# FPGC-CycloneIV-AIO.net
KiCad netlist of a schematic drawn in EasyEDA Pro
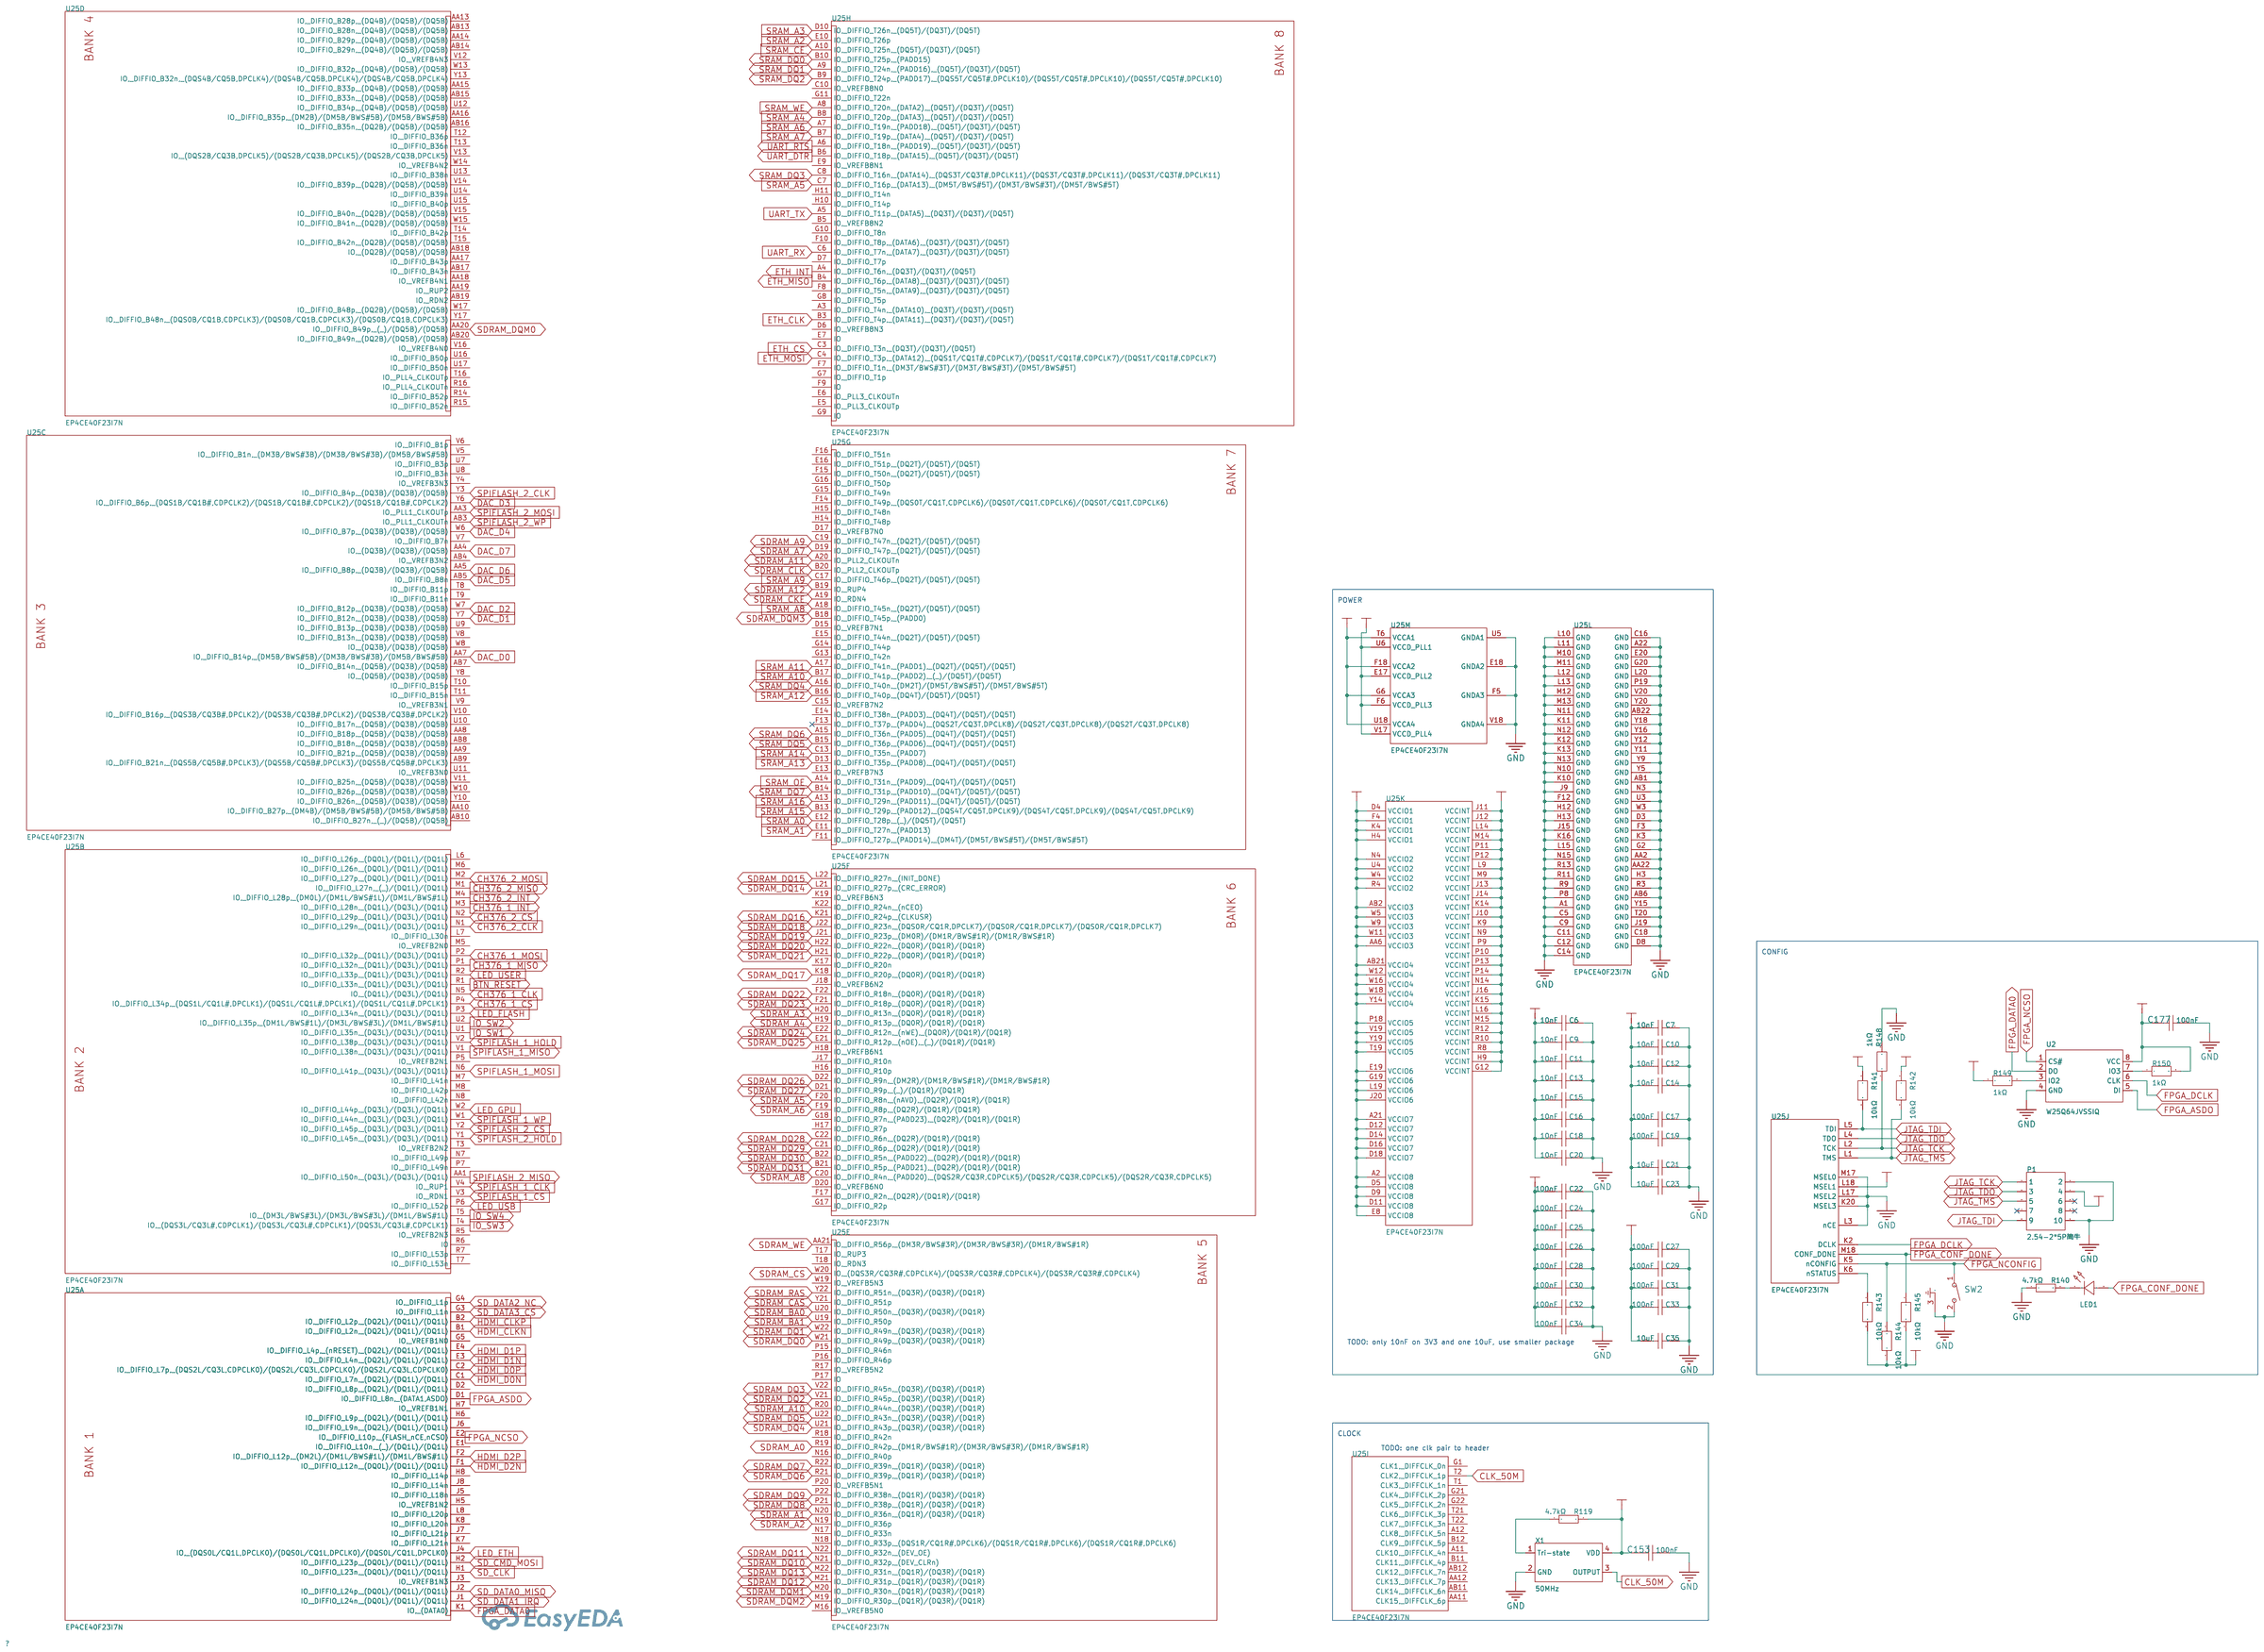
[diagram p0: FPGA]
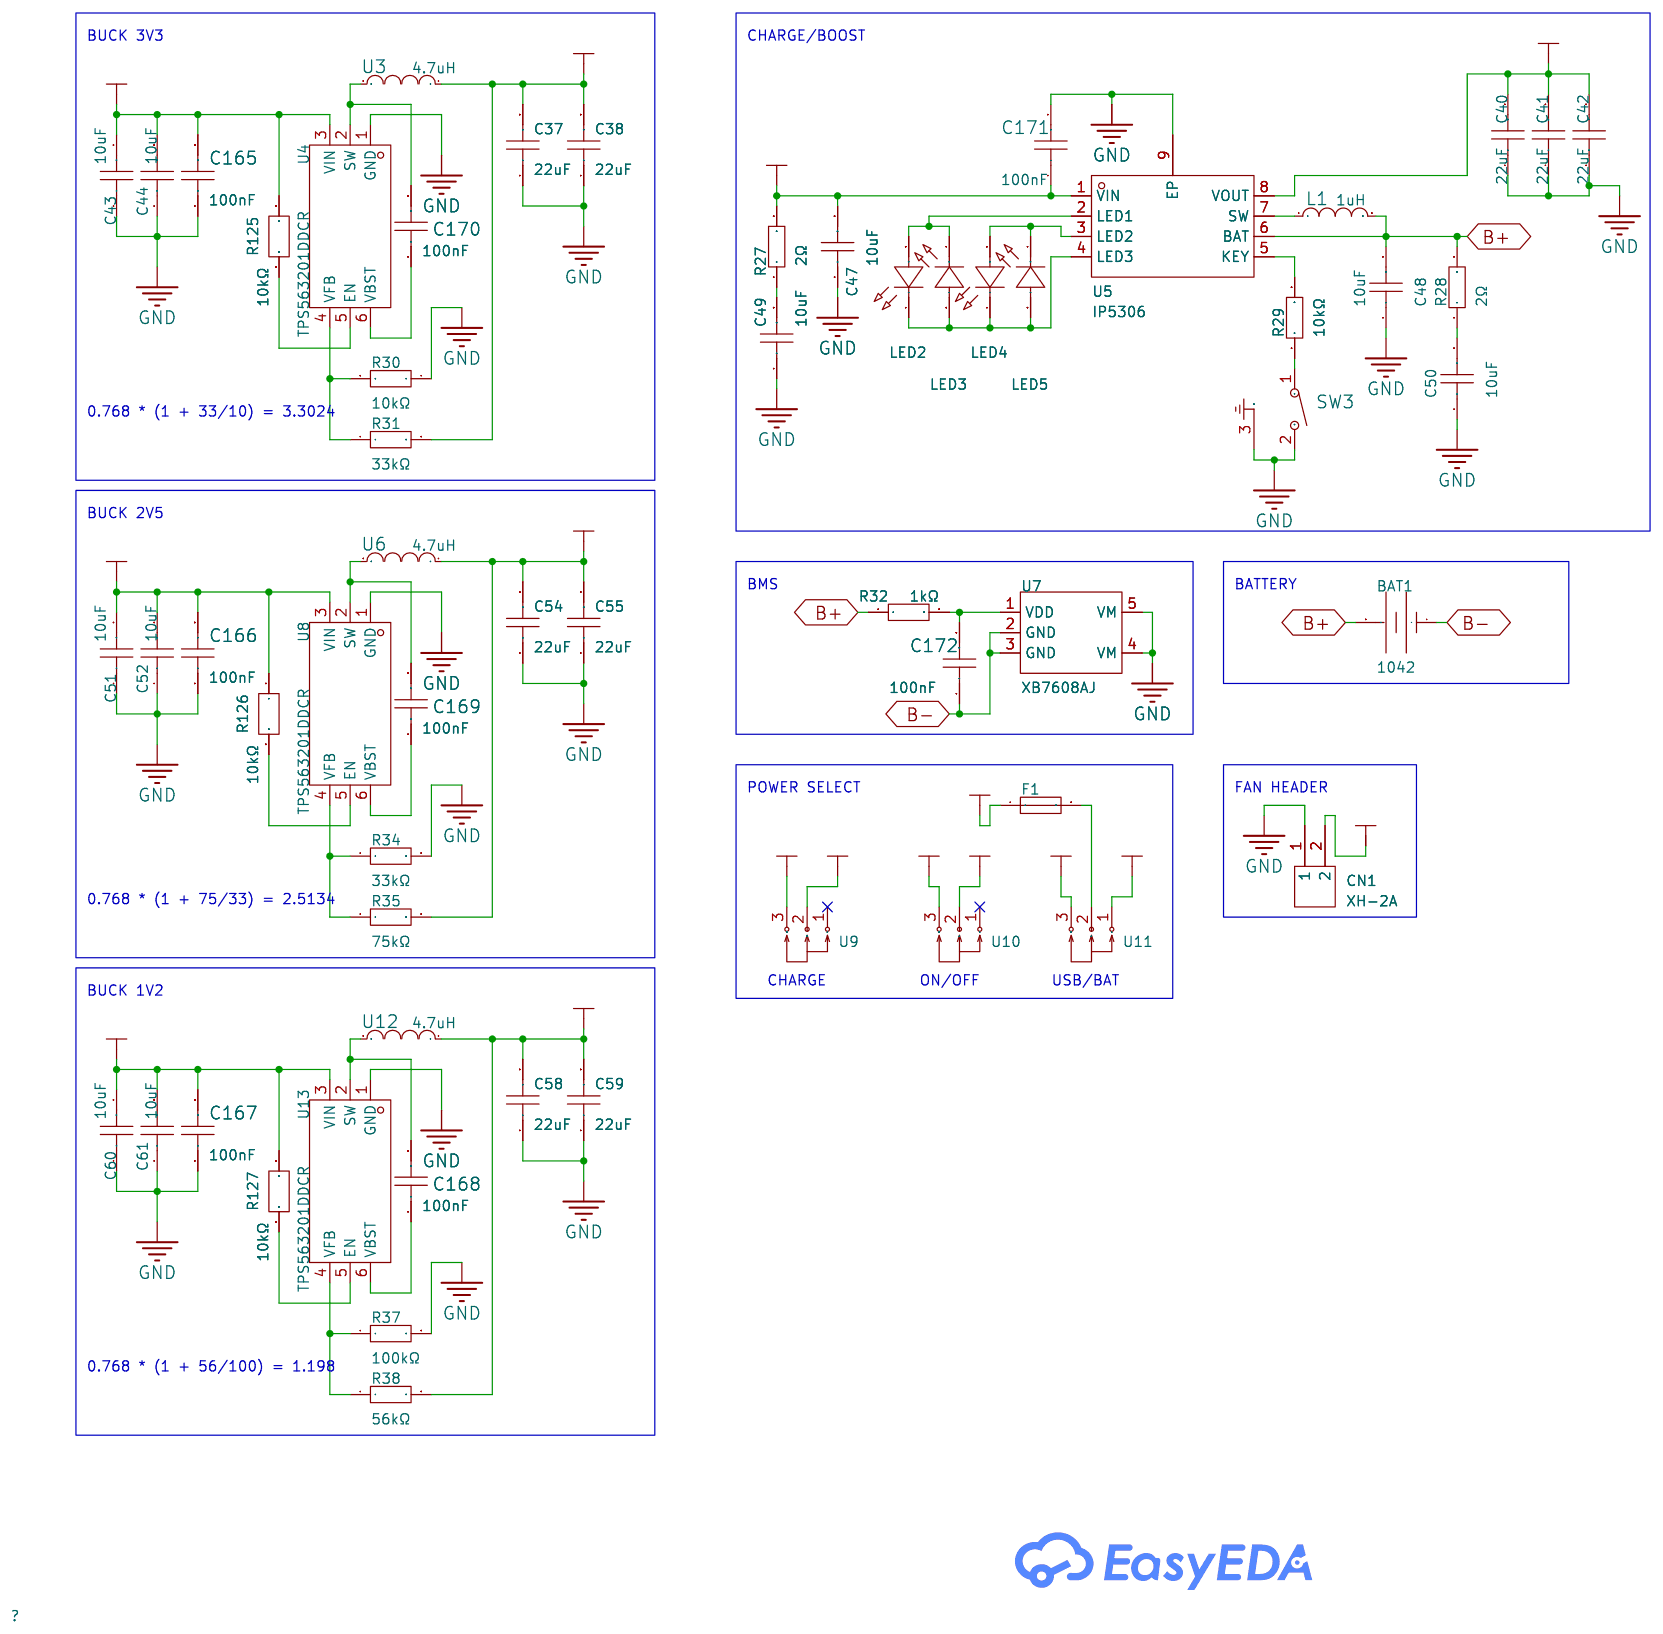
[diagram p1: Power]
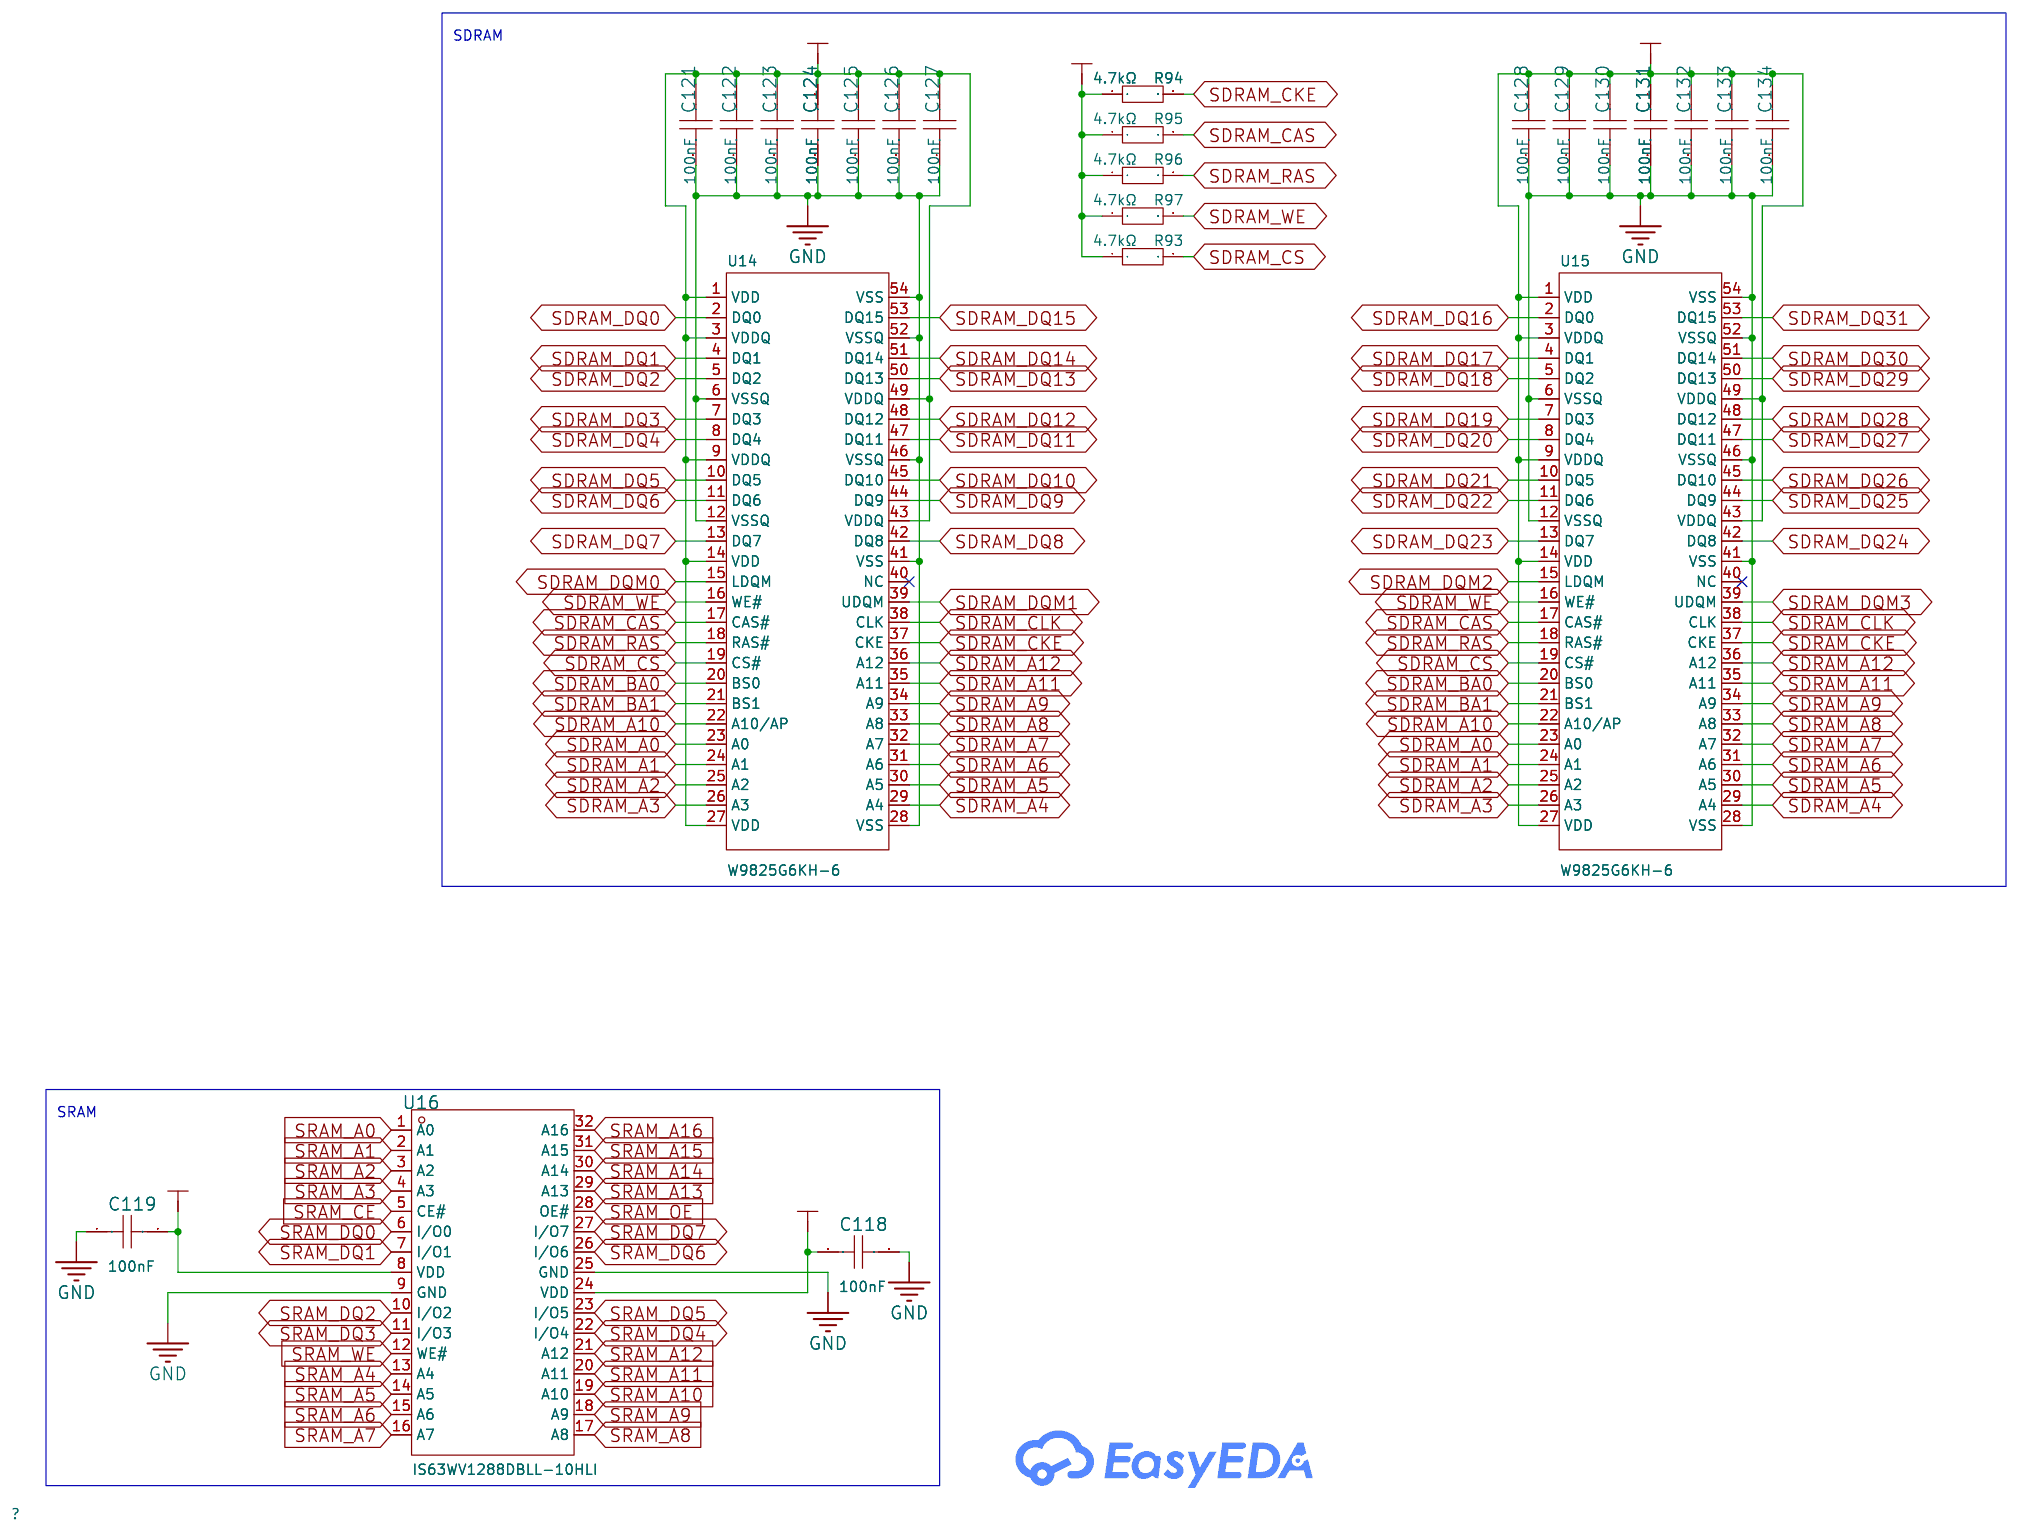
[diagram p2: RAM]
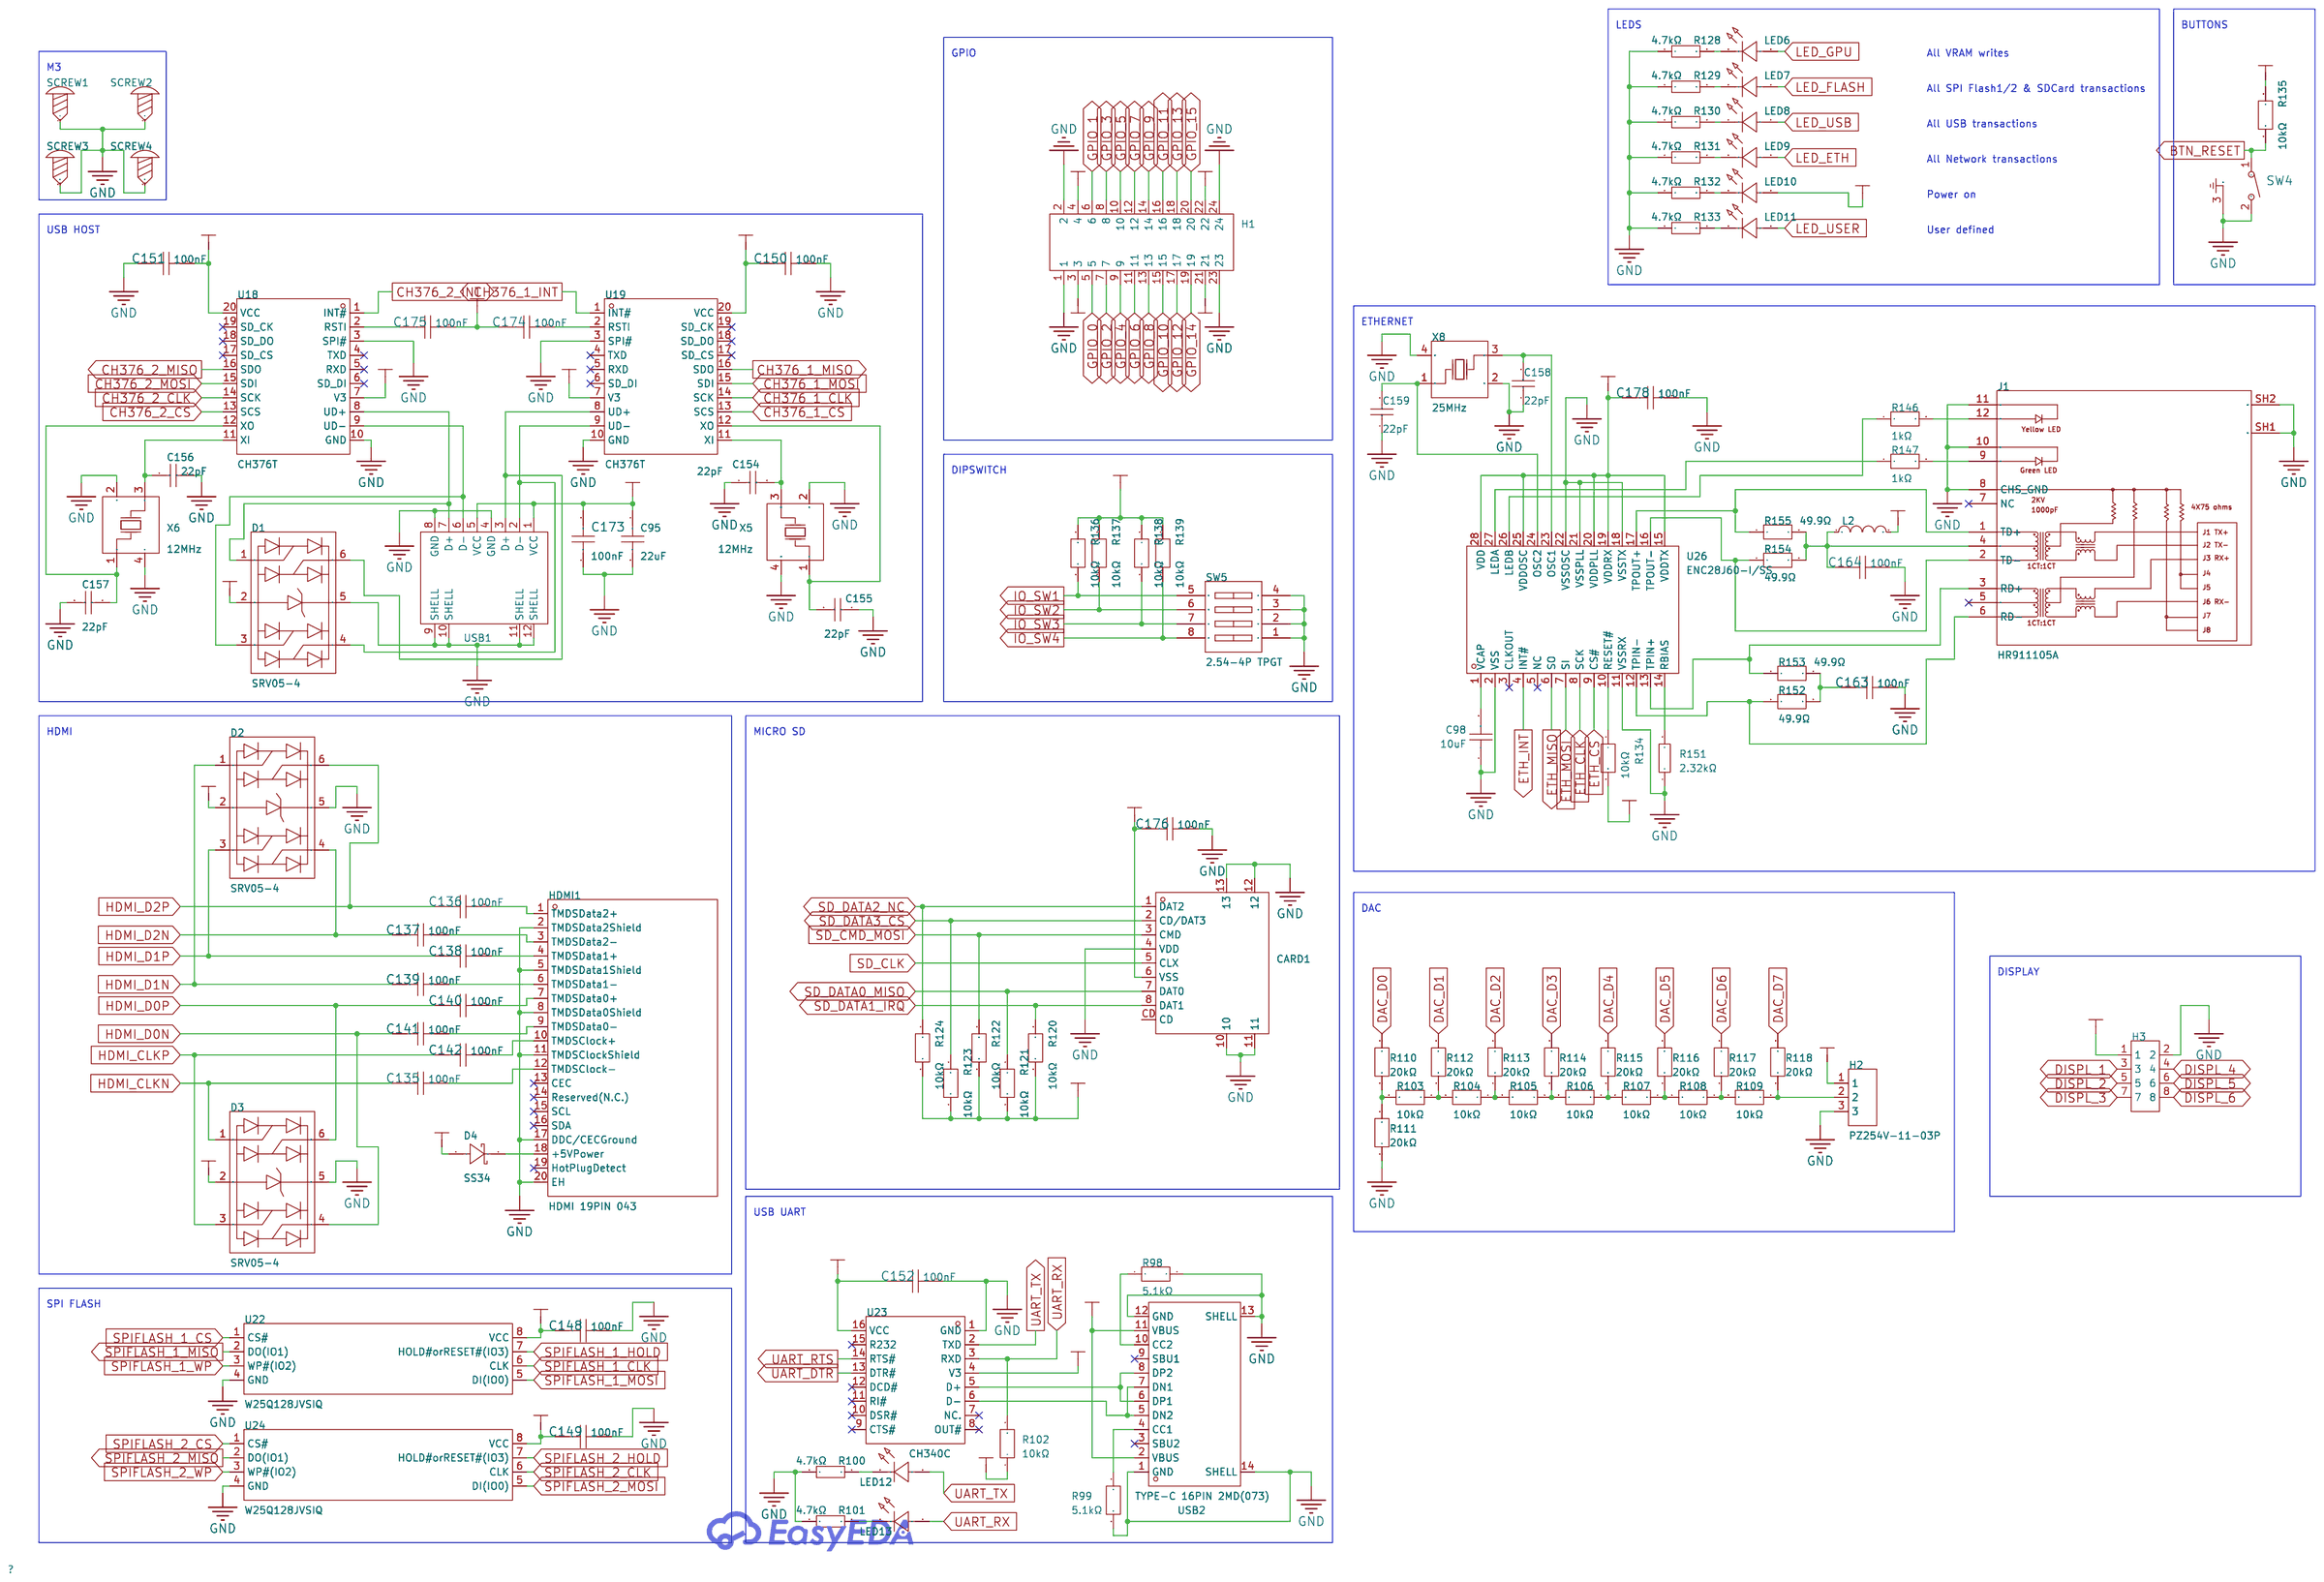
[diagram p3: IO]

(export (version "E")
  (design (tool "Eeschema 10.0.6"))
  (components
    (comp (ref "C6")
      (value "10nF")
      (footprint "easyedapro:C0805")
      (description "Capacitance:10nF Tolerance:±10% Tolerance:±10% Voltage Rating:50V Temperature Coefficient:X7R")
      (fields
        (field (name "Manufacturer Part") "CC0805KRX7R9BB103")
        (field (name "Manufacturer") "YAGEO(国巨)")
      )
      (libsource (lib "easyedapro") (part "CC0805KRX7R9BB103"))
    )
    (comp (ref "C7")
      (value "10nF")
      (footprint "easyedapro:C0805")
      (description "Capacitance:10nF Tolerance:±10% Tolerance:±10% Voltage Rating:50V Temperature Coefficient:X7R")
      (fields
        (field (name "Manufacturer Part") "CC0805KRX7R9BB103")
        (field (name "Manufacturer") "YAGEO(国巨)")
      )
      (libsource (lib "easyedapro") (part "CC0805KRX7R9BB103"))
    )
    (comp (ref "C9")
      (value "10nF")
      (footprint "easyedapro:C0805")
      (description "Capacitance:10nF Tolerance:±10% Tolerance:±10% Voltage Rating:50V Temperature Coefficient:X7R")
      (fields
        (field (name "Manufacturer Part") "CC0805KRX7R9BB103")
        (field (name "Manufacturer") "YAGEO(国巨)")
      )
      (libsource (lib "easyedapro") (part "CC0805KRX7R9BB103"))
    )
    (comp (ref "C10")
      (value "10nF")
      (footprint "easyedapro:C0805")
      (description "Capacitance:10nF Tolerance:±10% Tolerance:±10% Voltage Rating:50V Temperature Coefficient:X7R")
      (fields
        (field (name "Manufacturer Part") "CC0805KRX7R9BB103")
        (field (name "Manufacturer") "YAGEO(国巨)")
      )
      (libsource (lib "easyedapro") (part "CC0805KRX7R9BB103"))
    )
    (comp (ref "C11")
      (value "10nF")
      (footprint "easyedapro:C0805")
      (description "Capacitance:10nF Tolerance:±10% Tolerance:±10% Voltage Rating:50V Temperature Coefficient:X7R")
      (fields
        (field (name "Manufacturer Part") "CC0805KRX7R9BB103")
        (field (name "Manufacturer") "YAGEO(国巨)")
      )
      (libsource (lib "easyedapro") (part "CC0805KRX7R9BB103"))
    )
    (comp (ref "C12")
      (value "10nF")
      (footprint "easyedapro:C0805")
      (description "Capacitance:10nF Tolerance:±10% Tolerance:±10% Voltage Rating:50V Temperature Coefficient:X7R")
      (fields
        (field (name "Manufacturer Part") "CC0805KRX7R9BB103")
        (field (name "Manufacturer") "YAGEO(国巨)")
      )
      (libsource (lib "easyedapro") (part "CC0805KRX7R9BB103"))
    )
    (comp (ref "C13")
      (value "10nF")
      (footprint "easyedapro:C0805")
      (description "Capacitance:10nF Tolerance:±10% Tolerance:±10% Voltage Rating:50V Temperature Coefficient:X7R")
      (fields
        (field (name "Manufacturer Part") "CC0805KRX7R9BB103")
        (field (name "Manufacturer") "YAGEO(国巨)")
      )
      (libsource (lib "easyedapro") (part "CC0805KRX7R9BB103"))
    )
    (comp (ref "C14")
      (value "10nF")
      (footprint "easyedapro:C0805")
      (description "Capacitance:10nF Tolerance:±10% Tolerance:±10% Voltage Rating:50V Temperature Coefficient:X7R")
      (fields
        (field (name "Manufacturer Part") "CC0805KRX7R9BB103")
        (field (name "Manufacturer") "YAGEO(国巨)")
      )
      (libsource (lib "easyedapro") (part "CC0805KRX7R9BB103"))
    )
    (comp (ref "C15")
      (value "10nF")
      (footprint "easyedapro:C0805")
      (description "Capacitance:10nF Tolerance:±10% Tolerance:±10% Voltage Rating:50V Temperature Coefficient:X7R")
      (fields
        (field (name "Manufacturer Part") "CC0805KRX7R9BB103")
        (field (name "Manufacturer") "YAGEO(国巨)")
      )
      (libsource (lib "easyedapro") (part "CC0805KRX7R9BB103"))
    )
    (comp (ref "C16")
      (value "10nF")
      (footprint "easyedapro:C0805")
      (description "Capacitance:10nF Tolerance:±10% Tolerance:±10% Voltage Rating:50V Temperature Coefficient:X7R")
      (fields
        (field (name "Manufacturer Part") "CC0805KRX7R9BB103")
        (field (name "Manufacturer") "YAGEO(国巨)")
      )
      (libsource (lib "easyedapro") (part "CC0805KRX7R9BB103"))
    )
    (comp (ref "C17")
      (value "100nF")
      (footprint "easyedapro:C0805")
      (description "Capacitance:100nF Tolerance:±10% Tolerance:±10% Voltage Rating:50V Temperature Coefficient:X7R")
      (fields
        (field (name "Manufacturer Part") "CC0805KRX7R9BB104")
        (field (name "Manufacturer") "YAGEO(国巨)")
      )
      (libsource (lib "easyedapro") (part "CC0805KRX7R9BB104"))
    )
    (comp (ref "C18")
      (value "10nF")
      (footprint "easyedapro:C0805")
      (description "Capacitance:10nF Tolerance:±10% Tolerance:±10% Voltage Rating:50V Temperature Coefficient:X7R")
      (fields
        (field (name "Manufacturer Part") "CC0805KRX7R9BB103")
        (field (name "Manufacturer") "YAGEO(国巨)")
      )
      (libsource (lib "easyedapro") (part "CC0805KRX7R9BB103"))
    )
    (comp (ref "C19")
      (value "100nF")
      (footprint "easyedapro:C0805")
      (description "Capacitance:100nF Tolerance:±10% Tolerance:±10% Voltage Rating:50V Temperature Coefficient:X7R")
      (fields
        (field (name "Manufacturer Part") "CC0805KRX7R9BB104")
        (field (name "Manufacturer") "YAGEO(国巨)")
      )
      (libsource (lib "easyedapro") (part "CC0805KRX7R9BB104"))
    )
    (comp (ref "C20")
      (value "10nF")
      (footprint "easyedapro:C0805")
      (description "Capacitance:10nF Tolerance:±10% Tolerance:±10% Voltage Rating:50V Temperature Coefficient:X7R")
      (fields
        (field (name "Manufacturer Part") "CC0805KRX7R9BB103")
        (field (name "Manufacturer") "YAGEO(国巨)")
      )
      (libsource (lib "easyedapro") (part "CC0805KRX7R9BB103"))
    )
    (comp (ref "C21")
      (value "10uF")
      (footprint "easyedapro:C0805")
      (description "Capacitance:10uF Tolerance:±10% Tolerance:±10% Voltage Rating:25V Temperature Coefficient:X5R")
      (fields
        (field (name "Manufacturer Part") "CL21A106KAYNNNE")
        (field (name "Manufacturer") "SAMSUNG(三星)")
      )
      (libsource (lib "easyedapro") (part "CL21A106KAYNNNE"))
    )
    (comp (ref "C22")
      (value "100nF")
      (footprint "easyedapro:C0805")
      (description "Capacitance:100nF Tolerance:±10% Tolerance:±10% Voltage Rating:50V Temperature Coefficient:X7R")
      (fields
        (field (name "Manufacturer Part") "CC0805KRX7R9BB104")
        (field (name "Manufacturer") "YAGEO(国巨)")
      )
      (libsource (lib "easyedapro") (part "CC0805KRX7R9BB104"))
    )
    (comp (ref "C23")
      (value "10uF")
      (footprint "easyedapro:C0805")
      (description "Capacitance:10uF Tolerance:±10% Tolerance:±10% Voltage Rating:25V Temperature Coefficient:X5R")
      (fields
        (field (name "Manufacturer Part") "CL21A106KAYNNNE")
        (field (name "Manufacturer") "SAMSUNG(三星)")
      )
      (libsource (lib "easyedapro") (part "CL21A106KAYNNNE"))
    )
    (comp (ref "C24")
      (value "100nF")
      (footprint "easyedapro:C0805")
      (description "Capacitance:100nF Tolerance:±10% Tolerance:±10% Voltage Rating:50V Temperature Coefficient:X7R")
      (fields
        (field (name "Manufacturer Part") "CC0805KRX7R9BB104")
        (field (name "Manufacturer") "YAGEO(国巨)")
      )
      (libsource (lib "easyedapro") (part "CC0805KRX7R9BB104"))
    )
    (comp (ref "C25")
      (value "100nF")
      (footprint "easyedapro:C0805")
      (description "Capacitance:100nF Tolerance:±10% Tolerance:±10% Voltage Rating:50V Temperature Coefficient:X7R")
      (fields
        (field (name "Manufacturer Part") "CC0805KRX7R9BB104")
        (field (name "Manufacturer") "YAGEO(国巨)")
      )
      (libsource (lib "easyedapro") (part "CC0805KRX7R9BB104"))
    )
    (comp (ref "C26")
      (value "100nF")
      (footprint "easyedapro:C0805")
      (description "Capacitance:100nF Tolerance:±10% Tolerance:±10% Voltage Rating:50V Temperature Coefficient:X7R")
      (fields
        (field (name "Manufacturer Part") "CC0805KRX7R9BB104")
        (field (name "Manufacturer") "YAGEO(国巨)")
      )
      (libsource (lib "easyedapro") (part "CC0805KRX7R9BB104"))
    )
    (comp (ref "C27")
      (value "100nF")
      (footprint "easyedapro:C0805")
      (description "Capacitance:100nF Tolerance:±10% Tolerance:±10% Voltage Rating:50V Temperature Coefficient:X7R")
      (fields
        (field (name "Manufacturer Part") "CC0805KRX7R9BB104")
        (field (name "Manufacturer") "YAGEO(国巨)")
      )
      (libsource (lib "easyedapro") (part "CC0805KRX7R9BB104"))
    )
    (comp (ref "C28")
      (value "100nF")
      (footprint "easyedapro:C0805")
      (description "Capacitance:100nF Tolerance:±10% Tolerance:±10% Voltage Rating:50V Temperature Coefficient:X7R")
      (fields
        (field (name "Manufacturer Part") "CC0805KRX7R9BB104")
        (field (name "Manufacturer") "YAGEO(国巨)")
      )
      (libsource (lib "easyedapro") (part "CC0805KRX7R9BB104"))
    )
    (comp (ref "C29")
      (value "100nF")
      (footprint "easyedapro:C0805")
      (description "Capacitance:100nF Tolerance:±10% Tolerance:±10% Voltage Rating:50V Temperature Coefficient:X7R")
      (fields
        (field (name "Manufacturer Part") "CC0805KRX7R9BB104")
        (field (name "Manufacturer") "YAGEO(国巨)")
      )
      (libsource (lib "easyedapro") (part "CC0805KRX7R9BB104"))
    )
    (comp (ref "C30")
      (value "100nF")
      (footprint "easyedapro:C0805")
      (description "Capacitance:100nF Tolerance:±10% Tolerance:±10% Voltage Rating:50V Temperature Coefficient:X7R")
      (fields
        (field (name "Manufacturer Part") "CC0805KRX7R9BB104")
        (field (name "Manufacturer") "YAGEO(国巨)")
      )
      (libsource (lib "easyedapro") (part "CC0805KRX7R9BB104"))
    )
    (comp (ref "C31")
      (value "100nF")
      (footprint "easyedapro:C0805")
      (description "Capacitance:100nF Tolerance:±10% Tolerance:±10% Voltage Rating:50V Temperature Coefficient:X7R")
      (fields
        (field (name "Manufacturer Part") "CC0805KRX7R9BB104")
        (field (name "Manufacturer") "YAGEO(国巨)")
      )
      (libsource (lib "easyedapro") (part "CC0805KRX7R9BB104"))
    )
    (comp (ref "C32")
      (value "100nF")
      (footprint "easyedapro:C0805")
      (description "Capacitance:100nF Tolerance:±10% Tolerance:±10% Voltage Rating:50V Temperature Coefficient:X7R")
      (fields
        (field (name "Manufacturer Part") "CC0805KRX7R9BB104")
        (field (name "Manufacturer") "YAGEO(国巨)")
      )
      (libsource (lib "easyedapro") (part "CC0805KRX7R9BB104"))
    )
    (comp (ref "C33")
      (value "100nF")
      (footprint "easyedapro:C0805")
      (description "Capacitance:100nF Tolerance:±10% Tolerance:±10% Voltage Rating:50V Temperature Coefficient:X7R")
      (fields
        (field (name "Manufacturer Part") "CC0805KRX7R9BB104")
        (field (name "Manufacturer") "YAGEO(国巨)")
      )
      (libsource (lib "easyedapro") (part "CC0805KRX7R9BB104"))
    )
    (comp (ref "C34")
      (value "100nF")
      (footprint "easyedapro:C0805")
      (description "Capacitance:100nF Tolerance:±10% Tolerance:±10% Voltage Rating:50V Temperature Coefficient:X7R")
      (fields
        (field (name "Manufacturer Part") "CC0805KRX7R9BB104")
        (field (name "Manufacturer") "YAGEO(国巨)")
      )
      (libsource (lib "easyedapro") (part "CC0805KRX7R9BB104"))
    )
    (comp (ref "C35")
      (value "10uF")
      (footprint "easyedapro:C0805")
      (description "Capacitance:10uF Tolerance:±10% Tolerance:±10% Voltage Rating:25V Temperature Coefficient:X5R")
      (fields
        (field (name "Manufacturer Part") "CL21A106KAYNNNE")
        (field (name "Manufacturer") "SAMSUNG(三星)")
      )
      (libsource (lib "easyedapro") (part "CL21A106KAYNNNE"))
    )
    (comp (ref "C153")
      (value "100nF")
      (footprint "easyedapro:C0603")
      (description "Capacitance:100nF Tolerance:±10% Tolerance:±10% Voltage Rating:50V Temperature Coefficient:X7R")
      (fields
        (field (name "Manufacturer Part") "CL10B104KB8NNNC")
        (field (name "Manufacturer") "SAMSUNG(三星)")
      )
      (libsource (lib "easyedapro") (part "CL10B104KB8NNNC"))
    )
    (comp (ref "C177")
      (value "100nF")
      (footprint "easyedapro:C0603")
      (description "Capacitance:100nF Tolerance:±10% Tolerance:±10% Voltage Rating:50V Temperature Coefficient:X7R")
      (fields
        (field (name "Manufacturer Part") "CL10B104KB8NNNC")
        (field (name "Manufacturer") "SAMSUNG(三星)")
      )
      (libsource (lib "easyedapro") (part "CL10B104KB8NNNC"))
    )
    (comp (ref "LED1")
      (value "XL-2012SURC")
      (footprint "easyedapro:LED0805-RD_RED")
      (fields (field (name "Manufacturer") "XINGLIGHT(成兴光)"))
      (libsource (lib "easyedapro") (part "XL-2012SURC"))
    )
    (comp (ref "P1")
      (value "2.54-2*5P简牛")
      (footprint "easyedapro:IDC-TH_10P-P2.54_C5665")
      (fields (field (name "Manufacturer") "BOOMELE(博穆精密)"))
      (libsource (lib "easyedapro") (part "HDR-IDC-2.54-2X5P"))
    )
    (comp (ref "R119")
      (value "4.7kΩ")
      (footprint "easyedapro:R0603")
      (fields (field (name "Manufacturer Part") "RC0603FR-074K7L") (field (name "Manufacturer") "YAGEO(国巨)"))
      (libsource (lib "easyedapro") (part "RC0603FR-074K7L"))
    )
    (comp (ref "R140")
      (value "4.7kΩ")
      (footprint "easyedapro:R0603")
      (fields (field (name "Manufacturer Part") "RC0603FR-074K7L") (field (name "Manufacturer") "YAGEO(国巨)"))
      (libsource (lib "easyedapro") (part "RC0603FR-074K7L"))
    )
    (comp (ref "R141")
      (value "10kΩ")
      (footprint "easyedapro:R0603")
      (fields (field (name "Manufacturer Part") "FRC0603F1002TS") (field (name "Manufacturer") "FOJAN(富捷)"))
      (libsource (lib "easyedapro") (part "FRC0603F1002TS"))
    )
    (comp (ref "R142")
      (value "10kΩ")
      (footprint "easyedapro:R0603")
      (fields (field (name "Manufacturer Part") "FRC0603F1002TS") (field (name "Manufacturer") "FOJAN(富捷)"))
      (libsource (lib "easyedapro") (part "FRC0603F1002TS"))
    )
    (comp (ref "R143")
      (value "10kΩ")
      (footprint "easyedapro:R0603")
      (fields (field (name "Manufacturer Part") "FRC0603F1002TS") (field (name "Manufacturer") "FOJAN(富捷)"))
      (libsource (lib "easyedapro") (part "FRC0603F1002TS"))
    )
    (comp (ref "R144")
      (value "10kΩ")
      (footprint "easyedapro:R0603")
      (fields (field (name "Manufacturer Part") "FRC0603F1002TS") (field (name "Manufacturer") "FOJAN(富捷)"))
      (libsource (lib "easyedapro") (part "FRC0603F1002TS"))
    )
    (comp (ref "R145")
      (value "10kΩ")
      (footprint "easyedapro:R0603")
      (fields (field (name "Manufacturer Part") "FRC0603F1002TS") (field (name "Manufacturer") "FOJAN(富捷)"))
      (libsource (lib "easyedapro") (part "FRC0603F1002TS"))
    )
    (comp (ref "R148")
      (value "1kΩ")
      (footprint "easyedapro:R0603")
      (fields (field (name "Manufacturer Part") "FRC0603F1001TS") (field (name "Manufacturer") "FOJAN(富捷)"))
      (libsource (lib "easyedapro") (part "FRC0603F1001TS"))
    )
    (comp (ref "R149")
      (value "1kΩ")
      (footprint "easyedapro:R0603")
      (fields (field (name "Manufacturer Part") "FRC0603F1001TS") (field (name "Manufacturer") "FOJAN(富捷)"))
      (libsource (lib "easyedapro") (part "FRC0603F1001TS"))
    )
    (comp (ref "R150")
      (value "1kΩ")
      (footprint "easyedapro:R0603")
      (fields (field (name "Manufacturer Part") "FRC0603F1001TS") (field (name "Manufacturer") "FOJAN(富捷)"))
      (libsource (lib "easyedapro") (part "FRC0603F1001TS"))
    )
    (comp (ref "SW2")
      (value "TS-1009B-05026")
      (footprint "easyedapro:SW-TH_3P-L4.5-W3.8-P3.10-LS1.9")
      (fields (field (name "Manufacturer") "XUNPU(讯普)"))
      (libsource (lib "easyedapro") (part "TS-1009B-05026"))
    )
    (comp (ref "U2")
      (value "W25Q64JVSSIQ")
      (footprint "easyedapro:SOP-8_L5.3-W5.3-P1.27-LS8.0-BL")
      (fields (field (name "Manufacturer") "Winbond(华邦)"))
      (libsource (lib "easyedapro") (part "W25Q64JVSSIQ"))
    )
    (comp (ref "U25")
      (value "EP4CE40F23I7N")
      (footprint "easyedapro:FBGA-484_L23.0-W23.0-R22-C22-P1.00-TL")
      (fields (field (name "Manufacturer") "Intel/Altera"))
      (libsource (lib "easyedapro") (part "EP4CE40F23I7N"))
    )
    (comp (ref "X1")
      (value "50MHz")
      (footprint "easyedapro:OSC-SMD_4P-L3.2-W2.5-BL")
      (fields (field (name "Manufacturer Part") "OT322550MJBA4SL") (field (name "Manufacturer") "YXC(扬兴晶振)"))
      (libsource (lib "easyedapro") (part "OT322550MJBA4SL"))
    )
    (comp (ref "BAT1")
      (value "1042")
      (footprint "easyedapro:BAT-SMD_1042P")
      (fields (field (name "Manufacturer") "Keystone"))
      (libsource (lib "easyedapro") (part "1042"))
    )
    (comp (ref "C37")
      (value "22uF")
      (footprint "easyedapro:C0805")
      (description "Capacitance:22uF Tolerance:±10% Tolerance:±10% Voltage Rating:16V Temperature Coefficient:X5R")
      (fields
        (field (name "Manufacturer Part") "CL21A226KOQNNNE")
        (field (name "Manufacturer") "SAMSUNG(三星)")
      )
      (libsource (lib "easyedapro") (part "CL21A226KOQNNNE"))
    )
    (comp (ref "C38")
      (value "22uF")
      (footprint "easyedapro:C0805")
      (description "Capacitance:22uF Tolerance:±10% Tolerance:±10% Voltage Rating:16V Temperature Coefficient:X5R")
      (fields
        (field (name "Manufacturer Part") "CL21A226KOQNNNE")
        (field (name "Manufacturer") "SAMSUNG(三星)")
      )
      (libsource (lib "easyedapro") (part "CL21A226KOQNNNE"))
    )
    (comp (ref "C40")
      (value "22uF")
      (footprint "easyedapro:C0805")
      (description "Capacitance:22uF Tolerance:±10% Tolerance:±10% Voltage Rating:16V Temperature Coefficient:X5R")
      (fields
        (field (name "Manufacturer Part") "CL21A226KOQNNNE")
        (field (name "Manufacturer") "SAMSUNG(三星)")
      )
      (libsource (lib "easyedapro") (part "CL21A226KOQNNNE"))
    )
    (comp (ref "C41")
      (value "22uF")
      (footprint "easyedapro:C0805")
      (description "Capacitance:22uF Tolerance:±10% Tolerance:±10% Voltage Rating:16V Temperature Coefficient:X5R")
      (fields
        (field (name "Manufacturer Part") "CL21A226KOQNNNE")
        (field (name "Manufacturer") "SAMSUNG(三星)")
      )
      (libsource (lib "easyedapro") (part "CL21A226KOQNNNE"))
    )
    (comp (ref "C42")
      (value "22uF")
      (footprint "easyedapro:C0805")
      (description "Capacitance:22uF Tolerance:±10% Tolerance:±10% Voltage Rating:16V Temperature Coefficient:X5R")
      (fields
        (field (name "Manufacturer Part") "CL21A226KOQNNNE")
        (field (name "Manufacturer") "SAMSUNG(三星)")
      )
      (libsource (lib "easyedapro") (part "CL21A226KOQNNNE"))
    )
    (comp (ref "C43")
      (value "10uF")
      (footprint "easyedapro:C0805")
      (description "Capacitance:10uF Tolerance:±10% Tolerance:±10% Voltage Rating:25V Temperature Coefficient:X5R")
      (fields
        (field (name "Manufacturer Part") "CL21A106KAYNNNE")
        (field (name "Manufacturer") "SAMSUNG(三星)")
      )
      (libsource (lib "easyedapro") (part "CL21A106KAYNNNE"))
    )
    (comp (ref "C44")
      (value "10uF")
      (footprint "easyedapro:C0805")
      (description "Capacitance:10uF Tolerance:±10% Tolerance:±10% Voltage Rating:25V Temperature Coefficient:X5R")
      (fields
        (field (name "Manufacturer Part") "CL21A106KAYNNNE")
        (field (name "Manufacturer") "SAMSUNG(三星)")
      )
      (libsource (lib "easyedapro") (part "CL21A106KAYNNNE"))
    )
    (comp (ref "C47")
      (value "10uF")
      (footprint "easyedapro:C0805")
      (description "Capacitance:10uF Tolerance:±10% Tolerance:±10% Voltage Rating:25V Temperature Coefficient:X5R")
      (fields
        (field (name "Manufacturer Part") "CL21A106KAYNNNE")
        (field (name "Manufacturer") "SAMSUNG(三星)")
      )
      (libsource (lib "easyedapro") (part "CL21A106KAYNNNE"))
    )
    (comp (ref "C48")
      (value "10uF")
      (footprint "easyedapro:C0805")
      (description "Capacitance:10uF Tolerance:±10% Tolerance:±10% Voltage Rating:25V Temperature Coefficient:X5R")
      (fields
        (field (name "Manufacturer Part") "CL21A106KAYNNNE")
        (field (name "Manufacturer") "SAMSUNG(三星)")
      )
      (libsource (lib "easyedapro") (part "CL21A106KAYNNNE"))
    )
    (comp (ref "C49")
      (value "10uF")
      (footprint "easyedapro:C0805")
      (description "Capacitance:10uF Tolerance:±10% Tolerance:±10% Voltage Rating:25V Temperature Coefficient:X5R")
      (fields
        (field (name "Manufacturer Part") "CL21A106KAYNNNE")
        (field (name "Manufacturer") "SAMSUNG(三星)")
      )
      (libsource (lib "easyedapro") (part "CL21A106KAYNNNE"))
    )
    (comp (ref "C50")
      (value "10uF")
      (footprint "easyedapro:C0805")
      (description "Capacitance:10uF Tolerance:±10% Tolerance:±10% Voltage Rating:25V Temperature Coefficient:X5R")
      (fields
        (field (name "Manufacturer Part") "CL21A106KAYNNNE")
        (field (name "Manufacturer") "SAMSUNG(三星)")
      )
      (libsource (lib "easyedapro") (part "CL21A106KAYNNNE"))
    )
    (comp (ref "C51")
      (value "10uF")
      (footprint "easyedapro:C0805")
      (description "Capacitance:10uF Tolerance:±10% Tolerance:±10% Voltage Rating:25V Temperature Coefficient:X5R")
      (fields
        (field (name "Manufacturer Part") "CL21A106KAYNNNE")
        (field (name "Manufacturer") "SAMSUNG(三星)")
      )
      (libsource (lib "easyedapro") (part "CL21A106KAYNNNE"))
    )
    (comp (ref "C52")
      (value "10uF")
      (footprint "easyedapro:C0805")
      (description "Capacitance:10uF Tolerance:±10% Tolerance:±10% Voltage Rating:25V Temperature Coefficient:X5R")
      (fields
        (field (name "Manufacturer Part") "CL21A106KAYNNNE")
        (field (name "Manufacturer") "SAMSUNG(三星)")
      )
      (libsource (lib "easyedapro") (part "CL21A106KAYNNNE"))
    )
    (comp (ref "C54")
      (value "22uF")
      (footprint "easyedapro:C0805")
      (description "Capacitance:22uF Tolerance:±10% Tolerance:±10% Voltage Rating:16V Temperature Coefficient:X5R")
      (fields
        (field (name "Manufacturer Part") "CL21A226KOQNNNE")
        (field (name "Manufacturer") "SAMSUNG(三星)")
      )
      (libsource (lib "easyedapro") (part "CL21A226KOQNNNE"))
    )
    (comp (ref "C55")
      (value "22uF")
      (footprint "easyedapro:C0805")
      (description "Capacitance:22uF Tolerance:±10% Tolerance:±10% Voltage Rating:16V Temperature Coefficient:X5R")
      (fields
        (field (name "Manufacturer Part") "CL21A226KOQNNNE")
        (field (name "Manufacturer") "SAMSUNG(三星)")
      )
      (libsource (lib "easyedapro") (part "CL21A226KOQNNNE"))
    )
    (comp (ref "C58")
      (value "22uF")
      (footprint "easyedapro:C0805")
      (description "Capacitance:22uF Tolerance:±10% Tolerance:±10% Voltage Rating:16V Temperature Coefficient:X5R")
      (fields
        (field (name "Manufacturer Part") "CL21A226KOQNNNE")
        (field (name "Manufacturer") "SAMSUNG(三星)")
      )
      (libsource (lib "easyedapro") (part "CL21A226KOQNNNE"))
    )
    (comp (ref "C59")
      (value "22uF")
      (footprint "easyedapro:C0805")
      (description "Capacitance:22uF Tolerance:±10% Tolerance:±10% Voltage Rating:16V Temperature Coefficient:X5R")
      (fields
        (field (name "Manufacturer Part") "CL21A226KOQNNNE")
        (field (name "Manufacturer") "SAMSUNG(三星)")
      )
      (libsource (lib "easyedapro") (part "CL21A226KOQNNNE"))
    )
    (comp (ref "C60")
      (value "10uF")
      (footprint "easyedapro:C0805")
      (description "Capacitance:10uF Tolerance:±10% Tolerance:±10% Voltage Rating:25V Temperature Coefficient:X5R")
      (fields
        (field (name "Manufacturer Part") "CL21A106KAYNNNE")
        (field (name "Manufacturer") "SAMSUNG(三星)")
      )
      (libsource (lib "easyedapro") (part "CL21A106KAYNNNE"))
    )
    (comp (ref "C61")
      (value "10uF")
      (footprint "easyedapro:C0805")
      (description "Capacitance:10uF Tolerance:±10% Tolerance:±10% Voltage Rating:25V Temperature Coefficient:X5R")
      (fields
        (field (name "Manufacturer Part") "CL21A106KAYNNNE")
        (field (name "Manufacturer") "SAMSUNG(三星)")
      )
      (libsource (lib "easyedapro") (part "CL21A106KAYNNNE"))
    )
    (comp (ref "C165")
      (value "100nF")
      (footprint "easyedapro:C0603")
      (description "Capacitance:100nF Tolerance:±10% Tolerance:±10% Voltage Rating:50V Temperature Coefficient:X7R")
      (fields
        (field (name "Manufacturer Part") "CL10B104KB8NNNC")
        (field (name "Manufacturer") "SAMSUNG(三星)")
      )
      (libsource (lib "easyedapro") (part "CL10B104KB8NNNC"))
    )
    (comp (ref "C166")
      (value "100nF")
      (footprint "easyedapro:C0603")
      (description "Capacitance:100nF Tolerance:±10% Tolerance:±10% Voltage Rating:50V Temperature Coefficient:X7R")
      (fields
        (field (name "Manufacturer Part") "CL10B104KB8NNNC")
        (field (name "Manufacturer") "SAMSUNG(三星)")
      )
      (libsource (lib "easyedapro") (part "CL10B104KB8NNNC"))
    )
    (comp (ref "C167")
      (value "100nF")
      (footprint "easyedapro:C0603")
      (description "Capacitance:100nF Tolerance:±10% Tolerance:±10% Voltage Rating:50V Temperature Coefficient:X7R")
      (fields
        (field (name "Manufacturer Part") "CL10B104KB8NNNC")
        (field (name "Manufacturer") "SAMSUNG(三星)")
      )
      (libsource (lib "easyedapro") (part "CL10B104KB8NNNC"))
    )
    (comp (ref "C168")
      (value "100nF")
      (footprint "easyedapro:C0603")
      (description "Capacitance:100nF Tolerance:±10% Tolerance:±10% Voltage Rating:50V Temperature Coefficient:X7R")
      (fields
        (field (name "Manufacturer Part") "CL10B104KB8NNNC")
        (field (name "Manufacturer") "SAMSUNG(三星)")
      )
      (libsource (lib "easyedapro") (part "CL10B104KB8NNNC"))
    )
    (comp (ref "C169")
      (value "100nF")
      (footprint "easyedapro:C0603")
      (description "Capacitance:100nF Tolerance:±10% Tolerance:±10% Voltage Rating:50V Temperature Coefficient:X7R")
      (fields
        (field (name "Manufacturer Part") "CL10B104KB8NNNC")
        (field (name "Manufacturer") "SAMSUNG(三星)")
      )
      (libsource (lib "easyedapro") (part "CL10B104KB8NNNC"))
    )
    (comp (ref "C170")
      (value "100nF")
      (footprint "easyedapro:C0603")
      (description "Capacitance:100nF Tolerance:±10% Tolerance:±10% Voltage Rating:50V Temperature Coefficient:X7R")
      (fields
        (field (name "Manufacturer Part") "CL10B104KB8NNNC")
        (field (name "Manufacturer") "SAMSUNG(三星)")
      )
      (libsource (lib "easyedapro") (part "CL10B104KB8NNNC"))
    )
    (comp (ref "C171")
      (value "100nF")
      (footprint "easyedapro:C0603")
      (description "Capacitance:100nF Tolerance:±10% Tolerance:±10% Voltage Rating:50V Temperature Coefficient:X7R")
      (fields
        (field (name "Manufacturer Part") "CL10B104KB8NNNC")
        (field (name "Manufacturer") "SAMSUNG(三星)")
      )
      (libsource (lib "easyedapro") (part "CL10B104KB8NNNC"))
    )
    (comp (ref "C172")
      (value "100nF")
      (footprint "easyedapro:C0603")
      (description "Capacitance:100nF Tolerance:±10% Tolerance:±10% Voltage Rating:50V Temperature Coefficient:X7R")
      (fields
        (field (name "Manufacturer Part") "CL10B104KB8NNNC")
        (field (name "Manufacturer") "SAMSUNG(三星)")
      )
      (libsource (lib "easyedapro") (part "CL10B104KB8NNNC"))
    )
    (comp (ref "CN1")
      (value "XH-2A")
      (footprint "easyedapro:CONN-TH_XH-2A")
      (fields (field (name "Manufacturer") "BOOMELE(博穆精密)"))
      (libsource (lib "easyedapro") (part "XH-2A"))
    )
    (comp (ref "F1")
      (value "MF-MSMF110/16-2")
      (footprint "easyedapro:F1812")
      (fields (field (name "Manufacturer") "BOURNS"))
      (libsource (lib "easyedapro") (part "MF-MSMF110/16-2"))
    )
    (comp (ref "L1")
      (value "1uH")
      (footprint "easyedapro:IND-SMD_L7.2-W6.6_GPSR0730")
      (fields (field (name "Manufacturer Part") "CYA0630-1.0UH") (field (name "Manufacturer") "SHOU HAN(首韩)"))
      (libsource (lib "easyedapro") (part "CYA0630-1.0UH"))
    )
    (comp (ref "LED2")
      (value "XL-2012SURC")
      (footprint "easyedapro:LED0805-RD_RED")
      (fields (field (name "Manufacturer") "XINGLIGHT(成兴光)"))
      (libsource (lib "easyedapro") (part "XL-2012SURC"))
    )
    (comp (ref "LED3")
      (value "XL-2012SURC")
      (footprint "easyedapro:LED0805-RD_RED")
      (fields (field (name "Manufacturer") "XINGLIGHT(成兴光)"))
      (libsource (lib "easyedapro") (part "XL-2012SURC"))
    )
    (comp (ref "LED4")
      (value "XL-2012SURC")
      (footprint "easyedapro:LED0805-RD_RED")
      (fields (field (name "Manufacturer") "XINGLIGHT(成兴光)"))
      (libsource (lib "easyedapro") (part "XL-2012SURC"))
    )
    (comp (ref "LED5")
      (value "XL-2012SURC")
      (footprint "easyedapro:LED0805-RD_RED")
      (fields (field (name "Manufacturer") "XINGLIGHT(成兴光)"))
      (libsource (lib "easyedapro") (part "XL-2012SURC"))
    )
    (comp (ref "R27")
      (value "2Ω")
      (footprint "easyedapro:R0805")
      (fields
        (field (name "Manufacturer Part") "0805W8F200KT5E")
        (field (name "Manufacturer") "UNI-ROYAL(厚声)")
      )
      (libsource (lib "easyedapro") (part "0805W8F200KT5E"))
    )
    (comp (ref "R28")
      (value "2Ω")
      (footprint "easyedapro:R0805")
      (fields
        (field (name "Manufacturer Part") "0805W8F200KT5E")
        (field (name "Manufacturer") "UNI-ROYAL(厚声)")
      )
      (libsource (lib "easyedapro") (part "0805W8F200KT5E"))
    )
    (comp (ref "R29")
      (value "10kΩ")
      (footprint "easyedapro:R0805")
      (fields (field (name "Manufacturer Part") "RC0805FR-0710KL") (field (name "Manufacturer") "YAGEO(国巨)"))
      (libsource (lib "easyedapro") (part "RC0805FR-0710KL"))
    )
    (comp (ref "R30")
      (value "10kΩ")
      (footprint "easyedapro:R0805")
      (fields (field (name "Manufacturer Part") "RC0805FR-0710KL") (field (name "Manufacturer") "YAGEO(国巨)"))
      (libsource (lib "easyedapro") (part "RC0805FR-0710KL"))
    )
    (comp (ref "R31")
      (value "33kΩ")
      (footprint "easyedapro:R0805")
      (fields (field (name "Manufacturer Part") "RC0805FR-0733KL") (field (name "Manufacturer") "YAGEO(国巨)"))
      (libsource (lib "easyedapro") (part "RC0805FR-0733KL"))
    )
    (comp (ref "R32")
      (value "1kΩ")
      (footprint "easyedapro:R0805")
      (fields
        (field (name "Manufacturer Part") "0805W8F1001T5E")
        (field (name "Manufacturer") "UNI-ROYAL(厚声)")
      )
      (libsource (lib "easyedapro") (part "0805W8F1001T5E"))
    )
    (comp (ref "R34")
      (value "33kΩ")
      (footprint "easyedapro:R0805")
      (fields (field (name "Manufacturer Part") "RC0805FR-0733KL") (field (name "Manufacturer") "YAGEO(国巨)"))
      (libsource (lib "easyedapro") (part "RC0805FR-0733KL"))
    )
    (comp (ref "R35")
      (value "75kΩ")
      (footprint "easyedapro:R0805")
      (fields
        (field (name "Manufacturer Part") "0805W8F7502T5E")
        (field (name "Manufacturer") "UNI-ROYAL(厚声)")
      )
      (libsource (lib "easyedapro") (part "0805W8F7502T5E"))
    )
    (comp (ref "R37")
      (value "100kΩ")
      (footprint "easyedapro:R0805")
      (fields (field (name "Manufacturer Part") "RS-05K1003FT") (field (name "Manufacturer") "FH(风华)"))
      (libsource (lib "easyedapro") (part "RS-05K1003FT"))
    )
    (comp (ref "R38")
      (value "56kΩ")
      (footprint "easyedapro:R0805")
      (fields
        (field (name "Manufacturer Part") "0805W8F5602T5E")
        (field (name "Manufacturer") "UNI-ROYAL(厚声)")
      )
      (libsource (lib "easyedapro") (part "0805W8F5602T5E"))
    )
    (comp (ref "R125")
      (value "10kΩ")
      (footprint "easyedapro:R0603")
      (fields (field (name "Manufacturer Part") "FRC0603F1002TS") (field (name "Manufacturer") "FOJAN(富捷)"))
      (libsource (lib "easyedapro") (part "FRC0603F1002TS"))
    )
    (comp (ref "R126")
      (value "10kΩ")
      (footprint "easyedapro:R0603")
      (fields (field (name "Manufacturer Part") "FRC0603F1002TS") (field (name "Manufacturer") "FOJAN(富捷)"))
      (libsource (lib "easyedapro") (part "FRC0603F1002TS"))
    )
    (comp (ref "R127")
      (value "10kΩ")
      (footprint "easyedapro:R0603")
      (fields (field (name "Manufacturer Part") "FRC0603F1002TS") (field (name "Manufacturer") "FOJAN(富捷)"))
      (libsource (lib "easyedapro") (part "FRC0603F1002TS"))
    )
    (comp (ref "SW3")
      (value "TS-1009B-05026")
      (footprint "easyedapro:SW-TH_3P-L4.5-W3.8-P3.10-LS1.9")
      (fields (field (name "Manufacturer") "XUNPU(讯普)"))
      (libsource (lib "easyedapro") (part "TS-1009B-05026"))
    )
    (comp (ref "U3")
      (value "4.7uH")
      (footprint "easyedapro:IND-SMD_L7.2-W6.6_GPSR07X0")
      (description "Inductance: Tolerance:±20% Tolerance:±20% Rated Current: DC Resistance (DCR):34.5mΩ")
      (fields (field (name "Manufacturer Part") "CYA0630-4.7UH") (field (name "Manufacturer") "SHOU HAN(首韩)"))
      (libsource (lib "easyedapro") (part "CYA0630-4.7UH"))
    )
    (comp (ref "U4")
      (value "TPS563201DDCR")
      (footprint "easyedapro:SOT-23-6_L2.9-W1.6-P0.95-LS2.8-BR")
      (fields (field (name "Manufacturer") "TI(德州仪器)"))
      (libsource (lib "easyedapro") (part "TPS563201DDCR"))
    )
    (comp (ref "U5")
      (value "IP5306")
      (footprint "easyedapro:ESOP-8_L4.9-W3.9-P1.27-LS6.0-BL-EP")
      (fields (field (name "Manufacturer") "INJOINIC(英集芯)"))
      (libsource (lib "easyedapro") (part "IP5306"))
    )
    (comp (ref "U6")
      (value "4.7uH")
      (footprint "easyedapro:IND-SMD_L7.2-W6.6_GPSR07X0")
      (description "Inductance: Tolerance:±20% Tolerance:±20% Rated Current: DC Resistance (DCR):34.5mΩ")
      (fields (field (name "Manufacturer Part") "CYA0630-4.7UH") (field (name "Manufacturer") "SHOU HAN(首韩)"))
      (libsource (lib "easyedapro") (part "CYA0630-4.7UH"))
    )
    (comp (ref "U7")
      (value "XB7608AJ")
      (footprint "easyedapro:CPC-5_L2.6-W2.6-P0.53-LS4.0-BL")
      (fields (field (name "Manufacturer") "xysemi(赛芯微)"))
      (libsource (lib "easyedapro") (part "XB7608AJ"))
    )
    (comp (ref "U8")
      (value "TPS563201DDCR")
      (footprint "easyedapro:SOT-23-6_L2.9-W1.6-P0.95-LS2.8-BR")
      (fields (field (name "Manufacturer") "TI(德州仪器)"))
      (libsource (lib "easyedapro") (part "TPS563201DDCR"))
    )
    (comp (ref "U9")
      (value "SS12D10G6-WJ")
      (footprint "easyedapro:SW-TH_3P-P4.80_HX-SS12D10G6-WJ")
      (fields (field (name "Manufacturer") "SHOU HAN(首韩)"))
      (libsource (lib "easyedapro") (part "SS12D10G6-WJ"))
    )
    (comp (ref "U10")
      (value "SS12D10G6-WJ")
      (footprint "easyedapro:SW-TH_3P-P4.80_HX-SS12D10G6-WJ")
      (fields (field (name "Manufacturer") "SHOU HAN(首韩)"))
      (libsource (lib "easyedapro") (part "SS12D10G6-WJ"))
    )
    (comp (ref "U11")
      (value "SS12D10G6-WJ")
      (footprint "easyedapro:SW-TH_3P-P4.80_HX-SS12D10G6-WJ")
      (fields (field (name "Manufacturer") "SHOU HAN(首韩)"))
      (libsource (lib "easyedapro") (part "SS12D10G6-WJ"))
    )
    (comp (ref "U12")
      (value "4.7uH")
      (footprint "easyedapro:IND-SMD_L7.2-W6.6_GPSR07X0")
      (description "Inductance: Tolerance:±20% Tolerance:±20% Rated Current: DC Resistance (DCR):34.5mΩ")
      (fields (field (name "Manufacturer Part") "CYA0630-4.7UH") (field (name "Manufacturer") "SHOU HAN(首韩)"))
      (libsource (lib "easyedapro") (part "CYA0630-4.7UH"))
    )
    (comp (ref "U13")
      (value "TPS563201DDCR")
      (footprint "easyedapro:SOT-23-6_L2.9-W1.6-P0.95-LS2.8-BR")
      (fields (field (name "Manufacturer") "TI(德州仪器)"))
      (libsource (lib "easyedapro") (part "TPS563201DDCR"))
    )
    (comp (ref "C118")
      (value "100nF")
      (footprint "easyedapro:C0603")
      (description "Capacitance:100nF Tolerance:±10% Tolerance:±10% Voltage Rating:50V Temperature Coefficient:X7R")
      (fields
        (field (name "Manufacturer Part") "CL10B104KB8NNNC")
        (field (name "Manufacturer") "SAMSUNG(三星)")
      )
      (libsource (lib "easyedapro") (part "CL10B104KB8NNNC"))
    )
    (comp (ref "C119")
      (value "100nF")
      (footprint "easyedapro:C0603")
      (description "Capacitance:100nF Tolerance:±10% Tolerance:±10% Voltage Rating:50V Temperature Coefficient:X7R")
      (fields
        (field (name "Manufacturer Part") "CL10B104KB8NNNC")
        (field (name "Manufacturer") "SAMSUNG(三星)")
      )
      (libsource (lib "easyedapro") (part "CL10B104KB8NNNC"))
    )
    (comp (ref "C121")
      (value "100nF")
      (footprint "easyedapro:C0603")
      (description "Capacitance:100nF Tolerance:±10% Tolerance:±10% Voltage Rating:50V Temperature Coefficient:X7R")
      (fields
        (field (name "Manufacturer Part") "CL10B104KB8NNNC")
        (field (name "Manufacturer") "SAMSUNG(三星)")
      )
      (libsource (lib "easyedapro") (part "CL10B104KB8NNNC"))
    )
    (comp (ref "C122")
      (value "100nF")
      (footprint "easyedapro:C0603")
      (description "Capacitance:100nF Tolerance:±10% Tolerance:±10% Voltage Rating:50V Temperature Coefficient:X7R")
      (fields
        (field (name "Manufacturer Part") "CL10B104KB8NNNC")
        (field (name "Manufacturer") "SAMSUNG(三星)")
      )
      (libsource (lib "easyedapro") (part "CL10B104KB8NNNC"))
    )
    (comp (ref "C123")
      (value "100nF")
      (footprint "easyedapro:C0603")
      (description "Capacitance:100nF Tolerance:±10% Tolerance:±10% Voltage Rating:50V Temperature Coefficient:X7R")
      (fields
        (field (name "Manufacturer Part") "CL10B104KB8NNNC")
        (field (name "Manufacturer") "SAMSUNG(三星)")
      )
      (libsource (lib "easyedapro") (part "CL10B104KB8NNNC"))
    )
    (comp (ref "C124")
      (value "100nF")
      (footprint "easyedapro:C0603")
      (description "Capacitance:100nF Tolerance:±10% Tolerance:±10% Voltage Rating:50V Temperature Coefficient:X7R")
      (fields
        (field (name "Manufacturer Part") "CL10B104KB8NNNC")
        (field (name "Manufacturer") "SAMSUNG(三星)")
      )
      (libsource (lib "easyedapro") (part "CL10B104KB8NNNC"))
    )
    (comp (ref "C125")
      (value "100nF")
      (footprint "easyedapro:C0603")
      (description "Capacitance:100nF Tolerance:±10% Tolerance:±10% Voltage Rating:50V Temperature Coefficient:X7R")
      (fields
        (field (name "Manufacturer Part") "CL10B104KB8NNNC")
        (field (name "Manufacturer") "SAMSUNG(三星)")
      )
      (libsource (lib "easyedapro") (part "CL10B104KB8NNNC"))
    )
    (comp (ref "C126")
      (value "100nF")
      (footprint "easyedapro:C0603")
      (description "Capacitance:100nF Tolerance:±10% Tolerance:±10% Voltage Rating:50V Temperature Coefficient:X7R")
      (fields
        (field (name "Manufacturer Part") "CL10B104KB8NNNC")
        (field (name "Manufacturer") "SAMSUNG(三星)")
      )
      (libsource (lib "easyedapro") (part "CL10B104KB8NNNC"))
    )
    (comp (ref "C127")
      (value "100nF")
      (footprint "easyedapro:C0603")
      (description "Capacitance:100nF Tolerance:±10% Tolerance:±10% Voltage Rating:50V Temperature Coefficient:X7R")
      (fields
        (field (name "Manufacturer Part") "CL10B104KB8NNNC")
        (field (name "Manufacturer") "SAMSUNG(三星)")
      )
      (libsource (lib "easyedapro") (part "CL10B104KB8NNNC"))
    )
    (comp (ref "C128")
      (value "100nF")
      (footprint "easyedapro:C0603")
      (description "Capacitance:100nF Tolerance:±10% Tolerance:±10% Voltage Rating:50V Temperature Coefficient:X7R")
      (fields
        (field (name "Manufacturer Part") "CL10B104KB8NNNC")
        (field (name "Manufacturer") "SAMSUNG(三星)")
      )
      (libsource (lib "easyedapro") (part "CL10B104KB8NNNC"))
    )
    (comp (ref "C129")
      (value "100nF")
      (footprint "easyedapro:C0603")
      (description "Capacitance:100nF Tolerance:±10% Tolerance:±10% Voltage Rating:50V Temperature Coefficient:X7R")
      (fields
        (field (name "Manufacturer Part") "CL10B104KB8NNNC")
        (field (name "Manufacturer") "SAMSUNG(三星)")
      )
      (libsource (lib "easyedapro") (part "CL10B104KB8NNNC"))
    )
    (comp (ref "C130")
      (value "100nF")
      (footprint "easyedapro:C0603")
      (description "Capacitance:100nF Tolerance:±10% Tolerance:±10% Voltage Rating:50V Temperature Coefficient:X7R")
      (fields
        (field (name "Manufacturer Part") "CL10B104KB8NNNC")
        (field (name "Manufacturer") "SAMSUNG(三星)")
      )
      (libsource (lib "easyedapro") (part "CL10B104KB8NNNC"))
    )
    (comp (ref "C131")
      (value "100nF")
      (footprint "easyedapro:C0603")
      (description "Capacitance:100nF Tolerance:±10% Tolerance:±10% Voltage Rating:50V Temperature Coefficient:X7R")
      (fields
        (field (name "Manufacturer Part") "CL10B104KB8NNNC")
        (field (name "Manufacturer") "SAMSUNG(三星)")
      )
      (libsource (lib "easyedapro") (part "CL10B104KB8NNNC"))
    )
    (comp (ref "C132")
      (value "100nF")
      (footprint "easyedapro:C0603")
      (description "Capacitance:100nF Tolerance:±10% Tolerance:±10% Voltage Rating:50V Temperature Coefficient:X7R")
      (fields
        (field (name "Manufacturer Part") "CL10B104KB8NNNC")
        (field (name "Manufacturer") "SAMSUNG(三星)")
      )
      (libsource (lib "easyedapro") (part "CL10B104KB8NNNC"))
    )
    (comp (ref "C133")
      (value "100nF")
      (footprint "easyedapro:C0603")
      (description "Capacitance:100nF Tolerance:±10% Tolerance:±10% Voltage Rating:50V Temperature Coefficient:X7R")
      (fields
        (field (name "Manufacturer Part") "CL10B104KB8NNNC")
        (field (name "Manufacturer") "SAMSUNG(三星)")
      )
      (libsource (lib "easyedapro") (part "CL10B104KB8NNNC"))
    )
    (comp (ref "C134")
      (value "100nF")
      (footprint "easyedapro:C0603")
      (description "Capacitance:100nF Tolerance:±10% Tolerance:±10% Voltage Rating:50V Temperature Coefficient:X7R")
      (fields
        (field (name "Manufacturer Part") "CL10B104KB8NNNC")
        (field (name "Manufacturer") "SAMSUNG(三星)")
      )
      (libsource (lib "easyedapro") (part "CL10B104KB8NNNC"))
    )
    (comp (ref "R93")
      (value "4.7kΩ")
      (footprint "easyedapro:R0603")
      (fields (field (name "Manufacturer Part") "RC0603FR-074K7L") (field (name "Manufacturer") "YAGEO(国巨)"))
      (libsource (lib "easyedapro") (part "RC0603FR-074K7L"))
    )
    (comp (ref "R94")
      (value "4.7kΩ")
      (footprint "easyedapro:R0603")
      (fields (field (name "Manufacturer Part") "RC0603FR-074K7L") (field (name "Manufacturer") "YAGEO(国巨)"))
      (libsource (lib "easyedapro") (part "RC0603FR-074K7L"))
    )
    (comp (ref "R95")
      (value "4.7kΩ")
      (footprint "easyedapro:R0603")
      (fields (field (name "Manufacturer Part") "RC0603FR-074K7L") (field (name "Manufacturer") "YAGEO(国巨)"))
      (libsource (lib "easyedapro") (part "RC0603FR-074K7L"))
    )
    (comp (ref "R96")
      (value "4.7kΩ")
      (footprint "easyedapro:R0603")
      (fields (field (name "Manufacturer Part") "RC0603FR-074K7L") (field (name "Manufacturer") "YAGEO(国巨)"))
      (libsource (lib "easyedapro") (part "RC0603FR-074K7L"))
    )
    (comp (ref "R97")
      (value "4.7kΩ")
      (footprint "easyedapro:R0603")
      (fields (field (name "Manufacturer Part") "RC0603FR-074K7L") (field (name "Manufacturer") "YAGEO(国巨)"))
      (libsource (lib "easyedapro") (part "RC0603FR-074K7L"))
    )
    (comp (ref "U14")
      (value "W9825G6KH-6")
      (footprint "easyedapro:TSOP-54_L22.2-W10.2-P0.80-LS11.8-BL")
      (fields (field (name "Manufacturer") "Winbond(华邦)"))
      (libsource (lib "easyedapro") (part "W9825G6KH-6"))
    )
    (comp (ref "U15")
      (value "W9825G6KH-6")
      (footprint "easyedapro:TSOP-54_L22.2-W10.2-P0.80-LS11.8-BL")
      (fields (field (name "Manufacturer") "Winbond(华邦)"))
      (libsource (lib "easyedapro") (part "W9825G6KH-6"))
    )
    (comp (ref "U16")
      (value "IS63WV1288DBLL-10HLI")
      (footprint "easyedapro:TSOPI-32_L18.4-W8.0-P0.50-LS20.0-TL")
      (description "Voltage - Supply:2.4V~3.6V Voltage - Supply:2.4V~3.6V Write Cycle Time(Tw):10ns")
      (fields (field (name "Manufacturer") "ISSI(美国芯成)"))
      (libsource (lib "easyedapro") (part "IS63WV1288DBLL-10HLI"))
    )
    (comp (ref "C95")
      (value "22uF")
      (footprint "easyedapro:C0805")
      (fields
        (field (name "Manufacturer Part") "GRM21BZ71A226ME15L")
        (field (name "Manufacturer") "muRata(村田)")
      )
      (libsource (lib "easyedapro") (part "GRM21BZ71A226ME15L"))
    )
    (comp (ref "C98")
      (value "10uF")
      (footprint "easyedapro:C0805")
      (description "Capacitance:10uF Tolerance:±10% Tolerance:±10% Voltage Rating:25V Temperature Coefficient:X5R")
      (fields
        (field (name "Manufacturer Part") "CL21A106KAYNNNE")
        (field (name "Manufacturer") "SAMSUNG(三星)")
      )
      (libsource (lib "easyedapro") (part "CL21A106KAYNNNE"))
    )
    (comp (ref "C135")
      (value "100nF")
      (footprint "easyedapro:C0603")
      (description "Capacitance:100nF Tolerance:±10% Tolerance:±10% Voltage Rating:50V Temperature Coefficient:X7R")
      (fields
        (field (name "Manufacturer Part") "CL10B104KB8NNNC")
        (field (name "Manufacturer") "SAMSUNG(三星)")
      )
      (libsource (lib "easyedapro") (part "CL10B104KB8NNNC"))
    )
    (comp (ref "C136")
      (value "100nF")
      (footprint "easyedapro:C0603")
      (description "Capacitance:100nF Tolerance:±10% Tolerance:±10% Voltage Rating:50V Temperature Coefficient:X7R")
      (fields
        (field (name "Manufacturer Part") "CL10B104KB8NNNC")
        (field (name "Manufacturer") "SAMSUNG(三星)")
      )
      (libsource (lib "easyedapro") (part "CL10B104KB8NNNC"))
    )
    (comp (ref "C137")
      (value "100nF")
      (footprint "easyedapro:C0603")
      (description "Capacitance:100nF Tolerance:±10% Tolerance:±10% Voltage Rating:50V Temperature Coefficient:X7R")
      (fields
        (field (name "Manufacturer Part") "CL10B104KB8NNNC")
        (field (name "Manufacturer") "SAMSUNG(三星)")
      )
      (libsource (lib "easyedapro") (part "CL10B104KB8NNNC"))
    )
    (comp (ref "C138")
      (value "100nF")
      (footprint "easyedapro:C0603")
      (description "Capacitance:100nF Tolerance:±10% Tolerance:±10% Voltage Rating:50V Temperature Coefficient:X7R")
      (fields
        (field (name "Manufacturer Part") "CL10B104KB8NNNC")
        (field (name "Manufacturer") "SAMSUNG(三星)")
      )
      (libsource (lib "easyedapro") (part "CL10B104KB8NNNC"))
    )
    (comp (ref "C139")
      (value "100nF")
      (footprint "easyedapro:C0603")
      (description "Capacitance:100nF Tolerance:±10% Tolerance:±10% Voltage Rating:50V Temperature Coefficient:X7R")
      (fields
        (field (name "Manufacturer Part") "CL10B104KB8NNNC")
        (field (name "Manufacturer") "SAMSUNG(三星)")
      )
      (libsource (lib "easyedapro") (part "CL10B104KB8NNNC"))
    )
    (comp (ref "C140")
      (value "100nF")
      (footprint "easyedapro:C0603")
      (description "Capacitance:100nF Tolerance:±10% Tolerance:±10% Voltage Rating:50V Temperature Coefficient:X7R")
      (fields
        (field (name "Manufacturer Part") "CL10B104KB8NNNC")
        (field (name "Manufacturer") "SAMSUNG(三星)")
      )
      (libsource (lib "easyedapro") (part "CL10B104KB8NNNC"))
    )
    (comp (ref "C141")
      (value "100nF")
      (footprint "easyedapro:C0603")
      (description "Capacitance:100nF Tolerance:±10% Tolerance:±10% Voltage Rating:50V Temperature Coefficient:X7R")
      (fields
        (field (name "Manufacturer Part") "CL10B104KB8NNNC")
        (field (name "Manufacturer") "SAMSUNG(三星)")
      )
      (libsource (lib "easyedapro") (part "CL10B104KB8NNNC"))
    )
    (comp (ref "C142")
      (value "100nF")
      (footprint "easyedapro:C0603")
      (description "Capacitance:100nF Tolerance:±10% Tolerance:±10% Voltage Rating:50V Temperature Coefficient:X7R")
      (fields
        (field (name "Manufacturer Part") "CL10B104KB8NNNC")
        (field (name "Manufacturer") "SAMSUNG(三星)")
      )
      (libsource (lib "easyedapro") (part "CL10B104KB8NNNC"))
    )
    (comp (ref "C148")
      (value "100nF")
      (footprint "easyedapro:C0603")
      (description "Capacitance:100nF Tolerance:±10% Tolerance:±10% Voltage Rating:50V Temperature Coefficient:X7R")
      (fields
        (field (name "Manufacturer Part") "CL10B104KB8NNNC")
        (field (name "Manufacturer") "SAMSUNG(三星)")
      )
      (libsource (lib "easyedapro") (part "CL10B104KB8NNNC"))
    )
    (comp (ref "C149")
      (value "100nF")
      (footprint "easyedapro:C0603")
      (description "Capacitance:100nF Tolerance:±10% Tolerance:±10% Voltage Rating:50V Temperature Coefficient:X7R")
      (fields
        (field (name "Manufacturer Part") "CL10B104KB8NNNC")
        (field (name "Manufacturer") "SAMSUNG(三星)")
      )
      (libsource (lib "easyedapro") (part "CL10B104KB8NNNC"))
    )
    (comp (ref "C150")
      (value "100nF")
      (footprint "easyedapro:C0603")
      (description "Capacitance:100nF Tolerance:±10% Tolerance:±10% Voltage Rating:50V Temperature Coefficient:X7R")
      (fields
        (field (name "Manufacturer Part") "CL10B104KB8NNNC")
        (field (name "Manufacturer") "SAMSUNG(三星)")
      )
      (libsource (lib "easyedapro") (part "CL10B104KB8NNNC"))
    )
    (comp (ref "C151")
      (value "100nF")
      (footprint "easyedapro:C0603")
      (description "Capacitance:100nF Tolerance:±10% Tolerance:±10% Voltage Rating:50V Temperature Coefficient:X7R")
      (fields
        (field (name "Manufacturer Part") "CL10B104KB8NNNC")
        (field (name "Manufacturer") "SAMSUNG(三星)")
      )
      (libsource (lib "easyedapro") (part "CL10B104KB8NNNC"))
    )
    (comp (ref "C152")
      (value "100nF")
      (footprint "easyedapro:C0603")
      (description "Capacitance:100nF Tolerance:±10% Tolerance:±10% Voltage Rating:50V Temperature Coefficient:X7R")
      (fields
        (field (name "Manufacturer Part") "CL10B104KB8NNNC")
        (field (name "Manufacturer") "SAMSUNG(三星)")
      )
      (libsource (lib "easyedapro") (part "CL10B104KB8NNNC"))
    )
    (comp (ref "C154")
      (value "22pF")
      (footprint "easyedapro:C0603")
      (description "Capacitance:22pF Tolerance:±5% Tolerance:±5% Voltage Rating:50V Temperature Coefficient:C0G")
      (fields
        (field (name "Manufacturer Part") "CL10C220JB8NNNC")
        (field (name "Manufacturer") "SAMSUNG(三星)")
      )
      (libsource (lib "easyedapro") (part "CL10C220JB8NNNC"))
    )
    (comp (ref "C155")
      (value "22pF")
      (footprint "easyedapro:C0603")
      (description "Capacitance:22pF Tolerance:±5% Tolerance:±5% Voltage Rating:50V Temperature Coefficient:C0G")
      (fields
        (field (name "Manufacturer Part") "CL10C220JB8NNNC")
        (field (name "Manufacturer") "SAMSUNG(三星)")
      )
      (libsource (lib "easyedapro") (part "CL10C220JB8NNNC"))
    )
    (comp (ref "C156")
      (value "22pF")
      (footprint "easyedapro:C0603")
      (description "Capacitance:22pF Tolerance:±5% Tolerance:±5% Voltage Rating:50V Temperature Coefficient:C0G")
      (fields
        (field (name "Manufacturer Part") "CL10C220JB8NNNC")
        (field (name "Manufacturer") "SAMSUNG(三星)")
      )
      (libsource (lib "easyedapro") (part "CL10C220JB8NNNC"))
    )
    (comp (ref "C157")
      (value "22pF")
      (footprint "easyedapro:C0603")
      (description "Capacitance:22pF Tolerance:±5% Tolerance:±5% Voltage Rating:50V Temperature Coefficient:C0G")
      (fields
        (field (name "Manufacturer Part") "CL10C220JB8NNNC")
        (field (name "Manufacturer") "SAMSUNG(三星)")
      )
      (libsource (lib "easyedapro") (part "CL10C220JB8NNNC"))
    )
    (comp (ref "C158")
      (value "22pF")
      (footprint "easyedapro:C0603")
      (description "Capacitance:22pF Tolerance:±5% Tolerance:±5% Voltage Rating:50V Temperature Coefficient:C0G")
      (fields
        (field (name "Manufacturer Part") "CL10C220JB8NNNC")
        (field (name "Manufacturer") "SAMSUNG(三星)")
      )
      (libsource (lib "easyedapro") (part "CL10C220JB8NNNC"))
    )
    (comp (ref "C159")
      (value "22pF")
      (footprint "easyedapro:C0603")
      (description "Capacitance:22pF Tolerance:±5% Tolerance:±5% Voltage Rating:50V Temperature Coefficient:C0G")
      (fields
        (field (name "Manufacturer Part") "CL10C220JB8NNNC")
        (field (name "Manufacturer") "SAMSUNG(三星)")
      )
      (libsource (lib "easyedapro") (part "CL10C220JB8NNNC"))
    )
    (comp (ref "C163")
      (value "100nF")
      (footprint "easyedapro:C0603")
      (description "Capacitance:100nF Tolerance:±10% Tolerance:±10% Voltage Rating:50V Temperature Coefficient:X7R")
      (fields
        (field (name "Manufacturer Part") "CL10B104KB8NNNC")
        (field (name "Manufacturer") "SAMSUNG(三星)")
      )
      (libsource (lib "easyedapro") (part "CL10B104KB8NNNC"))
    )
    (comp (ref "C164")
      (value "100nF")
      (footprint "easyedapro:C0603")
      (description "Capacitance:100nF Tolerance:±10% Tolerance:±10% Voltage Rating:50V Temperature Coefficient:X7R")
      (fields
        (field (name "Manufacturer Part") "CL10B104KB8NNNC")
        (field (name "Manufacturer") "SAMSUNG(三星)")
      )
      (libsource (lib "easyedapro") (part "CL10B104KB8NNNC"))
    )
    (comp (ref "C173")
      (value "100nF")
      (footprint "easyedapro:C0603")
      (description "Capacitance:100nF Tolerance:±10% Tolerance:±10% Voltage Rating:50V Temperature Coefficient:X7R")
      (fields
        (field (name "Manufacturer Part") "CL10B104KB8NNNC")
        (field (name "Manufacturer") "SAMSUNG(三星)")
      )
      (libsource (lib "easyedapro") (part "CL10B104KB8NNNC"))
    )
    (comp (ref "C174")
      (value "100nF")
      (footprint "easyedapro:C0603")
      (description "Capacitance:100nF Tolerance:±10% Tolerance:±10% Voltage Rating:50V Temperature Coefficient:X7R")
      (fields
        (field (name "Manufacturer Part") "CL10B104KB8NNNC")
        (field (name "Manufacturer") "SAMSUNG(三星)")
      )
      (libsource (lib "easyedapro") (part "CL10B104KB8NNNC"))
    )
    (comp (ref "C175")
      (value "100nF")
      (footprint "easyedapro:C0603")
      (description "Capacitance:100nF Tolerance:±10% Tolerance:±10% Voltage Rating:50V Temperature Coefficient:X7R")
      (fields
        (field (name "Manufacturer Part") "CL10B104KB8NNNC")
        (field (name "Manufacturer") "SAMSUNG(三星)")
      )
      (libsource (lib "easyedapro") (part "CL10B104KB8NNNC"))
    )
    (comp (ref "C176")
      (value "100nF")
      (footprint "easyedapro:C0603")
      (description "Capacitance:100nF Tolerance:±10% Tolerance:±10% Voltage Rating:50V Temperature Coefficient:X7R")
      (fields
        (field (name "Manufacturer Part") "CL10B104KB8NNNC")
        (field (name "Manufacturer") "SAMSUNG(三星)")
      )
      (libsource (lib "easyedapro") (part "CL10B104KB8NNNC"))
    )
    (comp (ref "C178")
      (value "100nF")
      (footprint "easyedapro:C0603")
      (description "Capacitance:100nF Tolerance:±10% Tolerance:±10% Voltage Rating:50V Temperature Coefficient:X7R")
      (fields
        (field (name "Manufacturer Part") "CL10B104KB8NNNC")
        (field (name "Manufacturer") "SAMSUNG(三星)")
      )
      (libsource (lib "easyedapro") (part "CL10B104KB8NNNC"))
    )
    (comp (ref "CARD1")
      (value "TF PUSH")
      (footprint "easyedapro:TF-SMD_TF-PUSH")
      (fields (field (name "Manufacturer") "SHOU HAN(首韩)"))
      (libsource (lib "easyedapro") (part "TF PUSH"))
    )
    (comp (ref "D1")
      (value "SRV05-4")
      (footprint "easyedapro:SOT-23-6_L2.9-W1.6-P0.95-LS2.8-BL")
      (fields (field (name "Manufacturer") "TECH PUBLIC(台舟)"))
      (libsource (lib "easyedapro") (part "SRV05-4_C558418"))
    )
    (comp (ref "D2")
      (value "SRV05-4")
      (footprint "easyedapro:SOT-23-6_L2.9-W1.6-P0.95-LS2.8-BL")
      (fields (field (name "Manufacturer") "TECH PUBLIC(台舟)"))
      (libsource (lib "easyedapro") (part "SRV05-4_C558418"))
    )
    (comp (ref "D3")
      (value "SRV05-4")
      (footprint "easyedapro:SOT-23-6_L2.9-W1.6-P0.95-LS2.8-BL")
      (fields (field (name "Manufacturer") "TECH PUBLIC(台舟)"))
      (libsource (lib "easyedapro") (part "SRV05-4_C558418"))
    )
    (comp (ref "D4")
      (value "SS34")
      (footprint "easyedapro:SMA_L4.2-W2.7-LS5.0-RD")
      (fields (field (name "Manufacturer") "JSMSEMI(杰盛微)"))
      (libsource (lib "easyedapro") (part "SS34_C2837271"))
    )
    (comp (ref "H1")
      (value "PZ254V-12-24P")
      (footprint "easyedapro:HDR-TH_24P-P2.54-V-M-R2-C12-S2.54")
      (fields (field (name "Manufacturer") "XFCN(兴飞)"))
      (libsource (lib "easyedapro") (part "PZ254V-12-24P"))
    )
    (comp (ref "H2")
      (value "PZ254V-11-03P")
      (footprint "easyedapro:HDR-TH_3P-P2.54-V-M")
      (fields (field (name "Manufacturer") "XFCN(兴飞)"))
      (libsource (lib "easyedapro") (part "PZ254V-11-03P_C2937625"))
    )
    (comp (ref "H3")
      (value "PZ254V-12-8P")
      (footprint "easyedapro:HDR-TH_8P-P2.54-V-M-R2-C4-S2.54")
      (fields (field (name "Manufacturer") "XFCN(兴飞)"))
      (libsource (lib "easyedapro") (part "PZ254V-12-8P"))
    )
    (comp (ref "HDMI1")
      (value "HDMI 19PIN 043")
      (footprint "easyedapro:HDMI-SMD_HDMI-19PIN-043")
      (fields (field (name "Manufacturer") "SHOU HAN(首韩)"))
      (libsource (lib "easyedapro") (part "HDMI 19PIN 043"))
    )
    (comp (ref "J1")
      (value "HR911105A")
      (footprint "easyedapro:RJ45-TH_HR911105A")
      (fields (field (name "Manufacturer") "HANRUN(汉仁)"))
      (libsource (lib "easyedapro") (part "HR911105A_C12074"))
    )
    (comp (ref "L2")
      (value "BLM21PG221SN1D")
      (footprint "easyedapro:L0805")
      (fields (field (name "Manufacturer") "muRata(村田)"))
      (libsource (lib "easyedapro") (part "BLM21PG221SN1D"))
    )
    (comp (ref "LED6")
      (value "XL-2012SURC")
      (footprint "easyedapro:LED0805-RD_RED")
      (fields (field (name "Manufacturer") "XINGLIGHT(成兴光)"))
      (libsource (lib "easyedapro") (part "XL-2012SURC"))
    )
    (comp (ref "LED7")
      (value "XL-2012SURC")
      (footprint "easyedapro:LED0805-RD_RED")
      (fields (field (name "Manufacturer") "XINGLIGHT(成兴光)"))
      (libsource (lib "easyedapro") (part "XL-2012SURC"))
    )
    (comp (ref "LED8")
      (value "XL-2012SURC")
      (footprint "easyedapro:LED0805-RD_RED")
      (fields (field (name "Manufacturer") "XINGLIGHT(成兴光)"))
      (libsource (lib "easyedapro") (part "XL-2012SURC"))
    )
    (comp (ref "LED9")
      (value "XL-2012SURC")
      (footprint "easyedapro:LED0805-RD_RED")
      (fields (field (name "Manufacturer") "XINGLIGHT(成兴光)"))
      (libsource (lib "easyedapro") (part "XL-2012SURC"))
    )
    (comp (ref "LED10")
      (value "XL-2012SURC")
      (footprint "easyedapro:LED0805-RD_RED")
      (fields (field (name "Manufacturer") "XINGLIGHT(成兴光)"))
      (libsource (lib "easyedapro") (part "XL-2012SURC"))
    )
    (comp (ref "LED11")
      (value "XL-2012SURC")
      (footprint "easyedapro:LED0805-RD_RED")
      (fields (field (name "Manufacturer") "XINGLIGHT(成兴光)"))
      (libsource (lib "easyedapro") (part "XL-2012SURC"))
    )
    (comp (ref "LED12")
      (value "XL-2012SURC")
      (footprint "easyedapro:LED0805-RD_RED")
      (fields (field (name "Manufacturer") "XINGLIGHT(成兴光)"))
      (libsource (lib "easyedapro") (part "XL-2012SURC"))
    )
    (comp (ref "LED13")
      (value "XL-2012SURC")
      (footprint "easyedapro:LED0805-RD_RED")
      (fields (field (name "Manufacturer") "XINGLIGHT(成兴光)"))
      (libsource (lib "easyedapro") (part "XL-2012SURC"))
    )
    (comp (ref "R98")
      (value "5.1kΩ")
      (footprint "easyedapro:R0603")
      (fields (field (name "Manufacturer Part") "FRC0603F5101TS") (field (name "Manufacturer") "FOJAN(富捷)"))
      (libsource (lib "easyedapro") (part "FRC0603F5101TS"))
    )
    (comp (ref "R99")
      (value "5.1kΩ")
      (footprint "easyedapro:R0603")
      (fields (field (name "Manufacturer Part") "FRC0603F5101TS") (field (name "Manufacturer") "FOJAN(富捷)"))
      (libsource (lib "easyedapro") (part "FRC0603F5101TS"))
    )
    (comp (ref "R100")
      (value "4.7kΩ")
      (footprint "easyedapro:R0603")
      (fields (field (name "Manufacturer Part") "RC0603FR-074K7L") (field (name "Manufacturer") "YAGEO(国巨)"))
      (libsource (lib "easyedapro") (part "RC0603FR-074K7L"))
    )
    (comp (ref "R101")
      (value "4.7kΩ")
      (footprint "easyedapro:R0603")
      (fields (field (name "Manufacturer Part") "RC0603FR-074K7L") (field (name "Manufacturer") "YAGEO(国巨)"))
      (libsource (lib "easyedapro") (part "RC0603FR-074K7L"))
    )
    (comp (ref "R102")
      (value "10kΩ")
      (footprint "easyedapro:R0603")
      (fields (field (name "Manufacturer Part") "FRC0603F1002TS") (field (name "Manufacturer") "FOJAN(富捷)"))
      (libsource (lib "easyedapro") (part "FRC0603F1002TS"))
    )
    (comp (ref "R103")
      (value "10kΩ")
      (footprint "easyedapro:R0603")
      (fields (field (name "Manufacturer Part") "FRC0603F1002TS") (field (name "Manufacturer") "FOJAN(富捷)"))
      (libsource (lib "easyedapro") (part "FRC0603F1002TS"))
    )
    (comp (ref "R104")
      (value "10kΩ")
      (footprint "easyedapro:R0603")
      (fields (field (name "Manufacturer Part") "FRC0603F1002TS") (field (name "Manufacturer") "FOJAN(富捷)"))
      (libsource (lib "easyedapro") (part "FRC0603F1002TS"))
    )
    (comp (ref "R105")
      (value "10kΩ")
      (footprint "easyedapro:R0603")
      (fields (field (name "Manufacturer Part") "FRC0603F1002TS") (field (name "Manufacturer") "FOJAN(富捷)"))
      (libsource (lib "easyedapro") (part "FRC0603F1002TS"))
    )
    (comp (ref "R106")
      (value "10kΩ")
      (footprint "easyedapro:R0603")
      (fields (field (name "Manufacturer Part") "FRC0603F1002TS") (field (name "Manufacturer") "FOJAN(富捷)"))
      (libsource (lib "easyedapro") (part "FRC0603F1002TS"))
    )
    (comp (ref "R107")
      (value "10kΩ")
      (footprint "easyedapro:R0603")
      (fields (field (name "Manufacturer Part") "FRC0603F1002TS") (field (name "Manufacturer") "FOJAN(富捷)"))
      (libsource (lib "easyedapro") (part "FRC0603F1002TS"))
    )
    (comp (ref "R108")
      (value "10kΩ")
      (footprint "easyedapro:R0603")
      (fields (field (name "Manufacturer Part") "FRC0603F1002TS") (field (name "Manufacturer") "FOJAN(富捷)"))
      (libsource (lib "easyedapro") (part "FRC0603F1002TS"))
    )
    (comp (ref "R109")
      (value "10kΩ")
      (footprint "easyedapro:R0603")
      (fields (field (name "Manufacturer Part") "FRC0603F1002TS") (field (name "Manufacturer") "FOJAN(富捷)"))
      (libsource (lib "easyedapro") (part "FRC0603F1002TS"))
    )
    (comp (ref "R110")
      (value "20kΩ")
      (footprint "easyedapro:R0603")
      (fields (field (name "Manufacturer Part") "FRC0603F2002TS") (field (name "Manufacturer") "FOJAN(富捷)"))
      (libsource (lib "easyedapro") (part "FRC0603F2002TS"))
    )
    (comp (ref "R111")
      (value "20kΩ")
      (footprint "easyedapro:R0603")
      (fields (field (name "Manufacturer Part") "FRC0603F2002TS") (field (name "Manufacturer") "FOJAN(富捷)"))
      (libsource (lib "easyedapro") (part "FRC0603F2002TS"))
    )
    (comp (ref "R112")
      (value "20kΩ")
      (footprint "easyedapro:R0603")
      (fields (field (name "Manufacturer Part") "FRC0603F2002TS") (field (name "Manufacturer") "FOJAN(富捷)"))
      (libsource (lib "easyedapro") (part "FRC0603F2002TS"))
    )
    (comp (ref "R113")
      (value "20kΩ")
      (footprint "easyedapro:R0603")
      (fields (field (name "Manufacturer Part") "FRC0603F2002TS") (field (name "Manufacturer") "FOJAN(富捷)"))
      (libsource (lib "easyedapro") (part "FRC0603F2002TS"))
    )
    (comp (ref "R114")
      (value "20kΩ")
      (footprint "easyedapro:R0603")
      (fields (field (name "Manufacturer Part") "FRC0603F2002TS") (field (name "Manufacturer") "FOJAN(富捷)"))
      (libsource (lib "easyedapro") (part "FRC0603F2002TS"))
    )
    (comp (ref "R115")
      (value "20kΩ")
      (footprint "easyedapro:R0603")
      (fields (field (name "Manufacturer Part") "FRC0603F2002TS") (field (name "Manufacturer") "FOJAN(富捷)"))
      (libsource (lib "easyedapro") (part "FRC0603F2002TS"))
    )
    (comp (ref "R116")
      (value "20kΩ")
      (footprint "easyedapro:R0603")
      (fields (field (name "Manufacturer Part") "FRC0603F2002TS") (field (name "Manufacturer") "FOJAN(富捷)"))
      (libsource (lib "easyedapro") (part "FRC0603F2002TS"))
    )
    (comp (ref "R117")
      (value "20kΩ")
      (footprint "easyedapro:R0603")
      (fields (field (name "Manufacturer Part") "FRC0603F2002TS") (field (name "Manufacturer") "FOJAN(富捷)"))
      (libsource (lib "easyedapro") (part "FRC0603F2002TS"))
    )
    (comp (ref "R118")
      (value "20kΩ")
      (footprint "easyedapro:R0603")
      (fields (field (name "Manufacturer Part") "FRC0603F2002TS") (field (name "Manufacturer") "FOJAN(富捷)"))
      (libsource (lib "easyedapro") (part "FRC0603F2002TS"))
    )
    (comp (ref "R120")
      (value "10kΩ")
      (footprint "easyedapro:R0603")
      (fields (field (name "Manufacturer Part") "FRC0603F1002TS") (field (name "Manufacturer") "FOJAN(富捷)"))
      (libsource (lib "easyedapro") (part "FRC0603F1002TS"))
    )
    (comp (ref "R121")
      (value "10kΩ")
      (footprint "easyedapro:R0603")
      (fields (field (name "Manufacturer Part") "FRC0603F1002TS") (field (name "Manufacturer") "FOJAN(富捷)"))
      (libsource (lib "easyedapro") (part "FRC0603F1002TS"))
    )
    (comp (ref "R122")
      (value "10kΩ")
      (footprint "easyedapro:R0603")
      (fields (field (name "Manufacturer Part") "FRC0603F1002TS") (field (name "Manufacturer") "FOJAN(富捷)"))
      (libsource (lib "easyedapro") (part "FRC0603F1002TS"))
    )
    (comp (ref "R123")
      (value "10kΩ")
      (footprint "easyedapro:R0603")
      (fields (field (name "Manufacturer Part") "FRC0603F1002TS") (field (name "Manufacturer") "FOJAN(富捷)"))
      (libsource (lib "easyedapro") (part "FRC0603F1002TS"))
    )
    (comp (ref "R124")
      (value "10kΩ")
      (footprint "easyedapro:R0603")
      (fields (field (name "Manufacturer Part") "FRC0603F1002TS") (field (name "Manufacturer") "FOJAN(富捷)"))
      (libsource (lib "easyedapro") (part "FRC0603F1002TS"))
    )
    (comp (ref "R128")
      (value "4.7kΩ")
      (footprint "easyedapro:R0603")
      (fields (field (name "Manufacturer Part") "RC0603FR-074K7L") (field (name "Manufacturer") "YAGEO(国巨)"))
      (libsource (lib "easyedapro") (part "RC0603FR-074K7L"))
    )
    (comp (ref "R129")
      (value "4.7kΩ")
      (footprint "easyedapro:R0603")
      (fields (field (name "Manufacturer Part") "RC0603FR-074K7L") (field (name "Manufacturer") "YAGEO(国巨)"))
      (libsource (lib "easyedapro") (part "RC0603FR-074K7L"))
    )
    (comp (ref "R130")
      (value "4.7kΩ")
      (footprint "easyedapro:R0603")
      (fields (field (name "Manufacturer Part") "RC0603FR-074K7L") (field (name "Manufacturer") "YAGEO(国巨)"))
      (libsource (lib "easyedapro") (part "RC0603FR-074K7L"))
    )
    (comp (ref "R131")
      (value "4.7kΩ")
      (footprint "easyedapro:R0603")
      (fields (field (name "Manufacturer Part") "RC0603FR-074K7L") (field (name "Manufacturer") "YAGEO(国巨)"))
      (libsource (lib "easyedapro") (part "RC0603FR-074K7L"))
    )
    (comp (ref "R132")
      (value "4.7kΩ")
      (footprint "easyedapro:R0603")
      (fields (field (name "Manufacturer Part") "RC0603FR-074K7L") (field (name "Manufacturer") "YAGEO(国巨)"))
      (libsource (lib "easyedapro") (part "RC0603FR-074K7L"))
    )
    (comp (ref "R133")
      (value "4.7kΩ")
      (footprint "easyedapro:R0603")
      (fields (field (name "Manufacturer Part") "RC0603FR-074K7L") (field (name "Manufacturer") "YAGEO(国巨)"))
      (libsource (lib "easyedapro") (part "RC0603FR-074K7L"))
    )
    (comp (ref "R134")
      (value "10kΩ")
      (footprint "easyedapro:R0603")
      (fields (field (name "Manufacturer Part") "FRC0603F1002TS") (field (name "Manufacturer") "FOJAN(富捷)"))
      (libsource (lib "easyedapro") (part "FRC0603F1002TS"))
    )
    (comp (ref "R135")
      (value "10kΩ")
      (footprint "easyedapro:R0603")
      (fields (field (name "Manufacturer Part") "FRC0603F1002TS") (field (name "Manufacturer") "FOJAN(富捷)"))
      (libsource (lib "easyedapro") (part "FRC0603F1002TS"))
    )
    (comp (ref "R136")
      (value "10kΩ")
      (footprint "easyedapro:R0603")
      (fields (field (name "Manufacturer Part") "FRC0603F1002TS") (field (name "Manufacturer") "FOJAN(富捷)"))
      (libsource (lib "easyedapro") (part "FRC0603F1002TS"))
    )
    (comp (ref "R137")
      (value "10kΩ")
      (footprint "easyedapro:R0603")
      (fields (field (name "Manufacturer Part") "FRC0603F1002TS") (field (name "Manufacturer") "FOJAN(富捷)"))
      (libsource (lib "easyedapro") (part "FRC0603F1002TS"))
    )
    (comp (ref "R138")
      (value "10kΩ")
      (footprint "easyedapro:R0603")
      (fields (field (name "Manufacturer Part") "FRC0603F1002TS") (field (name "Manufacturer") "FOJAN(富捷)"))
      (libsource (lib "easyedapro") (part "FRC0603F1002TS"))
    )
    (comp (ref "R139")
      (value "10kΩ")
      (footprint "easyedapro:R0603")
      (fields (field (name "Manufacturer Part") "FRC0603F1002TS") (field (name "Manufacturer") "FOJAN(富捷)"))
      (libsource (lib "easyedapro") (part "FRC0603F1002TS"))
    )
    (comp (ref "R146")
      (value "1kΩ")
      (footprint "easyedapro:R0603")
      (fields (field (name "Manufacturer Part") "FRC0603F1001TS") (field (name "Manufacturer") "FOJAN(富捷)"))
      (libsource (lib "easyedapro") (part "FRC0603F1001TS"))
    )
    (comp (ref "R147")
      (value "1kΩ")
      (footprint "easyedapro:R0603")
      (fields (field (name "Manufacturer Part") "FRC0603F1001TS") (field (name "Manufacturer") "FOJAN(富捷)"))
      (libsource (lib "easyedapro") (part "FRC0603F1001TS"))
    )
    (comp (ref "R151")
      (value "2.32kΩ")
      (footprint "easyedapro:R0603")
      (fields (field (name "Manufacturer Part") "RC0603FR-072K32L") (field (name "Manufacturer") "YAGEO(国巨)"))
      (libsource (lib "easyedapro") (part "RC0603FR-072K32L"))
    )
    (comp (ref "R152")
      (value "49.9Ω")
      (footprint "easyedapro:R0603")
      (fields (field (name "Manufacturer Part") "FRC0603F49R9TS") (field (name "Manufacturer") "FOJAN(富捷)"))
      (libsource (lib "easyedapro") (part "FRC0603F49R9TS"))
    )
    (comp (ref "R153")
      (value "49.9Ω")
      (footprint "easyedapro:R0603")
      (fields (field (name "Manufacturer Part") "FRC0603F49R9TS") (field (name "Manufacturer") "FOJAN(富捷)"))
      (libsource (lib "easyedapro") (part "FRC0603F49R9TS"))
    )
    (comp (ref "R154")
      (value "49.9Ω")
      (footprint "easyedapro:R0603")
      (fields (field (name "Manufacturer Part") "FRC0603F49R9TS") (field (name "Manufacturer") "FOJAN(富捷)"))
      (libsource (lib "easyedapro") (part "FRC0603F49R9TS"))
    )
    (comp (ref "R155")
      (value "49.9Ω")
      (footprint "easyedapro:R0603")
      (fields (field (name "Manufacturer Part") "FRC0603F49R9TS") (field (name "Manufacturer") "FOJAN(富捷)"))
      (libsource (lib "easyedapro") (part "FRC0603F49R9TS"))
    )
    (comp (ref "SCREW1")
      (value "~")
      (footprint "easyedapro:Screw-Hole-M3")
      (libsource (lib "easyedapro") (part "Screw-Hole"))
    )
    (comp (ref "SCREW2")
      (value "~")
      (footprint "easyedapro:Screw-Hole-M3")
      (libsource (lib "easyedapro") (part "Screw-Hole"))
    )
    (comp (ref "SCREW3")
      (value "~")
      (footprint "easyedapro:Screw-Hole-M3")
      (libsource (lib "easyedapro") (part "Screw-Hole"))
    )
    (comp (ref "SCREW4")
      (value "~")
      (footprint "easyedapro:Screw-Hole-M3")
      (libsource (lib "easyedapro") (part "Screw-Hole"))
    )
    (comp (ref "SW4")
      (value "TS-1009B-05026")
      (footprint "easyedapro:SW-TH_3P-L4.5-W3.8-P3.10-LS1.9")
      (fields (field (name "Manufacturer") "XUNPU(讯普)"))
      (libsource (lib "easyedapro") (part "TS-1009B-05026"))
    )
    (comp (ref "SW5")
      (value "2.54-4P TPGT")
      (footprint "easyedapro:SW-SMD_8P-L10.2-W6.2-P2.54-LS9.4")
      (fields (field (name "Manufacturer") "SHOU HAN(首韩)"))
      (libsource (lib "easyedapro") (part "2.54-4P TPGT"))
    )
    (comp (ref "U18")
      (value "CH376T")
      (footprint "easyedapro:SSOP-20_L7.5-W5.2-P0.65-LS8.0-BL")
      (fields (field (name "Manufacturer") "WCH(南京沁恒)"))
      (libsource (lib "easyedapro") (part "CH376T"))
    )
    (comp (ref "U19")
      (value "CH376T")
      (footprint "easyedapro:SSOP-20_L7.5-W5.2-P0.65-LS8.0-BL")
      (fields (field (name "Manufacturer") "WCH(南京沁恒)"))
      (libsource (lib "easyedapro") (part "CH376T"))
    )
    (comp (ref "U22")
      (value "W25Q128JVSIQ")
      (footprint "easyedapro:SOIC-8_L5.3-W5.3-P1.27-LS8.0-BL")
      (fields (field (name "Manufacturer") "Winbond(华邦)"))
      (libsource (lib "easyedapro") (part "W25Q128JVSIQ"))
    )
    (comp (ref "U23")
      (value "CH340C")
      (footprint "easyedapro:SOP-16_L10.0-W3.9-P1.27-LS6.0-BL")
      (fields (field (name "Manufacturer") "WCH(南京沁恒)"))
      (libsource (lib "easyedapro") (part "CH340C"))
    )
    (comp (ref "U24")
      (value "W25Q128JVSIQ")
      (footprint "easyedapro:SOIC-8_L5.3-W5.3-P1.27-LS8.0-BL")
      (fields (field (name "Manufacturer") "Winbond(华邦)"))
      (libsource (lib "easyedapro") (part "W25Q128JVSIQ"))
    )
    (comp (ref "U26")
      (value "ENC28J60-I/SS")
      (footprint "easyedapro:SSOP-28_L10.2-W5.3-P0.65-LS7.8-BL")
      (fields (field (name "Manufacturer") "MICROCHIP(美国微芯)"))
      (libsource (lib "easyedapro") (part "ENC28J60-I/SS"))
    )
    (comp (ref "USB1")
      (value "AF SS-JB17.6")
      (footprint "easyedapro:USB-A-TH_AF-SS-JB17.6")
      (fields (field (name "Manufacturer") "SHOU HAN(首韩)"))
      (libsource (lib "easyedapro") (part "AF SS-JB17.6"))
    )
    (comp (ref "USB2")
      (value "TYPE-C 16PIN 2MD(073)")
      (footprint "easyedapro:USB-C-SMD_TYPE-C-6PIN-2MD-073")
      (fields (field (name "Manufacturer") "SHOU HAN(首韩)"))
      (libsource (lib "easyedapro") (part "TYPE-C 16PIN 2MD(073)"))
    )
    (comp (ref "X5")
      (value "12MHz")
      (footprint "easyedapro:CRYSTAL-SMD_4P-L3.2-W2.5-BL")
      (fields (field (name "Manufacturer Part") "X322512MSB4SI") (field (name "Manufacturer") "YXC(扬兴晶振)"))
      (libsource (lib "easyedapro") (part "X322512MSB4SI"))
    )
    (comp (ref "X6")
      (value "12MHz")
      (footprint "easyedapro:CRYSTAL-SMD_4P-L3.2-W2.5-BL")
      (fields (field (name "Manufacturer Part") "X322512MSB4SI") (field (name "Manufacturer") "YXC(扬兴晶振)"))
      (libsource (lib "easyedapro") (part "X322512MSB4SI"))
    )
    (comp (ref "X8")
      (value "25MHz")
      (footprint "easyedapro:CRYSTAL-SMD_4P-L3.2-W2.5-BL-2")
      (fields (field (name "Manufacturer Part") "X322525MSB4SI") (field (name "Manufacturer") "YXC(扬兴晶振)"))
      (libsource (lib "easyedapro") (part "X322525MSB4SI"))
    )
  )
  (nets
    (net (code "1") (name "1V2") (class "Default")
      (node (ref "C10") (pin "1") (pinfunction "1_1") (pintype "unspecified"))
      (node (ref "C12") (pin "1") (pinfunction "1_1") (pintype "unspecified"))
      (node (ref "C14") (pin "1") (pinfunction "1_1") (pintype "unspecified"))
      (node (ref "C17") (pin "1") (pinfunction "1_1") (pintype "unspecified"))
      (node (ref "C19") (pin "1") (pinfunction "1_1") (pintype "unspecified"))
      (node (ref "C21") (pin "1") (pinfunction "1_1") (pintype "unspecified"))
      (node (ref "C23") (pin "1") (pinfunction "1_1") (pintype "unspecified"))
      (node (ref "C58") (pin "2") (pinfunction "2_2") (pintype "unspecified"))
      (node (ref "C59") (pin "2") (pinfunction "2_2") (pintype "unspecified"))
      (node (ref "C7") (pin "1") (pinfunction "1_1") (pintype "unspecified"))
      (node (ref "R38") (pin "2") (pinfunction "2_2") (pintype "input"))
      (node (ref "U12") (pin "1") (pinfunction "1_1") (pintype "input"))
      (node (ref "U25") (pin "E17") (pinfunction "VCCD_PLL2_E17") (pintype "unspecified"))
      (node (ref "U25") (pin "F6") (pinfunction "VCCD_PLL3_F6") (pintype "unspecified"))
      (node (ref "U25") (pin "G12") (pinfunction "VCCINT_G12") (pintype "unspecified"))
      (node (ref "U25") (pin "H9") (pinfunction "VCCINT_H9") (pintype "unspecified"))
      (node (ref "U25") (pin "J10") (pinfunction "VCCINT_J10") (pintype "unspecified"))
      (node (ref "U25") (pin "J11") (pinfunction "VCCINT_J11") (pintype "unspecified"))
      (node (ref "U25") (pin "J12") (pinfunction "VCCINT_J12") (pintype "unspecified"))
      (node (ref "U25") (pin "J13") (pinfunction "VCCINT_J13") (pintype "unspecified"))
      (node (ref "U25") (pin "J14") (pinfunction "VCCINT_J14") (pintype "unspecified"))
      (node (ref "U25") (pin "J16") (pinfunction "VCCINT_J16") (pintype "unspecified"))
      (node (ref "U25") (pin "K14") (pinfunction "VCCINT_K14") (pintype "unspecified"))
      (node (ref "U25") (pin "K15") (pinfunction "VCCINT_K15") (pintype "unspecified"))
      (node (ref "U25") (pin "K9") (pinfunction "VCCINT_K9") (pintype "unspecified"))
      (node (ref "U25") (pin "L14") (pinfunction "VCCINT_L14") (pintype "unspecified"))
      (node (ref "U25") (pin "L16") (pinfunction "VCCINT_L16") (pintype "unspecified"))
      (node (ref "U25") (pin "L9") (pinfunction "VCCINT_L9") (pintype "unspecified"))
      (node (ref "U25") (pin "M14") (pinfunction "VCCINT_M14") (pintype "unspecified"))
      (node (ref "U25") (pin "M15") (pinfunction "VCCINT_M15") (pintype "unspecified"))
      (node (ref "U25") (pin "M9") (pinfunction "VCCINT_M9") (pintype "unspecified"))
      (node (ref "U25") (pin "N14") (pinfunction "VCCINT_N14") (pintype "unspecified"))
      (node (ref "U25") (pin "N9") (pinfunction "VCCINT_N9") (pintype "unspecified"))
      (node (ref "U25") (pin "P10") (pinfunction "VCCINT_P10") (pintype "unspecified"))
      (node (ref "U25") (pin "P11") (pinfunction "VCCINT_P11") (pintype "unspecified"))
      (node (ref "U25") (pin "P12") (pinfunction "VCCINT_P12") (pintype "unspecified"))
      (node (ref "U25") (pin "P13") (pinfunction "VCCINT_P13") (pintype "unspecified"))
      (node (ref "U25") (pin "P14") (pinfunction "VCCINT_P14") (pintype "unspecified"))
      (node (ref "U25") (pin "P9") (pinfunction "VCCINT_P9") (pintype "unspecified"))
      (node (ref "U25") (pin "R10") (pinfunction "VCCINT_R10") (pintype "unspecified"))
      (node (ref "U25") (pin "R12") (pinfunction "VCCINT_R12") (pintype "unspecified"))
      (node (ref "U25") (pin "R8") (pinfunction "VCCINT_R8") (pintype "unspecified"))
      (node (ref "U25") (pin "U6") (pinfunction "VCCD_PLL1_U6") (pintype "unspecified"))
      (node (ref "U25") (pin "V17") (pinfunction "VCCD_PLL4_V17") (pintype "unspecified"))
    )
    (net (code "2") (name "2V5") (class "Default")
      (node (ref "C27") (pin "1") (pinfunction "1_1") (pintype "unspecified"))
      (node (ref "C29") (pin "1") (pinfunction "1_1") (pintype "unspecified"))
      (node (ref "C31") (pin "1") (pinfunction "1_1") (pintype "unspecified"))
      (node (ref "C33") (pin "1") (pinfunction "1_1") (pintype "unspecified"))
      (node (ref "C35") (pin "1") (pinfunction "1_1") (pintype "unspecified"))
      (node (ref "C54") (pin "2") (pinfunction "2_2") (pintype "unspecified"))
      (node (ref "C55") (pin "2") (pinfunction "2_2") (pintype "unspecified"))
      (node (ref "P1") (pin "4") (pinfunction "4_4") (pintype "input"))
      (node (ref "R141") (pin "1") (pinfunction "1_1") (pintype "unspecified"))
      (node (ref "R142") (pin "1") (pinfunction "1_1") (pintype "unspecified"))
      (node (ref "R35") (pin "2") (pinfunction "2_2") (pintype "input"))
      (node (ref "U25") (pin "F18") (pinfunction "VCCA2_F18") (pintype "unspecified"))
      (node (ref "U25") (pin "G6") (pinfunction "VCCA3_G6") (pintype "unspecified"))
      (node (ref "U25") (pin "L18") (pinfunction "MSEL1_L18") (pintype "input"))
      (node (ref "U25") (pin "T6") (pinfunction "VCCA1_T6") (pintype "unspecified"))
      (node (ref "U25") (pin "U18") (pinfunction "VCCA4_U18") (pintype "unspecified"))
      (node (ref "U6") (pin "1") (pinfunction "1_1") (pintype "input"))
    )
    (net (code "3") (name "3V3") (class "Default")
      (node (ref "C11") (pin "1") (pinfunction "1_1") (pintype "unspecified"))
      (node (ref "C118") (pin "1") (pinfunction "1_1") (pintype "input"))
      (node (ref "C119") (pin "2") (pinfunction "2_2") (pintype "input"))
      (node (ref "C121") (pin "1") (pinfunction "1_1") (pintype "input"))
      (node (ref "C122") (pin "1") (pinfunction "1_1") (pintype "input"))
      (node (ref "C123") (pin "1") (pinfunction "1_1") (pintype "input"))
      (node (ref "C124") (pin "1") (pinfunction "1_1") (pintype "input"))
      (node (ref "C125") (pin "1") (pinfunction "1_1") (pintype "input"))
      (node (ref "C126") (pin "1") (pinfunction "1_1") (pintype "input"))
      (node (ref "C127") (pin "1") (pinfunction "1_1") (pintype "input"))
      (node (ref "C128") (pin "1") (pinfunction "1_1") (pintype "input"))
      (node (ref "C129") (pin "1") (pinfunction "1_1") (pintype "input"))
      (node (ref "C13") (pin "1") (pinfunction "1_1") (pintype "unspecified"))
      (node (ref "C130") (pin "1") (pinfunction "1_1") (pintype "input"))
      (node (ref "C131") (pin "1") (pinfunction "1_1") (pintype "input"))
      (node (ref "C132") (pin "1") (pinfunction "1_1") (pintype "input"))
      (node (ref "C133") (pin "1") (pinfunction "1_1") (pintype "input"))
      (node (ref "C134") (pin "1") (pinfunction "1_1") (pintype "input"))
      (node (ref "C148") (pin "1") (pinfunction "1_1") (pintype "input"))
      (node (ref "C149") (pin "1") (pinfunction "1_1") (pintype "input"))
      (node (ref "C15") (pin "1") (pinfunction "1_1") (pintype "unspecified"))
      (node (ref "C150") (pin "1") (pinfunction "1_1") (pintype "input"))
      (node (ref "C151") (pin "2") (pinfunction "2_2") (pintype "input"))
      (node (ref "C152") (pin "1") (pinfunction "1_1") (pintype "input"))
      (node (ref "C153") (pin "1") (pinfunction "1_1") (pintype "input"))
      (node (ref "C16") (pin "1") (pinfunction "1_1") (pintype "unspecified"))
      (node (ref "C174") (pin "1") (pinfunction "1_1") (pintype "input"))
      (node (ref "C175") (pin "2") (pinfunction "2_2") (pintype "input"))
      (node (ref "C176") (pin "1") (pinfunction "1_1") (pintype "input"))
      (node (ref "C177") (pin "1") (pinfunction "1_1") (pintype "input"))
      (node (ref "C178") (pin "1") (pinfunction "1_1") (pintype "input"))
      (node (ref "C18") (pin "1") (pinfunction "1_1") (pintype "unspecified"))
      (node (ref "C20") (pin "1") (pinfunction "1_1") (pintype "unspecified"))
      (node (ref "C22") (pin "1") (pinfunction "1_1") (pintype "unspecified"))
      (node (ref "C24") (pin "1") (pinfunction "1_1") (pintype "unspecified"))
      (node (ref "C25") (pin "1") (pinfunction "1_1") (pintype "unspecified"))
      (node (ref "C26") (pin "1") (pinfunction "1_1") (pintype "unspecified"))
      (node (ref "C28") (pin "1") (pinfunction "1_1") (pintype "unspecified"))
      (node (ref "C30") (pin "1") (pinfunction "1_1") (pintype "unspecified"))
      (node (ref "C32") (pin "1") (pinfunction "1_1") (pintype "unspecified"))
      (node (ref "C34") (pin "1") (pinfunction "1_1") (pintype "unspecified"))
      (node (ref "C37") (pin "2") (pinfunction "2_2") (pintype "unspecified"))
      (node (ref "C38") (pin "2") (pinfunction "2_2") (pintype "unspecified"))
      (node (ref "C6") (pin "1") (pinfunction "1_1") (pintype "unspecified"))
      (node (ref "C9") (pin "1") (pinfunction "1_1") (pintype "unspecified"))
      (node (ref "CARD1") (pin "6") (pinfunction "VSS_6") (pintype "unspecified"))
      (node (ref "CN1") (pin "2") (pinfunction "2_2") (pintype "unspecified"))
      (node (ref "D2") (pin "2") (pinfunction "2_2") (pintype "unspecified"))
      (node (ref "D3") (pin "2") (pinfunction "2_2") (pintype "unspecified"))
      (node (ref "H1") (pin "3") (pinfunction "3_3") (pintype "unspecified"))
      (node (ref "H1") (pin "4") (pinfunction "4_4") (pintype "unspecified"))
      (node (ref "H2") (pin "1") (pinfunction "1_1") (pintype "unspecified"))
      (node (ref "H3") (pin "1") (pinfunction "1_1") (pintype "unspecified"))
      (node (ref "L2") (pin "2") (pinfunction "2_2") (pintype "unspecified"))
      (node (ref "LED10") (pin "2") (pinfunction "A_2") (pintype "unspecified"))
      (node (ref "R102") (pin "1") (pinfunction "1_1") (pintype "unspecified"))
      (node (ref "R119") (pin "2") (pinfunction "2_2") (pintype "input"))
      (node (ref "R120") (pin "2") (pinfunction "2_2") (pintype "unspecified"))
      (node (ref "R121") (pin "2") (pinfunction "2_2") (pintype "unspecified"))
      (node (ref "R122") (pin "2") (pinfunction "2_2") (pintype "unspecified"))
      (node (ref "R123") (pin "2") (pinfunction "2_2") (pintype "unspecified"))
      (node (ref "R124") (pin "2") (pinfunction "2_2") (pintype "unspecified"))
      (node (ref "R134") (pin "2") (pinfunction "2_2") (pintype "unspecified"))
      (node (ref "R135") (pin "1") (pinfunction "1_1") (pintype "unspecified"))
      (node (ref "R136") (pin "1") (pinfunction "1_1") (pintype "unspecified"))
      (node (ref "R137") (pin "1") (pinfunction "1_1") (pintype "unspecified"))
      (node (ref "R138") (pin "1") (pinfunction "1_1") (pintype "unspecified"))
      (node (ref "R139") (pin "1") (pinfunction "1_1") (pintype "unspecified"))
      (node (ref "R143") (pin "2") (pinfunction "2_2") (pintype "unspecified"))
      (node (ref "R144") (pin "2") (pinfunction "2_2") (pintype "unspecified"))
      (node (ref "R145") (pin "2") (pinfunction "2_2") (pintype "unspecified"))
      (node (ref "R149") (pin "1") (pinfunction "1_1") (pintype "unspecified"))
      (node (ref "R150") (pin "2") (pinfunction "2_2") (pintype "unspecified"))
      (node (ref "R31") (pin "2") (pinfunction "2_2") (pintype "input"))
      (node (ref "R93") (pin "1") (pinfunction "1_1") (pintype "input"))
      (node (ref "R94") (pin "1") (pinfunction "1_1") (pintype "input"))
      (node (ref "R95") (pin "1") (pinfunction "1_1") (pintype "input"))
      (node (ref "R96") (pin "1") (pinfunction "1_1") (pintype "input"))
      (node (ref "R97") (pin "1") (pinfunction "1_1") (pintype "input"))
      (node (ref "U14") (pin "1") (pinfunction "VDD_1") (pintype "unspecified"))
      (node (ref "U14") (pin "14") (pinfunction "VDD_14") (pintype "unspecified"))
      (node (ref "U14") (pin "27") (pinfunction "VDD_27") (pintype "unspecified"))
      (node (ref "U14") (pin "3") (pinfunction "VDDQ_3") (pintype "unspecified"))
      (node (ref "U14") (pin "43") (pinfunction "VDDQ_43") (pintype "unspecified"))
      (node (ref "U14") (pin "49") (pinfunction "VDDQ_49") (pintype "unspecified"))
      (node (ref "U14") (pin "9") (pinfunction "VDDQ_9") (pintype "unspecified"))
      (node (ref "U15") (pin "1") (pinfunction "VDD_1") (pintype "unspecified"))
      (node (ref "U15") (pin "14") (pinfunction "VDD_14") (pintype "unspecified"))
      (node (ref "U15") (pin "27") (pinfunction "VDD_27") (pintype "unspecified"))
      (node (ref "U15") (pin "3") (pinfunction "VDDQ_3") (pintype "unspecified"))
      (node (ref "U15") (pin "43") (pinfunction "VDDQ_43") (pintype "unspecified"))
      (node (ref "U15") (pin "49") (pinfunction "VDDQ_49") (pintype "unspecified"))
      (node (ref "U15") (pin "9") (pinfunction "VDDQ_9") (pintype "unspecified"))
      (node (ref "U16") (pin "24") (pinfunction "VDD_24") (pintype "input"))
      (node (ref "U16") (pin "8") (pinfunction "VDD_8") (pintype "input"))
      (node (ref "U18") (pin "20") (pinfunction "VCC_20") (pintype "unspecified"))
      (node (ref "U18") (pin "7") (pinfunction "V3_7") (pintype "unspecified"))
      (node (ref "U19") (pin "20") (pinfunction "VCC_20") (pintype "unspecified"))
      (node (ref "U19") (pin "7") (pinfunction "V3_7") (pintype "unspecified"))
      (node (ref "U2") (pin "8") (pinfunction "VCC_8") (pintype "unspecified"))
      (node (ref "U22") (pin "8") (pinfunction "VCC_8") (pintype "unspecified"))
      (node (ref "U23") (pin "16") (pinfunction "VCC_16") (pintype "unspecified"))
      (node (ref "U23") (pin "4") (pinfunction "V3_4") (pintype "unspecified"))
      (node (ref "U24") (pin "8") (pinfunction "VCC_8") (pintype "unspecified"))
      (node (ref "U25") (pin "A2") (pinfunction "VCCIO8_A2") (pintype "unspecified"))
      (node (ref "U25") (pin "A21") (pinfunction "VCCIO7_A21") (pintype "unspecified"))
      (node (ref "U25") (pin "AA6") (pinfunction "VCCIO3_AA6") (pintype "unspecified"))
      (node (ref "U25") (pin "AB2") (pinfunction "VCCIO3_AB2") (pintype "unspecified"))
      (node (ref "U25") (pin "AB21") (pinfunction "VCCIO4_AB21") (pintype "unspecified"))
      (node (ref "U25") (pin "D11") (pinfunction "VCCIO8_D11") (pintype "unspecified"))
      (node (ref "U25") (pin "D12") (pinfunction "VCCIO7_D12") (pintype "unspecified"))
      (node (ref "U25") (pin "D14") (pinfunction "VCCIO7_D14") (pintype "unspecified"))
      (node (ref "U25") (pin "D16") (pinfunction "VCCIO7_D16") (pintype "unspecified"))
      (node (ref "U25") (pin "D18") (pinfunction "VCCIO7_D18") (pintype "unspecified"))
      (node (ref "U25") (pin "D4") (pinfunction "VCCIO1_D4") (pintype "unspecified"))
      (node (ref "U25") (pin "D5") (pinfunction "VCCIO8_D5") (pintype "unspecified"))
      (node (ref "U25") (pin "D9") (pinfunction "VCCIO8_D9") (pintype "unspecified"))
      (node (ref "U25") (pin "E19") (pinfunction "VCCIO6_E19") (pintype "unspecified"))
      (node (ref "U25") (pin "E8") (pinfunction "VCCIO8_E8") (pintype "unspecified"))
      (node (ref "U25") (pin "F4") (pinfunction "VCCIO1_F4") (pintype "unspecified"))
      (node (ref "U25") (pin "G19") (pinfunction "VCCIO6_G19") (pintype "unspecified"))
      (node (ref "U25") (pin "H4") (pinfunction "VCCIO1_H4") (pintype "unspecified"))
      (node (ref "U25") (pin "J20") (pinfunction "VCCIO6_J20") (pintype "unspecified"))
      (node (ref "U25") (pin "K4") (pinfunction "VCCIO1_K4") (pintype "unspecified"))
      (node (ref "U25") (pin "L19") (pinfunction "VCCIO6_L19") (pintype "unspecified"))
      (node (ref "U25") (pin "N4") (pinfunction "VCCIO2_N4") (pintype "unspecified"))
      (node (ref "U25") (pin "P18") (pinfunction "VCCIO5_P18") (pintype "unspecified"))
      (node (ref "U25") (pin "R4") (pinfunction "VCCIO2_R4") (pintype "unspecified"))
      (node (ref "U25") (pin "T19") (pinfunction "VCCIO5_T19") (pintype "unspecified"))
      (node (ref "U25") (pin "U4") (pinfunction "VCCIO2_U4") (pintype "unspecified"))
      (node (ref "U25") (pin "V19") (pinfunction "VCCIO5_V19") (pintype "unspecified"))
      (node (ref "U25") (pin "W11") (pinfunction "VCCIO3_W11") (pintype "unspecified"))
      (node (ref "U25") (pin "W12") (pinfunction "VCCIO4_W12") (pintype "unspecified"))
      (node (ref "U25") (pin "W16") (pinfunction "VCCIO4_W16") (pintype "unspecified"))
      (node (ref "U25") (pin "W18") (pinfunction "VCCIO4_W18") (pintype "unspecified"))
      (node (ref "U25") (pin "W4") (pinfunction "VCCIO2_W4") (pintype "unspecified"))
      (node (ref "U25") (pin "W5") (pinfunction "VCCIO3_W5") (pintype "unspecified"))
      (node (ref "U25") (pin "W9") (pinfunction "VCCIO3_W9") (pintype "unspecified"))
      (node (ref "U25") (pin "Y14") (pinfunction "VCCIO4_Y14") (pintype "unspecified"))
      (node (ref "U25") (pin "Y19") (pinfunction "VCCIO5_Y19") (pintype "unspecified"))
      (node (ref "U26") (pin "15") (pinfunction "VDDTX_15") (pintype "unspecified"))
      (node (ref "U26") (pin "19") (pinfunction "VDDRX_19") (pintype "unspecified"))
      (node (ref "U26") (pin "20") (pinfunction "VDDPLL_20") (pintype "unspecified"))
      (node (ref "U26") (pin "25") (pinfunction "VDDOSC_25") (pintype "unspecified"))
      (node (ref "U26") (pin "28") (pinfunction "VDD_28") (pintype "unspecified"))
      (node (ref "U3") (pin "1") (pinfunction "1_1") (pintype "input"))
      (node (ref "X1") (pin "4") (pinfunction "VDD_4") (pintype "unspecified"))
    )
    (net (code "4") (name "5V") (class "Default")
      (node (ref "C165") (pin "2") (pinfunction "2_2") (pintype "input"))
      (node (ref "C166") (pin "2") (pinfunction "2_2") (pintype "input"))
      (node (ref "C167") (pin "2") (pinfunction "2_2") (pintype "input"))
      (node (ref "C173") (pin "2") (pinfunction "2_2") (pintype "input"))
      (node (ref "C43") (pin "2") (pinfunction "2_2") (pintype "unspecified"))
      (node (ref "C44") (pin "2") (pinfunction "2_2") (pintype "unspecified"))
      (node (ref "C51") (pin "2") (pinfunction "2_2") (pintype "unspecified"))
      (node (ref "C52") (pin "2") (pinfunction "2_2") (pintype "unspecified"))
      (node (ref "C60") (pin "2") (pinfunction "2_2") (pintype "unspecified"))
      (node (ref "C61") (pin "2") (pinfunction "2_2") (pintype "unspecified"))
      (node (ref "C95") (pin "1") (pinfunction "1_1") (pintype "unspecified"))
      (node (ref "D1") (pin "2") (pinfunction "2_2") (pintype "unspecified"))
      (node (ref "D4") (pin "2") (pinfunction "A_2") (pintype "unspecified"))
      (node (ref "H1") (pin "21") (pinfunction "21_21") (pintype "unspecified"))
      (node (ref "H1") (pin "22") (pinfunction "22_22") (pintype "unspecified"))
      (node (ref "R125") (pin "1") (pinfunction "1_1") (pintype "unspecified"))
      (node (ref "R126") (pin "1") (pinfunction "1_1") (pintype "unspecified"))
      (node (ref "R127") (pin "1") (pinfunction "1_1") (pintype "unspecified"))
      (node (ref "U10") (pin "2") (pinfunction "2_2") (pintype "unspecified"))
      (node (ref "U13") (pin "3") (pinfunction "VIN_3") (pintype "unspecified"))
      (node (ref "U4") (pin "3") (pinfunction "VIN_3") (pintype "unspecified"))
      (node (ref "U8") (pin "3") (pinfunction "VIN_3") (pintype "unspecified"))
      (node (ref "USB1") (pin "1") (pinfunction "VCC_1") (pintype "unspecified"))
      (node (ref "USB1") (pin "5") (pinfunction "VCC_5") (pintype "unspecified"))
    )
    (net (code "5") (name "5VIN") (class "Default")
      (node (ref "C171") (pin "1") (pinfunction "1_1") (pintype "input"))
      (node (ref "C47") (pin "2") (pinfunction "2_2") (pintype "unspecified"))
      (node (ref "R27") (pin "2") (pinfunction "2_2") (pintype "input"))
      (node (ref "U5") (pin "1") (pinfunction "VIN_1") (pintype "unspecified"))
      (node (ref "U9") (pin "2") (pinfunction "2_2") (pintype "unspecified"))
    )
    (net (code "6") (name "5VOUT") (class "Default")
      (node (ref "C40") (pin "2") (pinfunction "2_2") (pintype "unspecified"))
      (node (ref "C41") (pin "2") (pinfunction "2_2") (pintype "unspecified"))
      (node (ref "C42") (pin "2") (pinfunction "2_2") (pintype "unspecified"))
      (node (ref "U11") (pin "1") (pinfunction "1_1") (pintype "unspecified"))
      (node (ref "U5") (pin "8") (pinfunction "VOUT_8") (pintype "unspecified"))
    )
    (net (code "7") (name "5VSEL") (class "Default")
      (node (ref "F1") (pin "1") (pinfunction "1_1") (pintype "unspecified"))
      (node (ref "U10") (pin "3") (pinfunction "3_3") (pintype "unspecified"))
    )
    (net (code "8") (name "B+") (class "Default")
      (node (ref "BAT1") (pin "2") (pinfunction "+_2") (pintype "unspecified"))
      (node (ref "C48") (pin "2") (pinfunction "2_2") (pintype "unspecified"))
      (node (ref "L1") (pin "2") (pinfunction "2_2") (pintype "input"))
      (node (ref "R28") (pin "2") (pinfunction "2_2") (pintype "input"))
      (node (ref "R32") (pin "1") (pinfunction "1_1") (pintype "input"))
      (node (ref "U5") (pin "6") (pinfunction "BAT_6") (pintype "unspecified"))
    )
    (net (code "9") (name "B-") (class "Default")
      (node (ref "BAT1") (pin "1") (pinfunction "-_1") (pintype "unspecified"))
      (node (ref "C172") (pin "1") (pinfunction "1_1") (pintype "input"))
      (node (ref "U7") (pin "2") (pinfunction "GND_2") (pintype "unspecified"))
      (node (ref "U7") (pin "3") (pinfunction "GND_3") (pintype "unspecified"))
    )
    (net (code "10") (name "BTN_RESET") (class "Default")
      (node (ref "R135") (pin "2") (pinfunction "2_2") (pintype "unspecified"))
      (node (ref "SW4") (pin "1") (pinfunction "1_1") (pintype "input"))
      (node (ref "U25") (pin "R1") (pinfunction "IO,_DIFFIO_L33n,_(DQ1L)/(DQ3L)/(DQ1L)_R1") (pintype "bidirectional"))
    )
    (net (code "11") (name "CH376_1_CLK") (class "Default")
      (node (ref "U19") (pin "14") (pinfunction "SCK_14") (pintype "unspecified"))
      (node (ref "U25") (pin "N5") (pinfunction "IO,_(DQ1L)/(DQ3L)/(DQ1L)_N5") (pintype "bidirectional"))
    )
    (net (code "12") (name "CH376_1_CS") (class "Default")
      (node (ref "U19") (pin "13") (pinfunction "SCS_13") (pintype "unspecified"))
      (node (ref "U25") (pin "P4") (pinfunction "IO,_DIFFIO_L34p,_(DQS1L/CQ1L#,DPCLK1)/(DQS1L/CQ1L#,DPCLK1)/(DQS1L/CQ1L#,DPCLK1)_P4") (pintype "bidirectional"))
    )
    (net (code "13") (name "CH376_1_INT") (class "Default")
      (node (ref "U19") (pin "1") (pinfunction "INT#_1") (pintype "unspecified"))
      (node (ref "U25") (pin "M3") (pinfunction "IO,_DIFFIO_L28n,_(DQ1L)/(DQ3L)/(DQ1L)_M3") (pintype "bidirectional"))
    )
    (net (code "14") (name "CH376_1_MISO") (class "Default")
      (node (ref "U19") (pin "16") (pinfunction "SDO_16") (pintype "unspecified"))
      (node (ref "U25") (pin "P1") (pinfunction "IO,_DIFFIO_L32n,_(DQ1L)/(DQ3L)/(DQ1L)_P1") (pintype "bidirectional"))
    )
    (net (code "15") (name "CH376_1_MOSI") (class "Default")
      (node (ref "U19") (pin "15") (pinfunction "SDI_15") (pintype "unspecified"))
      (node (ref "U25") (pin "P2") (pinfunction "IO,_DIFFIO_L32p,_(DQ1L)/(DQ3L)/(DQ1L)_P2") (pintype "bidirectional"))
    )
    (net (code "16") (name "CH376_2_CLK") (class "Default")
      (node (ref "U18") (pin "14") (pinfunction "SCK_14") (pintype "unspecified"))
      (node (ref "U25") (pin "N1") (pinfunction "IO,_DIFFIO_L29n,_(DQ1L)/(DQ3L)/(DQ1L)_N1") (pintype "bidirectional"))
    )
    (net (code "17") (name "CH376_2_CS") (class "Default")
      (node (ref "U18") (pin "13") (pinfunction "SCS_13") (pintype "unspecified"))
      (node (ref "U25") (pin "N2") (pinfunction "IO,_DIFFIO_L29p,_(DQ1L)/(DQ3L)/(DQ1L)_N2") (pintype "bidirectional"))
    )
    (net (code "18") (name "CH376_2_INT") (class "Default")
      (node (ref "U18") (pin "1") (pinfunction "INT#_1") (pintype "unspecified"))
      (node (ref "U25") (pin "M4") (pinfunction "IO,_DIFFIO_L28p,_(DM0L)/(DM1L/BWS#1L)/(DM1L/BWS#1L)_M4") (pintype "bidirectional"))
    )
    (net (code "19") (name "CH376_2_MISO") (class "Default")
      (node (ref "U18") (pin "16") (pinfunction "SDO_16") (pintype "unspecified"))
      (node (ref "U25") (pin "M1") (pinfunction "IO,_DIFFIO_L27n,_(_)/(DQ1L)/(DQ1L)_M1") (pintype "bidirectional"))
    )
    (net (code "20") (name "CH376_2_MOSI") (class "Default")
      (node (ref "U18") (pin "15") (pinfunction "SDI_15") (pintype "unspecified"))
      (node (ref "U25") (pin "M2") (pinfunction "IO,_DIFFIO_L27p,_(DQ0L)/(DQ1L)/(DQ1L)_M2") (pintype "bidirectional"))
    )
    (net (code "21") (name "CLK_50M") (class "Default")
      (node (ref "U25") (pin "T2") (pinfunction "CLK2,_DIFFCLK_1p_T2") (pintype "input"))
      (node (ref "X1") (pin "3") (pinfunction "OUTPUT_3") (pintype "unspecified"))
    )
    (net (code "22") (name "DAC_D0") (class "Default")
      (node (ref "R110") (pin "2") (pinfunction "2_2") (pintype "unspecified"))
      (node (ref "U25") (pin "AA7") (pinfunction "IO,_DIFFIO_B14p,_(DM5B/BWS#5B)/(DM3B/BWS#3B)/(DM5B/BWS#5B)_AA7") (pintype "bidirectional"))
    )
    (net (code "23") (name "DAC_D1") (class "Default")
      (node (ref "R112") (pin "2") (pinfunction "2_2") (pintype "unspecified"))
      (node (ref "U25") (pin "Y7") (pinfunction "IO,_DIFFIO_B12n,_(DQ3B)/(DQ3B)/(DQ5B)_Y7") (pintype "bidirectional"))
    )
    (net (code "24") (name "DAC_D2") (class "Default")
      (node (ref "R113") (pin "2") (pinfunction "2_2") (pintype "unspecified"))
      (node (ref "U25") (pin "W7") (pinfunction "IO,_DIFFIO_B12p,_(DQ3B)/(DQ3B)/(DQ5B)_W7") (pintype "bidirectional"))
    )
    (net (code "25") (name "DAC_D3") (class "Default")
      (node (ref "R114") (pin "2") (pinfunction "2_2") (pintype "unspecified"))
      (node (ref "U25") (pin "Y6") (pinfunction "IO,_DIFFIO_B6p,_(DQS1B/CQ1B#,CDPCLK2)/(DQS1B/CQ1B#,CDPCLK2)/(DQS1B/CQ1B#,CDPCLK2)_Y6") (pintype "bidirectional"))
    )
    (net (code "26") (name "DAC_D4") (class "Default")
      (node (ref "R115") (pin "2") (pinfunction "2_2") (pintype "unspecified"))
      (node (ref "U25") (pin "W6") (pinfunction "IO,_DIFFIO_B7p,_(DQ3B)/(DQ3B)/(DQ5B)_W6") (pintype "bidirectional"))
    )
    (net (code "27") (name "DAC_D5") (class "Default")
      (node (ref "R116") (pin "2") (pinfunction "2_2") (pintype "unspecified"))
      (node (ref "U25") (pin "AB5") (pinfunction "IO,_DIFFIO_B8n_AB5") (pintype "bidirectional"))
    )
    (net (code "28") (name "DAC_D6") (class "Default")
      (node (ref "R117") (pin "2") (pinfunction "2_2") (pintype "unspecified"))
      (node (ref "U25") (pin "AA5") (pinfunction "IO,_DIFFIO_B8p,_(DQ3B)/(DQ3B)/(DQ5B)_AA5") (pintype "bidirectional"))
    )
    (net (code "29") (name "DAC_D7") (class "Default")
      (node (ref "R118") (pin "2") (pinfunction "2_2") (pintype "unspecified"))
      (node (ref "U25") (pin "AA4") (pinfunction "IO,_(DQ3B)/(DQ3B)/(DQ5B)_AA4") (pintype "bidirectional"))
    )
    (net (code "30") (name "DISPL_1") (class "Default")
      (node (ref "H3") (pin "3") (pinfunction "3_3") (pintype "unspecified"))
    )
    (net (code "31") (name "DISPL_2") (class "Default")
      (node (ref "H3") (pin "5") (pinfunction "5_5") (pintype "unspecified"))
    )
    (net (code "32") (name "DISPL_3") (class "Default")
      (node (ref "H3") (pin "7") (pinfunction "7_7") (pintype "unspecified"))
    )
    (net (code "33") (name "DISPL_4") (class "Default")
      (node (ref "H3") (pin "4") (pinfunction "4_4") (pintype "unspecified"))
    )
    (net (code "34") (name "DISPL_5") (class "Default")
      (node (ref "H3") (pin "6") (pinfunction "6_6") (pintype "unspecified"))
    )
    (net (code "35") (name "DISPL_6") (class "Default")
      (node (ref "H3") (pin "8") (pinfunction "8_8") (pintype "unspecified"))
    )
    (net (code "36") (name "ETH_CLK") (class "Default")
      (node (ref "U25") (pin "B3") (pinfunction "IO,_DIFFIO_T4p,_(DATA11),_(DQ3T)/(DQ3T)/(DQ5T)_B3") (pintype "bidirectional"))
      (node (ref "U26") (pin "8") (pinfunction "SCK_8") (pintype "unspecified"))
    )
    (net (code "37") (name "ETH_CS") (class "Default")
      (node (ref "U25") (pin "C3") (pinfunction "IO,_DIFFIO_T3n,_(DQ3T)/(DQ3T)/(DQ5T)_C3") (pintype "bidirectional"))
      (node (ref "U26") (pin "9") (pinfunction "CS#_9") (pintype "unspecified"))
    )
    (net (code "38") (name "ETH_INT") (class "Default")
      (node (ref "U25") (pin "A4") (pinfunction "IO,_DIFFIO_T6n,_(DQ3T)/(DQ3T)/(DQ5T)_A4") (pintype "bidirectional"))
      (node (ref "U26") (pin "4") (pinfunction "INT#_4") (pintype "unspecified"))
    )
    (net (code "39") (name "ETH_MISO") (class "Default")
      (node (ref "U25") (pin "B4") (pinfunction "IO,_DIFFIO_T6p,_(DATA8),_(DQ3T)/(DQ3T)/(DQ5T)_B4") (pintype "bidirectional"))
      (node (ref "U26") (pin "6") (pinfunction "SO_6") (pintype "unspecified"))
    )
    (net (code "40") (name "ETH_MOSI") (class "Default")
      (node (ref "U25") (pin "C4") (pinfunction "IO,_DIFFIO_T3p,_(DATA12),_(DQS1T/CQ1T#,CDPCLK7)/(DQS1T/CQ1T#,CDPCLK7)/(DQS1T/CQ1T#,CDPCLK7)_C4") (pintype "bidirectional"))
      (node (ref "U26") (pin "7") (pinfunction "SI_7") (pintype "unspecified"))
    )
    (net (code "41") (name "FPGA_ASDO") (class "Default")
      (node (ref "U2") (pin "5") (pinfunction "DI_5") (pintype "unspecified"))
      (node (ref "U25") (pin "D1") (pinfunction "IO,_DIFFIO_L8n,_(DATA1,ASDO)_D1") (pintype "bidirectional"))
    )
    (net (code "42") (name "FPGA_CONF_DONE") (class "Default")
      (node (ref "LED1") (pin "2") (pinfunction "A_2") (pintype "unspecified"))
      (node (ref "R145") (pin "1") (pinfunction "1_1") (pintype "unspecified"))
      (node (ref "U25") (pin "M18") (pinfunction "CONF_DONE_M18") (pintype "bidirectional"))
    )
    (net (code "43") (name "FPGA_DATA0") (class "Default")
      (node (ref "U2") (pin "2") (pinfunction "DO_2") (pintype "unspecified"))
      (node (ref "U25") (pin "K1") (pinfunction "IO,_(DATA0)_K1") (pintype "bidirectional"))
    )
    (net (code "44") (name "FPGA_DCLK") (class "Default")
      (node (ref "U2") (pin "6") (pinfunction "CLK_6") (pintype "unspecified"))
      (node (ref "U25") (pin "K2") (pinfunction "DCLK_K2") (pintype "bidirectional"))
    )
    (net (code "45") (name "FPGA_NCONFIG") (class "Default")
      (node (ref "R144") (pin "1") (pinfunction "1_1") (pintype "unspecified"))
      (node (ref "SW2") (pin "1") (pinfunction "1_1") (pintype "input"))
      (node (ref "U25") (pin "K5") (pinfunction "nCONFIG_K5") (pintype "input"))
    )
    (net (code "46") (name "FPGA_NCSO") (class "Default")
      (node (ref "U2") (pin "1") (pinfunction "CS#_1") (pintype "unspecified"))
      (node (ref "U25") (pin "E2") (pinfunction "IO,_DIFFIO_L10p,_(FLASH_nCE,nCSO)_E2") (pintype "bidirectional"))
    )
    (net (code "47") (name "GND") (class "Default")
      (node (ref "C10") (pin "2") (pinfunction "2_2") (pintype "unspecified"))
      (node (ref "C11") (pin "2") (pinfunction "2_2") (pintype "unspecified"))
      (node (ref "C118") (pin "2") (pinfunction "2_2") (pintype "input"))
      (node (ref "C119") (pin "1") (pinfunction "1_1") (pintype "input"))
      (node (ref "C12") (pin "2") (pinfunction "2_2") (pintype "unspecified"))
      (node (ref "C121") (pin "2") (pinfunction "2_2") (pintype "input"))
      (node (ref "C122") (pin "2") (pinfunction "2_2") (pintype "input"))
      (node (ref "C123") (pin "2") (pinfunction "2_2") (pintype "input"))
      (node (ref "C124") (pin "2") (pinfunction "2_2") (pintype "input"))
      (node (ref "C125") (pin "2") (pinfunction "2_2") (pintype "input"))
      (node (ref "C126") (pin "2") (pinfunction "2_2") (pintype "input"))
      (node (ref "C127") (pin "2") (pinfunction "2_2") (pintype "input"))
      (node (ref "C128") (pin "2") (pinfunction "2_2") (pintype "input"))
      (node (ref "C129") (pin "2") (pinfunction "2_2") (pintype "input"))
      (node (ref "C13") (pin "2") (pinfunction "2_2") (pintype "unspecified"))
      (node (ref "C130") (pin "2") (pinfunction "2_2") (pintype "input"))
      (node (ref "C131") (pin "2") (pinfunction "2_2") (pintype "input"))
      (node (ref "C132") (pin "2") (pinfunction "2_2") (pintype "input"))
      (node (ref "C133") (pin "2") (pinfunction "2_2") (pintype "input"))
      (node (ref "C134") (pin "2") (pinfunction "2_2") (pintype "input"))
      (node (ref "C14") (pin "2") (pinfunction "2_2") (pintype "unspecified"))
      (node (ref "C148") (pin "2") (pinfunction "2_2") (pintype "input"))
      (node (ref "C149") (pin "2") (pinfunction "2_2") (pintype "input"))
      (node (ref "C15") (pin "2") (pinfunction "2_2") (pintype "unspecified"))
      (node (ref "C150") (pin "2") (pinfunction "2_2") (pintype "input"))
      (node (ref "C151") (pin "1") (pinfunction "1_1") (pintype "input"))
      (node (ref "C152") (pin "2") (pinfunction "2_2") (pintype "input"))
      (node (ref "C153") (pin "2") (pinfunction "2_2") (pintype "input"))
      (node (ref "C154") (pin "1") (pinfunction "1_1") (pintype "input"))
      (node (ref "C155") (pin "1") (pinfunction "1_1") (pintype "input"))
      (node (ref "C156") (pin "1") (pinfunction "1_1") (pintype "input"))
      (node (ref "C157") (pin "1") (pinfunction "1_1") (pintype "input"))
      (node (ref "C158") (pin "1") (pinfunction "1_1") (pintype "input"))
      (node (ref "C159") (pin "1") (pinfunction "1_1") (pintype "input"))
      (node (ref "C16") (pin "2") (pinfunction "2_2") (pintype "unspecified"))
      (node (ref "C163") (pin "2") (pinfunction "2_2") (pintype "input"))
      (node (ref "C164") (pin "2") (pinfunction "2_2") (pintype "input"))
      (node (ref "C165") (pin "1") (pinfunction "1_1") (pintype "input"))
      (node (ref "C166") (pin "1") (pinfunction "1_1") (pintype "input"))
      (node (ref "C167") (pin "1") (pinfunction "1_1") (pintype "input"))
      (node (ref "C17") (pin "2") (pinfunction "2_2") (pintype "unspecified"))
      (node (ref "C171") (pin "2") (pinfunction "2_2") (pintype "input"))
      (node (ref "C173") (pin "1") (pinfunction "1_1") (pintype "input"))
      (node (ref "C176") (pin "2") (pinfunction "2_2") (pintype "input"))
      (node (ref "C177") (pin "2") (pinfunction "2_2") (pintype "input"))
      (node (ref "C178") (pin "2") (pinfunction "2_2") (pintype "input"))
      (node (ref "C18") (pin "2") (pinfunction "2_2") (pintype "unspecified"))
      (node (ref "C19") (pin "2") (pinfunction "2_2") (pintype "unspecified"))
      (node (ref "C20") (pin "2") (pinfunction "2_2") (pintype "unspecified"))
      (node (ref "C21") (pin "2") (pinfunction "2_2") (pintype "unspecified"))
      (node (ref "C22") (pin "2") (pinfunction "2_2") (pintype "unspecified"))
      (node (ref "C23") (pin "2") (pinfunction "2_2") (pintype "unspecified"))
      (node (ref "C24") (pin "2") (pinfunction "2_2") (pintype "unspecified"))
      (node (ref "C25") (pin "2") (pinfunction "2_2") (pintype "unspecified"))
      (node (ref "C26") (pin "2") (pinfunction "2_2") (pintype "unspecified"))
      (node (ref "C27") (pin "2") (pinfunction "2_2") (pintype "unspecified"))
      (node (ref "C28") (pin "2") (pinfunction "2_2") (pintype "unspecified"))
      (node (ref "C29") (pin "2") (pinfunction "2_2") (pintype "unspecified"))
      (node (ref "C30") (pin "2") (pinfunction "2_2") (pintype "unspecified"))
      (node (ref "C31") (pin "2") (pinfunction "2_2") (pintype "unspecified"))
      (node (ref "C32") (pin "2") (pinfunction "2_2") (pintype "unspecified"))
      (node (ref "C33") (pin "2") (pinfunction "2_2") (pintype "unspecified"))
      (node (ref "C34") (pin "2") (pinfunction "2_2") (pintype "unspecified"))
      (node (ref "C35") (pin "2") (pinfunction "2_2") (pintype "unspecified"))
      (node (ref "C37") (pin "1") (pinfunction "1_1") (pintype "unspecified"))
      (node (ref "C38") (pin "1") (pinfunction "1_1") (pintype "unspecified"))
      (node (ref "C40") (pin "1") (pinfunction "1_1") (pintype "unspecified"))
      (node (ref "C41") (pin "1") (pinfunction "1_1") (pintype "unspecified"))
      (node (ref "C42") (pin "1") (pinfunction "1_1") (pintype "unspecified"))
      (node (ref "C43") (pin "1") (pinfunction "1_1") (pintype "unspecified"))
      (node (ref "C44") (pin "1") (pinfunction "1_1") (pintype "unspecified"))
      (node (ref "C47") (pin "1") (pinfunction "1_1") (pintype "unspecified"))
      (node (ref "C48") (pin "1") (pinfunction "1_1") (pintype "unspecified"))
      (node (ref "C49") (pin "1") (pinfunction "1_1") (pintype "unspecified"))
      (node (ref "C50") (pin "1") (pinfunction "1_1") (pintype "unspecified"))
      (node (ref "C51") (pin "1") (pinfunction "1_1") (pintype "unspecified"))
      (node (ref "C52") (pin "1") (pinfunction "1_1") (pintype "unspecified"))
      (node (ref "C54") (pin "1") (pinfunction "1_1") (pintype "unspecified"))
      (node (ref "C55") (pin "1") (pinfunction "1_1") (pintype "unspecified"))
      (node (ref "C58") (pin "1") (pinfunction "1_1") (pintype "unspecified"))
      (node (ref "C59") (pin "1") (pinfunction "1_1") (pintype "unspecified"))
      (node (ref "C6") (pin "2") (pinfunction "2_2") (pintype "unspecified"))
      (node (ref "C60") (pin "1") (pinfunction "1_1") (pintype "unspecified"))
      (node (ref "C61") (pin "1") (pinfunction "1_1") (pintype "unspecified"))
      (node (ref "C7") (pin "2") (pinfunction "2_2") (pintype "unspecified"))
      (node (ref "C9") (pin "2") (pinfunction "2_2") (pintype "unspecified"))
      (node (ref "C95") (pin "2") (pinfunction "2_2") (pintype "unspecified"))
      (node (ref "C98") (pin "1") (pinfunction "1_1") (pintype "unspecified"))
      (node (ref "CARD1") (pin "10") (pinfunction "10_10") (pintype "unspecified"))
      (node (ref "CARD1") (pin "11") (pinfunction "11_11") (pintype "unspecified"))
      (node (ref "CARD1") (pin "12") (pinfunction "12_12") (pintype "unspecified"))
      (node (ref "CARD1") (pin "13") (pinfunction "13_13") (pintype "unspecified"))
      (node (ref "CARD1") (pin "4") (pinfunction "VDD_4") (pintype "unspecified"))
      (node (ref "CN1") (pin "1") (pinfunction "1_1") (pintype "unspecified"))
      (node (ref "D1") (pin "5") (pinfunction "5_5") (pintype "unspecified"))
      (node (ref "D2") (pin "5") (pinfunction "5_5") (pintype "unspecified"))
      (node (ref "D3") (pin "5") (pinfunction "5_5") (pintype "unspecified"))
      (node (ref "H1") (pin "1") (pinfunction "1_1") (pintype "unspecified"))
      (node (ref "H1") (pin "2") (pinfunction "2_2") (pintype "unspecified"))
      (node (ref "H1") (pin "23") (pinfunction "23_23") (pintype "unspecified"))
      (node (ref "H1") (pin "24") (pinfunction "24_24") (pintype "unspecified"))
      (node (ref "H2") (pin "3") (pinfunction "3_3") (pintype "unspecified"))
      (node (ref "H3") (pin "2") (pinfunction "2_2") (pintype "unspecified"))
      (node (ref "HDMI1") (pin "11") (pinfunction "TMDSClockShield_11") (pintype "unspecified"))
      (node (ref "HDMI1") (pin "17") (pinfunction "DDC/CECGround_17") (pintype "unspecified"))
      (node (ref "HDMI1") (pin "2") (pinfunction "TMDSData2Shield_2") (pintype "unspecified"))
      (node (ref "HDMI1") (pin "20") (pinfunction "EH_20") (pintype "unspecified"))
      (node (ref "HDMI1") (pin "5") (pinfunction "TMDSData1Shield_5") (pintype "unspecified"))
      (node (ref "HDMI1") (pin "8") (pinfunction "TMDSData0Shield_8") (pintype "unspecified"))
      (node (ref "J1") (pin "10") (pinfunction "10_10") (pintype "unspecified"))
      (node (ref "J1") (pin "11") (pinfunction "11_11") (pintype "unspecified"))
      (node (ref "J1") (pin "8") (pinfunction "CHS_GND_8") (pintype "unspecified"))
      (node (ref "J1") (pin "SH1") (pinfunction "SH1_SH1") (pintype "unspecified"))
      (node (ref "J1") (pin "SH2") (pinfunction "SH2_SH2") (pintype "unspecified"))
      (node (ref "P1") (pin "10") (pinfunction "10_10") (pintype "input"))
      (node (ref "P1") (pin "2") (pinfunction "2_2") (pintype "input"))
      (node (ref "R100") (pin "1") (pinfunction "1_1") (pintype "input"))
      (node (ref "R101") (pin "1") (pinfunction "1_1") (pintype "input"))
      (node (ref "R111") (pin "1") (pinfunction "1_1") (pintype "unspecified"))
      (node (ref "R128") (pin "1") (pinfunction "1_1") (pintype "input"))
      (node (ref "R129") (pin "1") (pinfunction "1_1") (pintype "input"))
      (node (ref "R130") (pin "1") (pinfunction "1_1") (pintype "input"))
      (node (ref "R131") (pin "1") (pinfunction "1_1") (pintype "input"))
      (node (ref "R132") (pin "1") (pinfunction "1_1") (pintype "input"))
      (node (ref "R133") (pin "1") (pinfunction "1_1") (pintype "input"))
      (node (ref "R140") (pin "1") (pinfunction "1_1") (pintype "input"))
      (node (ref "R148") (pin "2") (pinfunction "2_2") (pintype "unspecified"))
      (node (ref "R151") (pin "1") (pinfunction "1_1") (pintype "input"))
      (node (ref "R30") (pin "1") (pinfunction "1_1") (pintype "input"))
      (node (ref "R34") (pin "2") (pinfunction "2_2") (pintype "input"))
      (node (ref "R37") (pin "2") (pinfunction "2_2") (pintype "input"))
      (node (ref "R98") (pin "2") (pinfunction "2_2") (pintype "unspecified"))
      (node (ref "R99") (pin "2") (pinfunction "2_2") (pintype "unspecified"))
      (node (ref "SCREW1") (pin "1") (pinfunction "1_1") (pintype "input"))
      (node (ref "SCREW2") (pin "1") (pinfunction "1_1") (pintype "input"))
      (node (ref "SCREW3") (pin "1") (pinfunction "1_1") (pintype "input"))
      (node (ref "SCREW4") (pin "1") (pinfunction "1_1") (pintype "input"))
      (node (ref "SW2") (pin "2") (pinfunction "2_2") (pintype "input"))
      (node (ref "SW2") (pin "3") (pinfunction "3_3") (pintype "input"))
      (node (ref "SW3") (pin "2") (pinfunction "2_2") (pintype "input"))
      (node (ref "SW3") (pin "3") (pinfunction "3_3") (pintype "input"))
      (node (ref "SW4") (pin "2") (pinfunction "2_2") (pintype "input"))
      (node (ref "SW4") (pin "3") (pinfunction "3_3") (pintype "input"))
      (node (ref "SW5") (pin "1") (pinfunction "A1_1") (pintype "input"))
      (node (ref "SW5") (pin "2") (pinfunction "A2_2") (pintype "input"))
      (node (ref "SW5") (pin "3") (pinfunction "A3_3") (pintype "input"))
      (node (ref "SW5") (pin "4") (pinfunction "A4_4") (pintype "input"))
      (node (ref "U13") (pin "1") (pinfunction "GND_1") (pintype "unspecified"))
      (node (ref "U14") (pin "12") (pinfunction "VSSQ_12") (pintype "unspecified"))
      (node (ref "U14") (pin "28") (pinfunction "VSS_28") (pintype "unspecified"))
      (node (ref "U14") (pin "41") (pinfunction "VSS_41") (pintype "unspecified"))
      (node (ref "U14") (pin "46") (pinfunction "VSSQ_46") (pintype "unspecified"))
      (node (ref "U14") (pin "52") (pinfunction "VSSQ_52") (pintype "unspecified"))
      (node (ref "U14") (pin "54") (pinfunction "VSS_54") (pintype "unspecified"))
      (node (ref "U14") (pin "6") (pinfunction "VSSQ_6") (pintype "unspecified"))
      (node (ref "U15") (pin "12") (pinfunction "VSSQ_12") (pintype "unspecified"))
      (node (ref "U15") (pin "28") (pinfunction "VSS_28") (pintype "unspecified"))
      (node (ref "U15") (pin "41") (pinfunction "VSS_41") (pintype "unspecified"))
      (node (ref "U15") (pin "46") (pinfunction "VSSQ_46") (pintype "unspecified"))
      (node (ref "U15") (pin "52") (pinfunction "VSSQ_52") (pintype "unspecified"))
      (node (ref "U15") (pin "54") (pinfunction "VSS_54") (pintype "unspecified"))
      (node (ref "U15") (pin "6") (pinfunction "VSSQ_6") (pintype "unspecified"))
      (node (ref "U16") (pin "25") (pinfunction "GND_25") (pintype "input"))
      (node (ref "U16") (pin "9") (pinfunction "GND_9") (pintype "input"))
      (node (ref "U18") (pin "10") (pinfunction "GND_10") (pintype "unspecified"))
      (node (ref "U18") (pin "3") (pinfunction "SPI#_3") (pintype "unspecified"))
      (node (ref "U19") (pin "10") (pinfunction "GND_10") (pintype "unspecified"))
      (node (ref "U19") (pin "3") (pinfunction "SPI#_3") (pintype "unspecified"))
      (node (ref "U2") (pin "4") (pinfunction "GND_4") (pintype "unspecified"))
      (node (ref "U22") (pin "4") (pinfunction "GND_4") (pintype "unspecified"))
      (node (ref "U23") (pin "1") (pinfunction "GND_1") (pintype "unspecified"))
      (node (ref "U24") (pin "4") (pinfunction "GND_4") (pintype "unspecified"))
      (node (ref "U25") (pin "A1") (pinfunction "GND_A1") (pintype "unspecified"))
      (node (ref "U25") (pin "A22") (pinfunction "GND_A22") (pintype "unspecified"))
      (node (ref "U25") (pin "AA2") (pinfunction "GND_AA2") (pintype "unspecified"))
      (node (ref "U25") (pin "AA22") (pinfunction "GND_AA22") (pintype "unspecified"))
      (node (ref "U25") (pin "AB1") (pinfunction "GND_AB1") (pintype "unspecified"))
      (node (ref "U25") (pin "AB22") (pinfunction "GND_AB22") (pintype "unspecified"))
      (node (ref "U25") (pin "AB6") (pinfunction "GND_AB6") (pintype "unspecified"))
      (node (ref "U25") (pin "C11") (pinfunction "GND_C11") (pintype "unspecified"))
      (node (ref "U25") (pin "C12") (pinfunction "GND_C12") (pintype "unspecified"))
      (node (ref "U25") (pin "C14") (pinfunction "GND_C14") (pintype "unspecified"))
      (node (ref "U25") (pin "C16") (pinfunction "GND_C16") (pintype "unspecified"))
      (node (ref "U25") (pin "C18") (pinfunction "GND_C18") (pintype "unspecified"))
      (node (ref "U25") (pin "C5") (pinfunction "GND_C5") (pintype "unspecified"))
      (node (ref "U25") (pin "C9") (pinfunction "GND_C9") (pintype "unspecified"))
      (node (ref "U25") (pin "D3") (pinfunction "GND_D3") (pintype "unspecified"))
      (node (ref "U25") (pin "D8") (pinfunction "GND_D8") (pintype "unspecified"))
      (node (ref "U25") (pin "E18") (pinfunction "GNDA2_E18") (pintype "unspecified"))
      (node (ref "U25") (pin "E20") (pinfunction "GND_E20") (pintype "unspecified"))
      (node (ref "U25") (pin "F12") (pinfunction "GND_F12") (pintype "unspecified"))
      (node (ref "U25") (pin "F3") (pinfunction "GND_F3") (pintype "unspecified"))
      (node (ref "U25") (pin "F5") (pinfunction "GNDA3_F5") (pintype "unspecified"))
      (node (ref "U25") (pin "G2") (pinfunction "GND_G2") (pintype "unspecified"))
      (node (ref "U25") (pin "G20") (pinfunction "GND_G20") (pintype "unspecified"))
      (node (ref "U25") (pin "H12") (pinfunction "GND_H12") (pintype "unspecified"))
      (node (ref "U25") (pin "H13") (pinfunction "GND_H13") (pintype "unspecified"))
      (node (ref "U25") (pin "H3") (pinfunction "GND_H3") (pintype "unspecified"))
      (node (ref "U25") (pin "J15") (pinfunction "GND_J15") (pintype "unspecified"))
      (node (ref "U25") (pin "J19") (pinfunction "GND_J19") (pintype "unspecified"))
      (node (ref "U25") (pin "J9") (pinfunction "GND_J9") (pintype "unspecified"))
      (node (ref "U25") (pin "K10") (pinfunction "GND_K10") (pintype "unspecified"))
      (node (ref "U25") (pin "K11") (pinfunction "GND_K11") (pintype "unspecified"))
      (node (ref "U25") (pin "K12") (pinfunction "GND_K12") (pintype "unspecified"))
      (node (ref "U25") (pin "K13") (pinfunction "GND_K13") (pintype "unspecified"))
      (node (ref "U25") (pin "K16") (pinfunction "GND_K16") (pintype "unspecified"))
      (node (ref "U25") (pin "K20") (pinfunction "MSEL3_K20") (pintype "input"))
      (node (ref "U25") (pin "K3") (pinfunction "GND_K3") (pintype "unspecified"))
      (node (ref "U25") (pin "L10") (pinfunction "GND_L10") (pintype "unspecified"))
      (node (ref "U25") (pin "L11") (pinfunction "GND_L11") (pintype "unspecified"))
      (node (ref "U25") (pin "L12") (pinfunction "GND_L12") (pintype "unspecified"))
      (node (ref "U25") (pin "L13") (pinfunction "GND_L13") (pintype "unspecified"))
      (node (ref "U25") (pin "L15") (pinfunction "GND_L15") (pintype "unspecified"))
      (node (ref "U25") (pin "L17") (pinfunction "MSEL2_L17") (pintype "input"))
      (node (ref "U25") (pin "L20") (pinfunction "GND_L20") (pintype "unspecified"))
      (node (ref "U25") (pin "L3") (pinfunction "nCE_L3") (pintype "input"))
      (node (ref "U25") (pin "M10") (pinfunction "GND_M10") (pintype "unspecified"))
      (node (ref "U25") (pin "M11") (pinfunction "GND_M11") (pintype "unspecified"))
      (node (ref "U25") (pin "M12") (pinfunction "GND_M12") (pintype "unspecified"))
      (node (ref "U25") (pin "M13") (pinfunction "GND_M13") (pintype "unspecified"))
      (node (ref "U25") (pin "M17") (pinfunction "MSEL0_M17") (pintype "input"))
      (node (ref "U25") (pin "N10") (pinfunction "GND_N10") (pintype "unspecified"))
      (node (ref "U25") (pin "N11") (pinfunction "GND_N11") (pintype "unspecified"))
      (node (ref "U25") (pin "N12") (pinfunction "GND_N12") (pintype "unspecified"))
      (node (ref "U25") (pin "N13") (pinfunction "GND_N13") (pintype "unspecified"))
      (node (ref "U25") (pin "N15") (pinfunction "GND_N15") (pintype "unspecified"))
      (node (ref "U25") (pin "N3") (pinfunction "GND_N3") (pintype "unspecified"))
      (node (ref "U25") (pin "P19") (pinfunction "GND_P19") (pintype "unspecified"))
      (node (ref "U25") (pin "P8") (pinfunction "GND_P8") (pintype "unspecified"))
      (node (ref "U25") (pin "R11") (pinfunction "GND_R11") (pintype "unspecified"))
      (node (ref "U25") (pin "R13") (pinfunction "GND_R13") (pintype "unspecified"))
      (node (ref "U25") (pin "R3") (pinfunction "GND_R3") (pintype "unspecified"))
      (node (ref "U25") (pin "R9") (pinfunction "GND_R9") (pintype "unspecified"))
      (node (ref "U25") (pin "T20") (pinfunction "GND_T20") (pintype "unspecified"))
      (node (ref "U25") (pin "U3") (pinfunction "GND_U3") (pintype "unspecified"))
      (node (ref "U25") (pin "U5") (pinfunction "GNDA1_U5") (pintype "unspecified"))
      (node (ref "U25") (pin "V18") (pinfunction "GNDA4_V18") (pintype "unspecified"))
      (node (ref "U25") (pin "V20") (pinfunction "GND_V20") (pintype "unspecified"))
      (node (ref "U25") (pin "W3") (pinfunction "GND_W3") (pintype "unspecified"))
      (node (ref "U25") (pin "Y11") (pinfunction "GND_Y11") (pintype "unspecified"))
      (node (ref "U25") (pin "Y12") (pinfunction "GND_Y12") (pintype "unspecified"))
      (node (ref "U25") (pin "Y15") (pinfunction "GND_Y15") (pintype "unspecified"))
      (node (ref "U25") (pin "Y16") (pinfunction "GND_Y16") (pintype "unspecified"))
      (node (ref "U25") (pin "Y18") (pinfunction "GND_Y18") (pintype "unspecified"))
      (node (ref "U25") (pin "Y20") (pinfunction "GND_Y20") (pintype "unspecified"))
      (node (ref "U25") (pin "Y5") (pinfunction "GND_Y5") (pintype "unspecified"))
      (node (ref "U25") (pin "Y9") (pinfunction "GND_Y9") (pintype "unspecified"))
      (node (ref "U26") (pin "11") (pinfunction "VSSRX_11") (pintype "unspecified"))
      (node (ref "U26") (pin "18") (pinfunction "VSSTX_18") (pintype "unspecified"))
      (node (ref "U26") (pin "2") (pinfunction "VSS_2") (pintype "unspecified"))
      (node (ref "U26") (pin "21") (pinfunction "VSSPLL_21") (pintype "unspecified"))
      (node (ref "U26") (pin "22") (pinfunction "VSSOSC_22") (pintype "unspecified"))
      (node (ref "U4") (pin "1") (pinfunction "GND_1") (pintype "unspecified"))
      (node (ref "U5") (pin "9") (pinfunction "EP_9") (pintype "unspecified"))
      (node (ref "U7") (pin "4") (pinfunction "VM_4") (pintype "unspecified"))
      (node (ref "U7") (pin "5") (pinfunction "VM_5") (pintype "unspecified"))
      (node (ref "U8") (pin "1") (pinfunction "GND_1") (pintype "unspecified"))
      (node (ref "USB1") (pin "10") (pinfunction "SHELL_10") (pintype "unspecified"))
      (node (ref "USB1") (pin "11") (pinfunction "SHELL_11") (pintype "unspecified"))
      (node (ref "USB1") (pin "12") (pinfunction "SHELL_12") (pintype "unspecified"))
      (node (ref "USB1") (pin "4") (pinfunction "GND_4") (pintype "unspecified"))
      (node (ref "USB1") (pin "8") (pinfunction "GND_8") (pintype "unspecified"))
      (node (ref "USB1") (pin "9") (pinfunction "SHELL_9") (pintype "unspecified"))
      (node (ref "USB2") (pin "1") (pinfunction "GND_1") (pintype "unspecified"))
      (node (ref "USB2") (pin "12") (pinfunction "GND_12") (pintype "unspecified"))
      (node (ref "USB2") (pin "13") (pinfunction "SHELL_13") (pintype "unspecified"))
      (node (ref "USB2") (pin "14") (pinfunction "SHELL_14") (pintype "unspecified"))
      (node (ref "X1") (pin "2") (pinfunction "GND_2") (pintype "unspecified"))
      (node (ref "X5") (pin "2") (pinfunction "GND_2") (pintype "unspecified"))
      (node (ref "X5") (pin "4") (pinfunction "GND_4") (pintype "unspecified"))
      (node (ref "X6") (pin "2") (pinfunction "GND_2") (pintype "unspecified"))
      (node (ref "X6") (pin "4") (pinfunction "GND_4") (pintype "unspecified"))
      (node (ref "X8") (pin "2") (pinfunction "GND_2") (pintype "unspecified"))
      (node (ref "X8") (pin "4") (pinfunction "GND_4") (pintype "unspecified"))
    )
    (net (code "48") (name "GPIO_0") (class "Default")
      (node (ref "H1") (pin "5") (pinfunction "5_5") (pintype "unspecified"))
    )
    (net (code "49") (name "GPIO_1") (class "Default")
      (node (ref "H1") (pin "6") (pinfunction "6_6") (pintype "unspecified"))
    )
    (net (code "50") (name "GPIO_2") (class "Default")
      (node (ref "H1") (pin "7") (pinfunction "7_7") (pintype "unspecified"))
    )
    (net (code "51") (name "GPIO_3") (class "Default")
      (node (ref "H1") (pin "8") (pinfunction "8_8") (pintype "unspecified"))
    )
    (net (code "52") (name "GPIO_4") (class "Default")
      (node (ref "H1") (pin "9") (pinfunction "9_9") (pintype "unspecified"))
    )
    (net (code "53") (name "GPIO_5") (class "Default")
      (node (ref "H1") (pin "10") (pinfunction "10_10") (pintype "unspecified"))
    )
    (net (code "54") (name "GPIO_6") (class "Default")
      (node (ref "H1") (pin "11") (pinfunction "11_11") (pintype "unspecified"))
    )
    (net (code "55") (name "GPIO_7") (class "Default")
      (node (ref "H1") (pin "12") (pinfunction "12_12") (pintype "unspecified"))
    )
    (net (code "56") (name "GPIO_8") (class "Default")
      (node (ref "H1") (pin "13") (pinfunction "13_13") (pintype "unspecified"))
    )
    (net (code "57") (name "GPIO_9") (class "Default")
      (node (ref "H1") (pin "14") (pinfunction "14_14") (pintype "unspecified"))
    )
    (net (code "58") (name "GPIO_10") (class "Default")
      (node (ref "H1") (pin "15") (pinfunction "15_15") (pintype "unspecified"))
    )
    (net (code "59") (name "GPIO_11") (class "Default")
      (node (ref "H1") (pin "16") (pinfunction "16_16") (pintype "unspecified"))
    )
    (net (code "60") (name "GPIO_12") (class "Default")
      (node (ref "H1") (pin "17") (pinfunction "17_17") (pintype "unspecified"))
    )
    (net (code "61") (name "GPIO_13") (class "Default")
      (node (ref "H1") (pin "18") (pinfunction "18_18") (pintype "unspecified"))
    )
    (net (code "62") (name "GPIO_14") (class "Default")
      (node (ref "H1") (pin "19") (pinfunction "19_19") (pintype "unspecified"))
    )
    (net (code "63") (name "GPIO_15") (class "Default")
      (node (ref "H1") (pin "20") (pinfunction "20_20") (pintype "unspecified"))
    )
    (net (code "64") (name "HDMI_CLKN") (class "Default")
      (node (ref "C135") (pin "1") (pinfunction "1_1") (pintype "input"))
      (node (ref "D3") (pin "1") (pinfunction "1_1") (pintype "unspecified"))
      (node (ref "U25") (pin "B1") (pinfunction "IO,_DIFFIO_L2n,_(DQ2L)/(DQ1L)/(DQ1L)_B1") (pintype "bidirectional"))
    )
    (net (code "65") (name "HDMI_CLKP") (class "Default")
      (node (ref "C142") (pin "1") (pinfunction "1_1") (pintype "input"))
      (node (ref "D3") (pin "3") (pinfunction "3_3") (pintype "unspecified"))
      (node (ref "U25") (pin "B2") (pinfunction "IO,_DIFFIO_L2p,_(DQ2L)/(DQ1L)/(DQ1L)_B2") (pintype "bidirectional"))
    )
    (net (code "66") (name "HDMI_D0N") (class "Default")
      (node (ref "C141") (pin "1") (pinfunction "1_1") (pintype "input"))
      (node (ref "D3") (pin "4") (pinfunction "4_4") (pintype "unspecified"))
      (node (ref "U25") (pin "C1") (pinfunction "IO,_DIFFIO_L7n,_(DQ2L)/(DQ1L)/(DQ1L)_C1") (pintype "bidirectional"))
    )
    (net (code "67") (name "HDMI_D0P") (class "Default")
      (node (ref "C140") (pin "1") (pinfunction "1_1") (pintype "input"))
      (node (ref "D3") (pin "6") (pinfunction "6_6") (pintype "unspecified"))
      (node (ref "U25") (pin "C2") (pinfunction "IO,_DIFFIO_L7p,_(DQS2L/CQ3L,CDPCLK0)/(DQS2L/CQ3L,CDPCLK0)/(DQS2L/CQ3L,CDPCLK0)_C2") (pintype "bidirectional"))
    )
    (net (code "68") (name "HDMI_D1N") (class "Default")
      (node (ref "C139") (pin "1") (pinfunction "1_1") (pintype "input"))
      (node (ref "D2") (pin "1") (pinfunction "1_1") (pintype "unspecified"))
      (node (ref "U25") (pin "E3") (pinfunction "IO,_DIFFIO_L4n,_(DQ2L)/(DQ1L)/(DQ1L)_E3") (pintype "bidirectional"))
    )
    (net (code "69") (name "HDMI_D1P") (class "Default")
      (node (ref "C138") (pin "1") (pinfunction "1_1") (pintype "input"))
      (node (ref "D2") (pin "3") (pinfunction "3_3") (pintype "unspecified"))
      (node (ref "U25") (pin "E4") (pinfunction "IO,_DIFFIO_L4p,_(nRESET),_(DQ2L)/(DQ1L)/(DQ1L)_E4") (pintype "bidirectional"))
    )
    (net (code "70") (name "HDMI_D2N") (class "Default")
      (node (ref "C137") (pin "1") (pinfunction "1_1") (pintype "input"))
      (node (ref "D2") (pin "4") (pinfunction "4_4") (pintype "unspecified"))
      (node (ref "U25") (pin "F1") (pinfunction "IO,_DIFFIO_L12n,_(DQ0L)/(DQ1L)/(DQ1L)_F1") (pintype "bidirectional"))
    )
    (net (code "71") (name "HDMI_D2P") (class "Default")
      (node (ref "C136") (pin "1") (pinfunction "1_1") (pintype "input"))
      (node (ref "D2") (pin "6") (pinfunction "6_6") (pintype "unspecified"))
      (node (ref "U25") (pin "F2") (pinfunction "IO,_DIFFIO_L12p,_(DM2L)/(DM1L/BWS#1L)/(DM1L/BWS#1L)_F2") (pintype "bidirectional"))
    )
    (net (code "72") (name "IO_SW1") (class "Default")
      (node (ref "R136") (pin "2") (pinfunction "2_2") (pintype "unspecified"))
      (node (ref "SW5") (pin "5") (pinfunction "B4_5") (pintype "input"))
      (node (ref "U25") (pin "U1") (pinfunction "IO,_DIFFIO_L35n,_(DQ3L)/(DQ3L)/(DQ1L)_U1") (pintype "bidirectional"))
    )
    (net (code "73") (name "IO_SW2") (class "Default")
      (node (ref "R137") (pin "2") (pinfunction "2_2") (pintype "unspecified"))
      (node (ref "SW5") (pin "6") (pinfunction "B3_6") (pintype "input"))
      (node (ref "U25") (pin "U2") (pinfunction "IO,_DIFFIO_L35p,_(DM1L/BWS#1L)/(DM3L/BWS#3L)/(DM1L/BWS#1L)_U2") (pintype "bidirectional"))
    )
    (net (code "74") (name "IO_SW3") (class "Default")
      (node (ref "R138") (pin "2") (pinfunction "2_2") (pintype "unspecified"))
      (node (ref "SW5") (pin "7") (pinfunction "B2_7") (pintype "input"))
      (node (ref "U25") (pin "T4") (pinfunction "IO,_(DQS3L/CQ3L#,CDPCLK1)/(DQS3L/CQ3L#,CDPCLK1)/(DQS3L/CQ3L#,CDPCLK1)_T4") (pintype "bidirectional"))
    )
    (net (code "75") (name "IO_SW4") (class "Default")
      (node (ref "R139") (pin "2") (pinfunction "2_2") (pintype "unspecified"))
      (node (ref "SW5") (pin "8") (pinfunction "B1_8") (pintype "input"))
      (node (ref "U25") (pin "T5") (pinfunction "IO,_(DM3L/BWS#3L)/(DM3L/BWS#3L)/(DM1L/BWS#1L)_T5") (pintype "bidirectional"))
    )
    (net (code "76") (name "JTAG_TCK") (class "Default")
      (node (ref "P1") (pin "1") (pinfunction "1_1") (pintype "input"))
      (node (ref "R148") (pin "1") (pinfunction "1_1") (pintype "unspecified"))
      (node (ref "U25") (pin "L2") (pinfunction "TCK_L2") (pintype "input"))
    )
    (net (code "77") (name "JTAG_TDI") (class "Default")
      (node (ref "P1") (pin "9") (pinfunction "9_9") (pintype "input"))
      (node (ref "R141") (pin "2") (pinfunction "2_2") (pintype "unspecified"))
      (node (ref "U25") (pin "L5") (pinfunction "TDI_L5") (pintype "input"))
    )
    (net (code "78") (name "JTAG_TDO") (class "Default")
      (node (ref "P1") (pin "3") (pinfunction "3_3") (pintype "input"))
      (node (ref "U25") (pin "L4") (pinfunction "TDO_L4") (pintype "output"))
    )
    (net (code "79") (name "JTAG_TMS") (class "Default")
      (node (ref "P1") (pin "5") (pinfunction "5_5") (pintype "input"))
      (node (ref "R142") (pin "2") (pinfunction "2_2") (pintype "unspecified"))
      (node (ref "U25") (pin "L1") (pinfunction "TMS_L1") (pintype "input"))
    )
    (net (code "80") (name "LED_ETH") (class "Default")
      (node (ref "LED9") (pin "2") (pinfunction "A_2") (pintype "unspecified"))
      (node (ref "U25") (pin "J4") (pinfunction "IO,_(DQS0L/CQ1L,DPCLK0)/(DQS0L/CQ1L,DPCLK0)/(DQS0L/CQ1L,DPCLK0)_J4") (pintype "bidirectional"))
    )
    (net (code "81") (name "LED_FLASH") (class "Default")
      (node (ref "LED7") (pin "2") (pinfunction "A_2") (pintype "unspecified"))
      (node (ref "U25") (pin "P3") (pinfunction "IO,_DIFFIO_L34n,_(DQ1L)/(DQ3L)/(DQ1L)_P3") (pintype "bidirectional"))
    )
    (net (code "82") (name "LED_GPU") (class "Default")
      (node (ref "LED6") (pin "2") (pinfunction "A_2") (pintype "unspecified"))
      (node (ref "U25") (pin "W2") (pinfunction "IO,_DIFFIO_L44p,_(DQ3L)/(DQ3L)/(DQ1L)_W2") (pintype "bidirectional"))
    )
    (net (code "83") (name "LED_USB") (class "Default")
      (node (ref "LED8") (pin "2") (pinfunction "A_2") (pintype "unspecified"))
      (node (ref "U25") (pin "P6") (pinfunction "IO,_DIFFIO_L52p_P6") (pintype "bidirectional"))
    )
    (net (code "84") (name "LED_USER") (class "Default")
      (node (ref "LED11") (pin "2") (pinfunction "A_2") (pintype "unspecified"))
      (node (ref "U25") (pin "R2") (pinfunction "IO,_DIFFIO_L33p,_(DQ1L)/(DQ3L)/(DQ1L)_R2") (pintype "bidirectional"))
    )
    (net (code "85") (name "Net-(C49-Pad2)") (class "Default")
      (node (ref "C49") (pin "2") (pinfunction "2_2") (pintype "unspecified"))
      (node (ref "R27") (pin "1") (pinfunction "1_1") (pintype "input"))
    )
    (net (code "86") (name "Net-(C50-Pad2)") (class "Default")
      (node (ref "C50") (pin "2") (pinfunction "2_2") (pintype "unspecified"))
      (node (ref "R28") (pin "1") (pinfunction "1_1") (pintype "input"))
    )
    (net (code "87") (name "Net-(C163-Pad1)") (class "Default")
      (node (ref "C163") (pin "1") (pinfunction "1_1") (pintype "input"))
      (node (ref "R152") (pin "2") (pinfunction "2_2") (pintype "unspecified"))
      (node (ref "R153") (pin "2") (pinfunction "2_2") (pintype "unspecified"))
    )
    (net (code "88") (name "Net-(C164-Pad1)") (class "Default")
      (node (ref "C164") (pin "1") (pinfunction "1_1") (pintype "input"))
      (node (ref "J1") (pin "4") (pinfunction "4_4") (pintype "unspecified"))
      (node (ref "L2") (pin "1") (pinfunction "1_1") (pintype "unspecified"))
      (node (ref "R154") (pin "2") (pinfunction "2_2") (pintype "unspecified"))
      (node (ref "R155") (pin "2") (pinfunction "2_2") (pintype "unspecified"))
    )
    (net (code "89") (name "Net-(D4-K)") (class "Default")
      (node (ref "D4") (pin "1") (pinfunction "K_1") (pintype "unspecified"))
      (node (ref "HDMI1") (pin "18") (pinfunction "+5VPower_18") (pintype "unspecified"))
    )
    (net (code "90") (name "Net-(F1-Pad2)") (class "Default")
      (node (ref "F1") (pin "2") (pinfunction "2_2") (pintype "unspecified"))
      (node (ref "U11") (pin "2") (pinfunction "2_2") (pintype "unspecified"))
    )
    (net (code "91") (name "Net-(H2-Pad2)") (class "Default")
      (node (ref "H2") (pin "2") (pinfunction "2_2") (pintype "unspecified"))
      (node (ref "R109") (pin "1") (pinfunction "1_1") (pintype "unspecified"))
      (node (ref "R118") (pin "1") (pinfunction "1_1") (pintype "unspecified"))
    )
    (net (code "92") (name "Net-(HDMI1-TMDSClock+)") (class "Default")
      (node (ref "C142") (pin "2") (pinfunction "2_2") (pintype "input"))
      (node (ref "HDMI1") (pin "10") (pinfunction "TMDSClock+_10") (pintype "unspecified"))
    )
    (net (code "93") (name "Net-(HDMI1-TMDSClock-)") (class "Default")
      (node (ref "C135") (pin "2") (pinfunction "2_2") (pintype "input"))
      (node (ref "HDMI1") (pin "12") (pinfunction "TMDSClock-_12") (pintype "unspecified"))
    )
    (net (code "94") (name "Net-(HDMI1-TMDSData0+)") (class "Default")
      (node (ref "C140") (pin "2") (pinfunction "2_2") (pintype "input"))
      (node (ref "HDMI1") (pin "7") (pinfunction "TMDSData0+_7") (pintype "unspecified"))
    )
    (net (code "95") (name "Net-(HDMI1-TMDSData0-)") (class "Default")
      (node (ref "C141") (pin "2") (pinfunction "2_2") (pintype "input"))
      (node (ref "HDMI1") (pin "9") (pinfunction "TMDSData0-_9") (pintype "unspecified"))
    )
    (net (code "96") (name "Net-(HDMI1-TMDSData1+)") (class "Default")
      (node (ref "C138") (pin "2") (pinfunction "2_2") (pintype "input"))
      (node (ref "HDMI1") (pin "4") (pinfunction "TMDSData1+_4") (pintype "unspecified"))
    )
    (net (code "97") (name "Net-(HDMI1-TMDSData1-)") (class "Default")
      (node (ref "C139") (pin "2") (pinfunction "2_2") (pintype "input"))
      (node (ref "HDMI1") (pin "6") (pinfunction "TMDSData1-_6") (pintype "unspecified"))
    )
    (net (code "98") (name "Net-(HDMI1-TMDSData2+)") (class "Default")
      (node (ref "C136") (pin "2") (pinfunction "2_2") (pintype "input"))
      (node (ref "HDMI1") (pin "1") (pinfunction "TMDSData2+_1") (pintype "unspecified"))
    )
    (net (code "99") (name "Net-(HDMI1-TMDSData2-)") (class "Default")
      (node (ref "C137") (pin "2") (pinfunction "2_2") (pintype "input"))
      (node (ref "HDMI1") (pin "3") (pinfunction "TMDSData2-_3") (pintype "unspecified"))
    )
    (net (code "100") (name "Net-(J1-Pad9)") (class "Default")
      (node (ref "J1") (pin "9") (pinfunction "9_9") (pintype "unspecified"))
      (node (ref "R147") (pin "2") (pinfunction "2_2") (pintype "unspecified"))
    )
    (net (code "101") (name "Net-(J1-Pad12)") (class "Default")
      (node (ref "J1") (pin "12") (pinfunction "12_12") (pintype "unspecified"))
      (node (ref "R146") (pin "2") (pinfunction "2_2") (pintype "unspecified"))
    )
    (net (code "102") (name "Net-(J1-RD+)") (class "Default")
      (node (ref "J1") (pin "3") (pinfunction "RD+_3") (pintype "unspecified"))
      (node (ref "R153") (pin "1") (pinfunction "1_1") (pintype "unspecified"))
      (node (ref "U26") (pin "13") (pinfunction "TPIN+_13") (pintype "unspecified"))
    )
    (net (code "103") (name "Net-(J1-RD-)") (class "Default")
      (node (ref "J1") (pin "6") (pinfunction "RD-_6") (pintype "unspecified"))
      (node (ref "R152") (pin "1") (pinfunction "1_1") (pintype "unspecified"))
      (node (ref "U26") (pin "12") (pinfunction "TPIN-_12") (pintype "unspecified"))
    )
    (net (code "104") (name "Net-(J1-TD+)") (class "Default")
      (node (ref "J1") (pin "1") (pinfunction "TD+_1") (pintype "unspecified"))
      (node (ref "R155") (pin "1") (pinfunction "1_1") (pintype "unspecified"))
      (node (ref "U26") (pin "17") (pinfunction "TPOUT+_17") (pintype "unspecified"))
    )
    (net (code "105") (name "Net-(J1-TD-)") (class "Default")
      (node (ref "J1") (pin "2") (pinfunction "TD-_2") (pintype "unspecified"))
      (node (ref "R154") (pin "1") (pinfunction "1_1") (pintype "unspecified"))
      (node (ref "U26") (pin "16") (pinfunction "TPOUT-_16") (pintype "unspecified"))
    )
    (net (code "106") (name "Net-(LED1-K)") (class "Default")
      (node (ref "LED1") (pin "1") (pinfunction "K_1") (pintype "unspecified"))
      (node (ref "R140") (pin "2") (pinfunction "2_2") (pintype "input"))
    )
    (net (code "107") (name "Net-(LED2-A)") (class "Default")
      (node (ref "LED2") (pin "2") (pinfunction "A_2") (pintype "unspecified"))
      (node (ref "LED3") (pin "1") (pinfunction "K_1") (pintype "unspecified"))
      (node (ref "U5") (pin "2") (pinfunction "LED1_2") (pintype "unspecified"))
    )
    (net (code "108") (name "Net-(LED2-K)") (class "Default")
      (node (ref "LED2") (pin "1") (pinfunction "K_1") (pintype "unspecified"))
      (node (ref "LED3") (pin "2") (pinfunction "A_2") (pintype "unspecified"))
      (node (ref "LED4") (pin "1") (pinfunction "K_1") (pintype "unspecified"))
      (node (ref "LED5") (pin "2") (pinfunction "A_2") (pintype "unspecified"))
      (node (ref "U5") (pin "4") (pinfunction "LED3_4") (pintype "unspecified"))
    )
    (net (code "109") (name "Net-(LED4-A)") (class "Default")
      (node (ref "LED4") (pin "2") (pinfunction "A_2") (pintype "unspecified"))
      (node (ref "LED5") (pin "1") (pinfunction "K_1") (pintype "unspecified"))
      (node (ref "U5") (pin "3") (pinfunction "LED2_3") (pintype "unspecified"))
    )
    (net (code "110") (name "Net-(LED6-K)") (class "Default")
      (node (ref "LED6") (pin "1") (pinfunction "K_1") (pintype "unspecified"))
      (node (ref "R128") (pin "2") (pinfunction "2_2") (pintype "input"))
    )
    (net (code "111") (name "Net-(LED7-K)") (class "Default")
      (node (ref "LED7") (pin "1") (pinfunction "K_1") (pintype "unspecified"))
      (node (ref "R129") (pin "2") (pinfunction "2_2") (pintype "input"))
    )
    (net (code "112") (name "Net-(LED8-K)") (class "Default")
      (node (ref "LED8") (pin "1") (pinfunction "K_1") (pintype "unspecified"))
      (node (ref "R130") (pin "2") (pinfunction "2_2") (pintype "input"))
    )
    (net (code "113") (name "Net-(LED9-K)") (class "Default")
      (node (ref "LED9") (pin "1") (pinfunction "K_1") (pintype "unspecified"))
      (node (ref "R131") (pin "2") (pinfunction "2_2") (pintype "input"))
    )
    (net (code "114") (name "Net-(LED10-K)") (class "Default")
      (node (ref "LED10") (pin "1") (pinfunction "K_1") (pintype "unspecified"))
      (node (ref "R132") (pin "2") (pinfunction "2_2") (pintype "input"))
    )
    (net (code "115") (name "Net-(LED11-K)") (class "Default")
      (node (ref "LED11") (pin "1") (pinfunction "K_1") (pintype "unspecified"))
      (node (ref "R133") (pin "2") (pinfunction "2_2") (pintype "input"))
    )
    (net (code "116") (name "Net-(LED12-K)") (class "Default")
      (node (ref "LED12") (pin "1") (pinfunction "K_1") (pintype "unspecified"))
      (node (ref "R100") (pin "2") (pinfunction "2_2") (pintype "input"))
    )
    (net (code "117") (name "Net-(LED13-K)") (class "Default")
      (node (ref "LED13") (pin "1") (pinfunction "K_1") (pintype "unspecified"))
      (node (ref "R101") (pin "2") (pinfunction "2_2") (pintype "input"))
    )
    (net (code "118") (name "Net-(R29-Pad1)") (class "Default")
      (node (ref "R29") (pin "1") (pinfunction "1_1") (pintype "input"))
      (node (ref "SW3") (pin "1") (pinfunction "1_1") (pintype "input"))
    )
    (net (code "119") (name "Net-(R103-Pad1)") (class "Default")
      (node (ref "R103") (pin "1") (pinfunction "1_1") (pintype "unspecified"))
      (node (ref "R104") (pin "2") (pinfunction "2_2") (pintype "unspecified"))
      (node (ref "R112") (pin "1") (pinfunction "1_1") (pintype "unspecified"))
    )
    (net (code "120") (name "Net-(R103-Pad2)") (class "Default")
      (node (ref "R103") (pin "2") (pinfunction "2_2") (pintype "unspecified"))
      (node (ref "R110") (pin "1") (pinfunction "1_1") (pintype "unspecified"))
      (node (ref "R111") (pin "2") (pinfunction "2_2") (pintype "unspecified"))
    )
    (net (code "121") (name "Net-(R104-Pad1)") (class "Default")
      (node (ref "R104") (pin "1") (pinfunction "1_1") (pintype "unspecified"))
      (node (ref "R105") (pin "2") (pinfunction "2_2") (pintype "unspecified"))
      (node (ref "R113") (pin "1") (pinfunction "1_1") (pintype "unspecified"))
    )
    (net (code "122") (name "Net-(R105-Pad1)") (class "Default")
      (node (ref "R105") (pin "1") (pinfunction "1_1") (pintype "unspecified"))
      (node (ref "R106") (pin "2") (pinfunction "2_2") (pintype "unspecified"))
      (node (ref "R114") (pin "1") (pinfunction "1_1") (pintype "unspecified"))
    )
    (net (code "123") (name "Net-(R106-Pad1)") (class "Default")
      (node (ref "R106") (pin "1") (pinfunction "1_1") (pintype "unspecified"))
      (node (ref "R107") (pin "2") (pinfunction "2_2") (pintype "unspecified"))
      (node (ref "R115") (pin "1") (pinfunction "1_1") (pintype "unspecified"))
    )
    (net (code "124") (name "Net-(R107-Pad1)") (class "Default")
      (node (ref "R107") (pin "1") (pinfunction "1_1") (pintype "unspecified"))
      (node (ref "R108") (pin "2") (pinfunction "2_2") (pintype "unspecified"))
      (node (ref "R116") (pin "1") (pinfunction "1_1") (pintype "unspecified"))
    )
    (net (code "125") (name "Net-(R108-Pad1)") (class "Default")
      (node (ref "R108") (pin "1") (pinfunction "1_1") (pintype "unspecified"))
      (node (ref "R109") (pin "2") (pinfunction "2_2") (pintype "unspecified"))
      (node (ref "R117") (pin "1") (pinfunction "1_1") (pintype "unspecified"))
    )
    (net (code "126") (name "Net-(U2-IO2)") (class "Default")
      (node (ref "R149") (pin "2") (pinfunction "2_2") (pintype "unspecified"))
      (node (ref "U2") (pin "3") (pinfunction "IO2_3") (pintype "unspecified"))
    )
    (net (code "127") (name "Net-(U2-IO3)") (class "Default")
      (node (ref "R150") (pin "1") (pinfunction "1_1") (pintype "unspecified"))
      (node (ref "U2") (pin "7") (pinfunction "IO3_7") (pintype "unspecified"))
    )
    (net (code "128") (name "Net-(U4-EN)") (class "Default")
      (node (ref "R125") (pin "2") (pinfunction "2_2") (pintype "unspecified"))
      (node (ref "U4") (pin "5") (pinfunction "EN_5") (pintype "unspecified"))
    )
    (net (code "129") (name "Net-(U4-SW)") (class "Default")
      (node (ref "C170") (pin "2") (pinfunction "2_2") (pintype "input"))
      (node (ref "U3") (pin "2") (pinfunction "2_2") (pintype "input"))
      (node (ref "U4") (pin "2") (pinfunction "SW_2") (pintype "unspecified"))
    )
    (net (code "130") (name "Net-(U4-VBST)") (class "Default")
      (node (ref "C170") (pin "1") (pinfunction "1_1") (pintype "input"))
      (node (ref "U4") (pin "6") (pinfunction "VBST_6") (pintype "unspecified"))
    )
    (net (code "131") (name "Net-(U4-VFB)") (class "Default")
      (node (ref "R30") (pin "2") (pinfunction "2_2") (pintype "input"))
      (node (ref "R31") (pin "1") (pinfunction "1_1") (pintype "input"))
      (node (ref "U4") (pin "4") (pinfunction "VFB_4") (pintype "unspecified"))
    )
    (net (code "132") (name "Net-(U5-KEY)") (class "Default")
      (node (ref "R29") (pin "2") (pinfunction "2_2") (pintype "input"))
      (node (ref "U5") (pin "5") (pinfunction "KEY_5") (pintype "unspecified"))
    )
    (net (code "133") (name "Net-(U5-SW)") (class "Default")
      (node (ref "L1") (pin "1") (pinfunction "1_1") (pintype "input"))
      (node (ref "U5") (pin "7") (pinfunction "SW_7") (pintype "unspecified"))
    )
    (net (code "134") (name "Net-(U7-VDD)") (class "Default")
      (node (ref "C172") (pin "2") (pinfunction "2_2") (pintype "input"))
      (node (ref "R32") (pin "2") (pinfunction "2_2") (pintype "input"))
      (node (ref "U7") (pin "1") (pinfunction "VDD_1") (pintype "unspecified"))
    )
    (net (code "135") (name "Net-(U8-EN)") (class "Default")
      (node (ref "R126") (pin "2") (pinfunction "2_2") (pintype "unspecified"))
      (node (ref "U8") (pin "5") (pinfunction "EN_5") (pintype "unspecified"))
    )
    (net (code "136") (name "Net-(U8-SW)") (class "Default")
      (node (ref "C169") (pin "2") (pinfunction "2_2") (pintype "input"))
      (node (ref "U6") (pin "2") (pinfunction "2_2") (pintype "input"))
      (node (ref "U8") (pin "2") (pinfunction "SW_2") (pintype "unspecified"))
    )
    (net (code "137") (name "Net-(U8-VBST)") (class "Default")
      (node (ref "C169") (pin "1") (pinfunction "1_1") (pintype "input"))
      (node (ref "U8") (pin "6") (pinfunction "VBST_6") (pintype "unspecified"))
    )
    (net (code "138") (name "Net-(U8-VFB)") (class "Default")
      (node (ref "R34") (pin "1") (pinfunction "1_1") (pintype "input"))
      (node (ref "R35") (pin "1") (pinfunction "1_1") (pintype "input"))
      (node (ref "U8") (pin "4") (pinfunction "VFB_4") (pintype "unspecified"))
    )
    (net (code "139") (name "Net-(U13-EN)") (class "Default")
      (node (ref "R127") (pin "2") (pinfunction "2_2") (pintype "unspecified"))
      (node (ref "U13") (pin "5") (pinfunction "EN_5") (pintype "unspecified"))
    )
    (net (code "140") (name "Net-(U13-SW)") (class "Default")
      (node (ref "C168") (pin "2") (pinfunction "2_2") (pintype "input"))
      (node (ref "U12") (pin "2") (pinfunction "2_2") (pintype "input"))
      (node (ref "U13") (pin "2") (pinfunction "SW_2") (pintype "unspecified"))
    )
    (net (code "141") (name "Net-(U13-VBST)") (class "Default")
      (node (ref "C168") (pin "1") (pinfunction "1_1") (pintype "input"))
      (node (ref "U13") (pin "6") (pinfunction "VBST_6") (pintype "unspecified"))
    )
    (net (code "142") (name "Net-(U13-VFB)") (class "Default")
      (node (ref "R37") (pin "1") (pinfunction "1_1") (pintype "input"))
      (node (ref "R38") (pin "1") (pinfunction "1_1") (pintype "input"))
      (node (ref "U13") (pin "4") (pinfunction "VFB_4") (pintype "unspecified"))
    )
    (net (code "143") (name "Net-(U18-RSTI)") (class "Default")
      (node (ref "C175") (pin "1") (pinfunction "1_1") (pintype "input"))
      (node (ref "U18") (pin "2") (pinfunction "RSTI_2") (pintype "unspecified"))
    )
    (net (code "144") (name "Net-(U18-UD+)") (class "Default")
      (node (ref "D1") (pin "1") (pinfunction "1_1") (pintype "unspecified"))
      (node (ref "U18") (pin "8") (pinfunction "UD+_8") (pintype "unspecified"))
      (node (ref "USB1") (pin "7") (pinfunction "D+_7") (pintype "unspecified"))
    )
    (net (code "145") (name "Net-(U18-UD-)") (class "Default")
      (node (ref "D1") (pin "3") (pinfunction "3_3") (pintype "unspecified"))
      (node (ref "U18") (pin "9") (pinfunction "UD-_9") (pintype "unspecified"))
      (node (ref "USB1") (pin "6") (pinfunction "D-_6") (pintype "unspecified"))
    )
    (net (code "146") (name "Net-(U18-XI)") (class "Default")
      (node (ref "C156") (pin "2") (pinfunction "2_2") (pintype "input"))
      (node (ref "U18") (pin "11") (pinfunction "XI_11") (pintype "unspecified"))
      (node (ref "X6") (pin "3") (pinfunction "OSC2_3") (pintype "unspecified"))
    )
    (net (code "147") (name "Net-(U18-XO)") (class "Default")
      (node (ref "C157") (pin "2") (pinfunction "2_2") (pintype "input"))
      (node (ref "U18") (pin "12") (pinfunction "XO_12") (pintype "unspecified"))
      (node (ref "X6") (pin "1") (pinfunction "OSC1_1") (pintype "unspecified"))
    )
    (net (code "148") (name "Net-(U19-RSTI)") (class "Default")
      (node (ref "C174") (pin "2") (pinfunction "2_2") (pintype "input"))
      (node (ref "U19") (pin "2") (pinfunction "RSTI_2") (pintype "unspecified"))
    )
    (net (code "149") (name "Net-(U19-UD+)") (class "Default")
      (node (ref "D1") (pin "6") (pinfunction "6_6") (pintype "unspecified"))
      (node (ref "U19") (pin "8") (pinfunction "UD+_8") (pintype "unspecified"))
      (node (ref "USB1") (pin "3") (pinfunction "D+_3") (pintype "unspecified"))
    )
    (net (code "150") (name "Net-(U19-UD-)") (class "Default")
      (node (ref "D1") (pin "4") (pinfunction "4_4") (pintype "unspecified"))
      (node (ref "U19") (pin "9") (pinfunction "UD-_9") (pintype "unspecified"))
      (node (ref "USB1") (pin "2") (pinfunction "D-_2") (pintype "unspecified"))
    )
    (net (code "151") (name "Net-(U19-XI)") (class "Default")
      (node (ref "C154") (pin "2") (pinfunction "2_2") (pintype "input"))
      (node (ref "U19") (pin "11") (pinfunction "XI_11") (pintype "unspecified"))
      (node (ref "X5") (pin "3") (pinfunction "OSC2_3") (pintype "unspecified"))
    )
    (net (code "152") (name "Net-(U19-XO)") (class "Default")
      (node (ref "C155") (pin "2") (pinfunction "2_2") (pintype "input"))
      (node (ref "U19") (pin "12") (pinfunction "XO_12") (pintype "unspecified"))
      (node (ref "X5") (pin "1") (pinfunction "OSC1_1") (pintype "unspecified"))
    )
    (net (code "153") (name "Net-(U23-D+)") (class "Default")
      (node (ref "U23") (pin "5") (pinfunction "D+_5") (pintype "unspecified"))
      (node (ref "USB2") (pin "6") (pinfunction "DP1_6") (pintype "unspecified"))
      (node (ref "USB2") (pin "8") (pinfunction "DP2_8") (pintype "unspecified"))
    )
    (net (code "154") (name "Net-(U23-D-)") (class "Default")
      (node (ref "U23") (pin "6") (pinfunction "D-_6") (pintype "unspecified"))
      (node (ref "USB2") (pin "5") (pinfunction "DN2_5") (pintype "unspecified"))
      (node (ref "USB2") (pin "7") (pinfunction "DN1_7") (pintype "unspecified"))
    )
    (net (code "155") (name "Net-(U25J-nSTATUS)") (class "Default")
      (node (ref "R143") (pin "1") (pinfunction "1_1") (pintype "unspecified"))
      (node (ref "U25") (pin "K6") (pinfunction "nSTATUS_K6") (pintype "bidirectional"))
    )
    (net (code "156") (name "Net-(U26-LEDA)") (class "Default")
      (node (ref "R147") (pin "1") (pinfunction "1_1") (pintype "unspecified"))
      (node (ref "U26") (pin "27") (pinfunction "LEDA_27") (pintype "unspecified"))
    )
    (net (code "157") (name "Net-(U26-LEDB)") (class "Default")
      (node (ref "R146") (pin "1") (pinfunction "1_1") (pintype "unspecified"))
      (node (ref "U26") (pin "26") (pinfunction "LEDB_26") (pintype "unspecified"))
    )
    (net (code "158") (name "Net-(U26-OSC1)") (class "Default")
      (node (ref "C158") (pin "2") (pinfunction "2_2") (pintype "input"))
      (node (ref "U26") (pin "23") (pinfunction "OSC1_23") (pintype "unspecified"))
      (node (ref "X8") (pin "3") (pinfunction "OSC2_3") (pintype "unspecified"))
    )
    (net (code "159") (name "Net-(U26-OSC2)") (class "Default")
      (node (ref "C159") (pin "2") (pinfunction "2_2") (pintype "input"))
      (node (ref "U26") (pin "24") (pinfunction "OSC2_24") (pintype "unspecified"))
      (node (ref "X8") (pin "1") (pinfunction "OSC1_1") (pintype "unspecified"))
    )
    (net (code "160") (name "Net-(U26-RBIAS)") (class "Default")
      (node (ref "R151") (pin "2") (pinfunction "2_2") (pintype "input"))
      (node (ref "U26") (pin "14") (pinfunction "RBIAS_14") (pintype "unspecified"))
    )
    (net (code "161") (name "Net-(U26-RESET#)") (class "Default")
      (node (ref "R134") (pin "1") (pinfunction "1_1") (pintype "unspecified"))
      (node (ref "U26") (pin "10") (pinfunction "RESET#_10") (pintype "unspecified"))
    )
    (net (code "162") (name "Net-(U26-VCAP)") (class "Default")
      (node (ref "C98") (pin "2") (pinfunction "2_2") (pintype "unspecified"))
      (node (ref "U26") (pin "1") (pinfunction "VCAP_1") (pintype "unspecified"))
    )
    (net (code "163") (name "Net-(USB2-CC1)") (class "Default")
      (node (ref "R99") (pin "1") (pinfunction "1_1") (pintype "unspecified"))
      (node (ref "USB2") (pin "4") (pinfunction "CC1_4") (pintype "unspecified"))
    )
    (net (code "164") (name "Net-(USB2-CC2)") (class "Default")
      (node (ref "R98") (pin "1") (pinfunction "1_1") (pintype "unspecified"))
      (node (ref "USB2") (pin "10") (pinfunction "CC2_10") (pintype "unspecified"))
    )
    (net (code "165") (name "Net-(X1-Tri-state)") (class "Default")
      (node (ref "R119") (pin "1") (pinfunction "1_1") (pintype "input"))
      (node (ref "X1") (pin "1") (pinfunction "Tri-state_1") (pintype "unspecified"))
    )
    (net (code "166") (name "SDRAM_A0") (class "Default")
      (node (ref "U14") (pin "23") (pinfunction "A0_23") (pintype "unspecified"))
      (node (ref "U15") (pin "23") (pinfunction "A0_23") (pintype "unspecified"))
      (node (ref "U25") (pin "R19") (pinfunction "IO,_DIFFIO_R42p,_(DM1R/BWS#1R)/(DM3R/BWS#3R)/(DM1R/BWS#1R)_R19") (pintype "bidirectional"))
    )
    (net (code "167") (name "SDRAM_A1") (class "Default")
      (node (ref "U14") (pin "24") (pinfunction "A1_24") (pintype "unspecified"))
      (node (ref "U15") (pin "24") (pinfunction "A1_24") (pintype "unspecified"))
      (node (ref "U25") (pin "N20") (pinfunction "IO,_DIFFIO_R36n,_(DQ1R)/(DQ3R)/(DQ1R)_N20") (pintype "bidirectional"))
    )
    (net (code "168") (name "SDRAM_A2") (class "Default")
      (node (ref "U14") (pin "25") (pinfunction "A2_25") (pintype "unspecified"))
      (node (ref "U15") (pin "25") (pinfunction "A2_25") (pintype "unspecified"))
      (node (ref "U25") (pin "N19") (pinfunction "IO,_DIFFIO_R36p_N19") (pintype "bidirectional"))
    )
    (net (code "169") (name "SDRAM_A3") (class "Default")
      (node (ref "U14") (pin "26") (pinfunction "A3_26") (pintype "unspecified"))
      (node (ref "U15") (pin "26") (pinfunction "A3_26") (pintype "unspecified"))
      (node (ref "U25") (pin "H20") (pinfunction "IO,_DIFFIO_R13n,_(DQ0R)/(DQ1R)/(DQ1R)_H20") (pintype "bidirectional"))
    )
    (net (code "170") (name "SDRAM_A4") (class "Default")
      (node (ref "U14") (pin "29") (pinfunction "A4_29") (pintype "unspecified"))
      (node (ref "U15") (pin "29") (pinfunction "A4_29") (pintype "unspecified"))
      (node (ref "U25") (pin "H19") (pinfunction "IO,_DIFFIO_R13p,_(DQ0R)/(DQ1R)/(DQ1R)_H19") (pintype "bidirectional"))
    )
    (net (code "171") (name "SDRAM_A5") (class "Default")
      (node (ref "U14") (pin "30") (pinfunction "A5_30") (pintype "unspecified"))
      (node (ref "U15") (pin "30") (pinfunction "A5_30") (pintype "unspecified"))
      (node (ref "U25") (pin "F20") (pinfunction "IO,_DIFFIO_R8n,_(nAVD),_(DQ2R)/(DQ1R)/(DQ1R)_F20") (pintype "bidirectional"))
    )
    (net (code "172") (name "SDRAM_A6") (class "Default")
      (node (ref "U14") (pin "31") (pinfunction "A6_31") (pintype "unspecified"))
      (node (ref "U15") (pin "31") (pinfunction "A6_31") (pintype "unspecified"))
      (node (ref "U25") (pin "F19") (pinfunction "IO,_DIFFIO_R8p,_(DQ2R)/(DQ1R)/(DQ1R)_F19") (pintype "bidirectional"))
    )
    (net (code "173") (name "SDRAM_A7") (class "Default")
      (node (ref "U14") (pin "32") (pinfunction "A7_32") (pintype "unspecified"))
      (node (ref "U15") (pin "32") (pinfunction "A7_32") (pintype "unspecified"))
      (node (ref "U25") (pin "D19") (pinfunction "IO,_DIFFIO_T47p,_(DQ2T)/(DQ5T)/(DQ5T)_D19") (pintype "bidirectional"))
    )
    (net (code "174") (name "SDRAM_A8") (class "Default")
      (node (ref "U14") (pin "33") (pinfunction "A8_33") (pintype "unspecified"))
      (node (ref "U15") (pin "33") (pinfunction "A8_33") (pintype "unspecified"))
      (node (ref "U25") (pin "C20") (pinfunction "IO,_DIFFIO_R4n,_(PADD20),_(DQS2R/CQ3R,CDPCLK5)/(DQS2R/CQ3R,CDPCLK5)/(DQS2R/CQ3R,CDPCLK5)_C20") (pintype "bidirectional"))
    )
    (net (code "175") (name "SDRAM_A9") (class "Default")
      (node (ref "U14") (pin "34") (pinfunction "A9_34") (pintype "unspecified"))
      (node (ref "U15") (pin "34") (pinfunction "A9_34") (pintype "unspecified"))
      (node (ref "U25") (pin "C19") (pinfunction "IO,_DIFFIO_T47n,_(DQ2T)/(DQ5T)/(DQ5T)_C19") (pintype "bidirectional"))
    )
    (net (code "176") (name "SDRAM_A10") (class "Default")
      (node (ref "U14") (pin "22") (pinfunction "A10/AP_22") (pintype "unspecified"))
      (node (ref "U15") (pin "22") (pinfunction "A10/AP_22") (pintype "unspecified"))
      (node (ref "U25") (pin "R20") (pinfunction "IO,_DIFFIO_R44n,_(DQ3R)/(DQ3R)/(DQ1R)_R20") (pintype "bidirectional"))
    )
    (net (code "177") (name "SDRAM_A11") (class "Default")
      (node (ref "U14") (pin "35") (pinfunction "A11_35") (pintype "unspecified"))
      (node (ref "U15") (pin "35") (pinfunction "A11_35") (pintype "unspecified"))
      (node (ref "U25") (pin "A20") (pinfunction "IO,_PLL2_CLKOUTn_A20") (pintype "bidirectional"))
    )
    (net (code "178") (name "SDRAM_A12") (class "Default")
      (node (ref "U14") (pin "36") (pinfunction "A12_36") (pintype "unspecified"))
      (node (ref "U15") (pin "36") (pinfunction "A12_36") (pintype "unspecified"))
      (node (ref "U25") (pin "B19") (pinfunction "IO,_RUP4_B19") (pintype "bidirectional"))
    )
    (net (code "179") (name "SDRAM_BA0") (class "Default")
      (node (ref "U14") (pin "20") (pinfunction "BS0_20") (pintype "unspecified"))
      (node (ref "U15") (pin "20") (pinfunction "BS0_20") (pintype "unspecified"))
      (node (ref "U25") (pin "U20") (pinfunction "IO,_DIFFIO_R50n,_(DQ3R)/(DQ3R)/(DQ1R)_U20") (pintype "bidirectional"))
    )
    (net (code "180") (name "SDRAM_BA1") (class "Default")
      (node (ref "U14") (pin "21") (pinfunction "BS1_21") (pintype "unspecified"))
      (node (ref "U15") (pin "21") (pinfunction "BS1_21") (pintype "unspecified"))
      (node (ref "U25") (pin "U19") (pinfunction "IO,_DIFFIO_R50p_U19") (pintype "bidirectional"))
    )
    (net (code "181") (name "SDRAM_CAS") (class "Default")
      (node (ref "R95") (pin "2") (pinfunction "2_2") (pintype "input"))
      (node (ref "U14") (pin "17") (pinfunction "CAS#_17") (pintype "unspecified"))
      (node (ref "U15") (pin "17") (pinfunction "CAS#_17") (pintype "unspecified"))
      (node (ref "U25") (pin "Y21") (pinfunction "IO,_DIFFIO_R51p_Y21") (pintype "bidirectional"))
    )
    (net (code "182") (name "SDRAM_CKE") (class "Default")
      (node (ref "R94") (pin "2") (pinfunction "2_2") (pintype "input"))
      (node (ref "U14") (pin "37") (pinfunction "CKE_37") (pintype "unspecified"))
      (node (ref "U15") (pin "37") (pinfunction "CKE_37") (pintype "unspecified"))
      (node (ref "U25") (pin "A19") (pinfunction "IO,_RDN4_A19") (pintype "bidirectional"))
    )
    (net (code "183") (name "SDRAM_CLK") (class "Default")
      (node (ref "U14") (pin "38") (pinfunction "CLK_38") (pintype "unspecified"))
      (node (ref "U15") (pin "38") (pinfunction "CLK_38") (pintype "unspecified"))
      (node (ref "U25") (pin "B20") (pinfunction "IO,_PLL2_CLKOUTp_B20") (pintype "bidirectional"))
    )
    (net (code "184") (name "SDRAM_CS") (class "Default")
      (node (ref "R93") (pin "2") (pinfunction "2_2") (pintype "input"))
      (node (ref "U14") (pin "19") (pinfunction "CS#_19") (pintype "unspecified"))
      (node (ref "U15") (pin "19") (pinfunction "CS#_19") (pintype "unspecified"))
      (node (ref "U25") (pin "W20") (pinfunction "IO,_(DQS3R/CQ3R#,CDPCLK4)/(DQS3R/CQ3R#,CDPCLK4)/(DQS3R/CQ3R#,CDPCLK4)_W20") (pintype "bidirectional"))
    )
    (net (code "185") (name "SDRAM_DQ0") (class "Default")
      (node (ref "U14") (pin "2") (pinfunction "DQ0_2") (pintype "unspecified"))
      (node (ref "U25") (pin "W21") (pinfunction "IO,_DIFFIO_R49p,_(DQ3R)/(DQ3R)/(DQ1R)_W21") (pintype "bidirectional"))
    )
    (net (code "186") (name "SDRAM_DQ1") (class "Default")
      (node (ref "U14") (pin "4") (pinfunction "DQ1_4") (pintype "unspecified"))
      (node (ref "U25") (pin "W22") (pinfunction "IO,_DIFFIO_R49n,_(DQ3R)/(DQ3R)/(DQ1R)_W22") (pintype "bidirectional"))
    )
    (net (code "187") (name "SDRAM_DQ2") (class "Default")
      (node (ref "U14") (pin "5") (pinfunction "DQ2_5") (pintype "unspecified"))
      (node (ref "U25") (pin "V21") (pinfunction "IO,_DIFFIO_R45p,_(DQ3R)/(DQ3R)/(DQ1R)_V21") (pintype "bidirectional"))
    )
    (net (code "188") (name "SDRAM_DQ3") (class "Default")
      (node (ref "U14") (pin "7") (pinfunction "DQ3_7") (pintype "unspecified"))
      (node (ref "U25") (pin "V22") (pinfunction "IO,_DIFFIO_R45n,_(DQ3R)/(DQ3R)/(DQ1R)_V22") (pintype "bidirectional"))
    )
    (net (code "189") (name "SDRAM_DQ4") (class "Default")
      (node (ref "U14") (pin "8") (pinfunction "DQ4_8") (pintype "unspecified"))
      (node (ref "U25") (pin "U21") (pinfunction "IO,_DIFFIO_R43p,_(DQ3R)/(DQ3R)/(DQ1R)_U21") (pintype "bidirectional"))
    )
    (net (code "190") (name "SDRAM_DQ5") (class "Default")
      (node (ref "U14") (pin "10") (pinfunction "DQ5_10") (pintype "unspecified"))
      (node (ref "U25") (pin "U22") (pinfunction "IO,_DIFFIO_R43n,_(DQ3R)/(DQ3R)/(DQ1R)_U22") (pintype "bidirectional"))
    )
    (net (code "191") (name "SDRAM_DQ6") (class "Default")
      (node (ref "U14") (pin "11") (pinfunction "DQ6_11") (pintype "unspecified"))
      (node (ref "U25") (pin "R21") (pinfunction "IO,_DIFFIO_R39p,_(DQ1R)/(DQ3R)/(DQ1R)_R21") (pintype "bidirectional"))
    )
    (net (code "192") (name "SDRAM_DQ7") (class "Default")
      (node (ref "U14") (pin "13") (pinfunction "DQ7_13") (pintype "unspecified"))
      (node (ref "U25") (pin "R22") (pinfunction "IO,_DIFFIO_R39n,_(DQ1R)/(DQ3R)/(DQ1R)_R22") (pintype "bidirectional"))
    )
    (net (code "193") (name "SDRAM_DQ8") (class "Default")
      (node (ref "U14") (pin "42") (pinfunction "DQ8_42") (pintype "unspecified"))
      (node (ref "U25") (pin "P21") (pinfunction "IO,_DIFFIO_R38p,_(DQ1R)/(DQ3R)/(DQ1R)_P21") (pintype "bidirectional"))
    )
    (net (code "194") (name "SDRAM_DQ9") (class "Default")
      (node (ref "U14") (pin "44") (pinfunction "DQ9_44") (pintype "unspecified"))
      (node (ref "U25") (pin "P22") (pinfunction "IO,_DIFFIO_R38n,_(DQ1R)/(DQ3R)/(DQ1R)_P22") (pintype "bidirectional"))
    )
    (net (code "195") (name "SDRAM_DQ10") (class "Default")
      (node (ref "U14") (pin "45") (pinfunction "DQ10_45") (pintype "unspecified"))
      (node (ref "U25") (pin "N21") (pinfunction "IO,_DIFFIO_R32p,_(DEV_CLRn)_N21") (pintype "bidirectional"))
    )
    (net (code "196") (name "SDRAM_DQ11") (class "Default")
      (node (ref "U14") (pin "47") (pinfunction "DQ11_47") (pintype "unspecified"))
      (node (ref "U25") (pin "N22") (pinfunction "IO,_DIFFIO_R32n,_(DEV_OE)_N22") (pintype "bidirectional"))
    )
    (net (code "197") (name "SDRAM_DQ12") (class "Default")
      (node (ref "U14") (pin "48") (pinfunction "DQ12_48") (pintype "unspecified"))
      (node (ref "U25") (pin "M21") (pinfunction "IO,_DIFFIO_R31p,_(DQ1R)/(DQ3R)/(DQ1R)_M21") (pintype "bidirectional"))
    )
    (net (code "198") (name "SDRAM_DQ13") (class "Default")
      (node (ref "U14") (pin "50") (pinfunction "DQ13_50") (pintype "unspecified"))
      (node (ref "U25") (pin "M22") (pinfunction "IO,_DIFFIO_R31n,_(DQ1R)/(DQ3R)/(DQ1R)_M22") (pintype "bidirectional"))
    )
    (net (code "199") (name "SDRAM_DQ14") (class "Default")
      (node (ref "U14") (pin "51") (pinfunction "DQ14_51") (pintype "unspecified"))
      (node (ref "U25") (pin "L21") (pinfunction "IO,_DIFFIO_R27p,_(CRC_ERROR)_L21") (pintype "bidirectional"))
    )
    (net (code "200") (name "SDRAM_DQ15") (class "Default")
      (node (ref "U14") (pin "53") (pinfunction "DQ15_53") (pintype "unspecified"))
      (node (ref "U25") (pin "L22") (pinfunction "IO,_DIFFIO_R27n,_(INIT_DONE)_L22") (pintype "bidirectional"))
    )
    (net (code "201") (name "SDRAM_DQ16") (class "Default")
      (node (ref "U15") (pin "2") (pinfunction "DQ0_2") (pintype "unspecified"))
      (node (ref "U25") (pin "K21") (pinfunction "IO,_DIFFIO_R24p,_(CLKUSR)_K21") (pintype "bidirectional"))
    )
    (net (code "202") (name "SDRAM_DQ17") (class "Default")
      (node (ref "U15") (pin "4") (pinfunction "DQ1_4") (pintype "unspecified"))
      (node (ref "U25") (pin "K18") (pinfunction "IO,_DIFFIO_R20p,_(DQ0R)/(DQ1R)/(DQ1R)_K18") (pintype "bidirectional"))
    )
    (net (code "203") (name "SDRAM_DQ18") (class "Default")
      (node (ref "U15") (pin "5") (pinfunction "DQ2_5") (pintype "unspecified"))
      (node (ref "U25") (pin "J22") (pinfunction "IO,_DIFFIO_R23n,_(DQS0R/CQ1R,DPCLK7)/(DQS0R/CQ1R,DPCLK7)/(DQS0R/CQ1R,DPCLK7)_J22") (pintype "bidirectional"))
    )
    (net (code "204") (name "SDRAM_DQ19") (class "Default")
      (node (ref "U15") (pin "7") (pinfunction "DQ3_7") (pintype "unspecified"))
      (node (ref "U25") (pin "J21") (pinfunction "IO,_DIFFIO_R23p,_(DM0R)/(DM1R/BWS#1R)/(DM1R/BWS#1R)_J21") (pintype "bidirectional"))
    )
    (net (code "205") (name "SDRAM_DQ20") (class "Default")
      (node (ref "U15") (pin "8") (pinfunction "DQ4_8") (pintype "unspecified"))
      (node (ref "U25") (pin "H22") (pinfunction "IO,_DIFFIO_R22n,_(DQ0R)/(DQ1R)/(DQ1R)_H22") (pintype "bidirectional"))
    )
    (net (code "206") (name "SDRAM_DQ21") (class "Default")
      (node (ref "U15") (pin "10") (pinfunction "DQ5_10") (pintype "unspecified"))
      (node (ref "U25") (pin "H21") (pinfunction "IO,_DIFFIO_R22p,_(DQ0R)/(DQ1R)/(DQ1R)_H21") (pintype "bidirectional"))
    )
    (net (code "207") (name "SDRAM_DQ22") (class "Default")
      (node (ref "U15") (pin "11") (pinfunction "DQ6_11") (pintype "unspecified"))
      (node (ref "U25") (pin "F22") (pinfunction "IO,_DIFFIO_R18n,_(DQ0R)/(DQ1R)/(DQ1R)_F22") (pintype "bidirectional"))
    )
    (net (code "208") (name "SDRAM_DQ23") (class "Default")
      (node (ref "U15") (pin "13") (pinfunction "DQ7_13") (pintype "unspecified"))
      (node (ref "U25") (pin "F21") (pinfunction "IO,_DIFFIO_R18p,_(DQ0R)/(DQ1R)/(DQ1R)_F21") (pintype "bidirectional"))
    )
    (net (code "209") (name "SDRAM_DQ24") (class "Default")
      (node (ref "U15") (pin "42") (pinfunction "DQ8_42") (pintype "unspecified"))
      (node (ref "U25") (pin "E22") (pinfunction "IO,_DIFFIO_R12n,_(nWE),_(DQ0R)/(DQ1R)/(DQ1R)_E22") (pintype "bidirectional"))
    )
    (net (code "210") (name "SDRAM_DQ25") (class "Default")
      (node (ref "U15") (pin "44") (pinfunction "DQ9_44") (pintype "unspecified"))
      (node (ref "U25") (pin "E21") (pinfunction "IO,_DIFFIO_R12p,_(nOE),_(_)/(DQ1R)/(DQ1R)_E21") (pintype "bidirectional"))
    )
    (net (code "211") (name "SDRAM_DQ26") (class "Default")
      (node (ref "U15") (pin "45") (pinfunction "DQ10_45") (pintype "unspecified"))
      (node (ref "U25") (pin "D22") (pinfunction "IO,_DIFFIO_R9n,_(DM2R)/(DM1R/BWS#1R)/(DM1R/BWS#1R)_D22") (pintype "bidirectional"))
    )
    (net (code "212") (name "SDRAM_DQ27") (class "Default")
      (node (ref "U15") (pin "47") (pinfunction "DQ11_47") (pintype "unspecified"))
      (node (ref "U25") (pin "D21") (pinfunction "IO,_DIFFIO_R9p,_(_)/(DQ1R)/(DQ1R)_D21") (pintype "bidirectional"))
    )
    (net (code "213") (name "SDRAM_DQ28") (class "Default")
      (node (ref "U15") (pin "48") (pinfunction "DQ12_48") (pintype "unspecified"))
      (node (ref "U25") (pin "C22") (pinfunction "IO,_DIFFIO_R6n,_(DQ2R)/(DQ1R)/(DQ1R)_C22") (pintype "bidirectional"))
    )
    (net (code "214") (name "SDRAM_DQ29") (class "Default")
      (node (ref "U15") (pin "50") (pinfunction "DQ13_50") (pintype "unspecified"))
      (node (ref "U25") (pin "C21") (pinfunction "IO,_DIFFIO_R6p,_(DQ2R)/(DQ1R)/(DQ1R)_C21") (pintype "bidirectional"))
    )
    (net (code "215") (name "SDRAM_DQ30") (class "Default")
      (node (ref "U15") (pin "51") (pinfunction "DQ14_51") (pintype "unspecified"))
      (node (ref "U25") (pin "B22") (pinfunction "IO,_DIFFIO_R5n,_(PADD22),_(DQ2R)/(DQ1R)/(DQ1R)_B22") (pintype "bidirectional"))
    )
    (net (code "216") (name "SDRAM_DQ31") (class "Default")
      (node (ref "U15") (pin "53") (pinfunction "DQ15_53") (pintype "unspecified"))
      (node (ref "U25") (pin "B21") (pinfunction "IO,_DIFFIO_R5p,_(PADD21),_(DQ2R)/(DQ1R)/(DQ1R)_B21") (pintype "bidirectional"))
    )
    (net (code "217") (name "SDRAM_DQM0") (class "Default")
      (node (ref "U14") (pin "15") (pinfunction "LDQM_15") (pintype "unspecified"))
      (node (ref "U25") (pin "AA20") (pinfunction "IO,_DIFFIO_B49p,_(_)/(DQ5B)/(DQ5B)_AA20") (pintype "bidirectional"))
    )
    (net (code "218") (name "SDRAM_DQM1") (class "Default")
      (node (ref "U14") (pin "39") (pinfunction "UDQM_39") (pintype "unspecified"))
      (node (ref "U25") (pin "M20") (pinfunction "IO,_DIFFIO_R30n,_(DQ1R)/(DQ3R)/(DQ1R)_M20") (pintype "bidirectional"))
    )
    (net (code "219") (name "SDRAM_DQM2") (class "Default")
      (node (ref "U15") (pin "15") (pinfunction "LDQM_15") (pintype "unspecified"))
      (node (ref "U25") (pin "M19") (pinfunction "IO,_DIFFIO_R30p,_(DQ1R)/(DQ3R)/(DQ1R)_M19") (pintype "bidirectional"))
    )
    (net (code "220") (name "SDRAM_DQM3") (class "Default")
      (node (ref "U15") (pin "39") (pinfunction "UDQM_39") (pintype "unspecified"))
      (node (ref "U25") (pin "B18") (pinfunction "IO,_DIFFIO_T45p,_(PADD0)_B18") (pintype "bidirectional"))
    )
    (net (code "221") (name "SDRAM_RAS") (class "Default")
      (node (ref "R96") (pin "2") (pinfunction "2_2") (pintype "input"))
      (node (ref "U14") (pin "18") (pinfunction "RAS#_18") (pintype "unspecified"))
      (node (ref "U15") (pin "18") (pinfunction "RAS#_18") (pintype "unspecified"))
      (node (ref "U25") (pin "Y22") (pinfunction "IO,_DIFFIO_R51n,_(DQ3R)/(DQ3R)/(DQ1R)_Y22") (pintype "bidirectional"))
    )
    (net (code "222") (name "SDRAM_WE") (class "Default")
      (node (ref "R97") (pin "2") (pinfunction "2_2") (pintype "input"))
      (node (ref "U14") (pin "16") (pinfunction "WE#_16") (pintype "unspecified"))
      (node (ref "U15") (pin "16") (pinfunction "WE#_16") (pintype "unspecified"))
      (node (ref "U25") (pin "AA21") (pinfunction "IO,_DIFFIO_R56p,_(DM3R/BWS#3R)/(DM3R/BWS#3R)/(DM1R/BWS#1R)_AA21") (pintype "bidirectional"))
    )
    (net (code "223") (name "SD_CLK") (class "Default")
      (node (ref "CARD1") (pin "5") (pinfunction "CLX_5") (pintype "unspecified"))
      (node (ref "U25") (pin "H1") (pinfunction "IO,_DIFFIO_L23n,_(DQ0L)/(DQ1L)/(DQ1L)_H1") (pintype "bidirectional"))
    )
    (net (code "224") (name "SD_CMD_MOSI") (class "Default")
      (node (ref "CARD1") (pin "3") (pinfunction "CMD_3") (pintype "unspecified"))
      (node (ref "R122") (pin "1") (pinfunction "1_1") (pintype "unspecified"))
      (node (ref "U25") (pin "H2") (pinfunction "IO,_DIFFIO_L23p,_(DQ0L)/(DQ1L)/(DQ1L)_H2") (pintype "bidirectional"))
    )
    (net (code "225") (name "SD_DATA0_MISO") (class "Default")
      (node (ref "CARD1") (pin "7") (pinfunction "DAT0_7") (pintype "unspecified"))
      (node (ref "R121") (pin "1") (pinfunction "1_1") (pintype "unspecified"))
      (node (ref "U25") (pin "J2") (pinfunction "IO,_DIFFIO_L24p,_(DQ0L)/(DQ1L)/(DQ1L)_J2") (pintype "bidirectional"))
    )
    (net (code "226") (name "SD_DATA1_IRQ") (class "Default")
      (node (ref "CARD1") (pin "8") (pinfunction "DAT1_8") (pintype "unspecified"))
      (node (ref "R120") (pin "1") (pinfunction "1_1") (pintype "unspecified"))
      (node (ref "U25") (pin "J1") (pinfunction "IO,_DIFFIO_L24n,_(DQ0L)/(DQ1L)/(DQ1L)_J1") (pintype "bidirectional"))
    )
    (net (code "227") (name "SD_DATA2_NC") (class "Default")
      (node (ref "CARD1") (pin "1") (pinfunction "DAT2_1") (pintype "unspecified"))
      (node (ref "R124") (pin "1") (pinfunction "1_1") (pintype "unspecified"))
      (node (ref "U25") (pin "G4") (pinfunction "IO,_DIFFIO_L1p_G4") (pintype "bidirectional"))
    )
    (net (code "228") (name "SD_DATA3_CS") (class "Default")
      (node (ref "CARD1") (pin "2") (pinfunction "CD/DAT3_2") (pintype "unspecified"))
      (node (ref "R123") (pin "1") (pinfunction "1_1") (pintype "unspecified"))
      (node (ref "U25") (pin "G3") (pinfunction "IO,_DIFFIO_L1n_G3") (pintype "bidirectional"))
    )
    (net (code "229") (name "SPIFLASH_1_CLK") (class "Default")
      (node (ref "U22") (pin "6") (pinfunction "CLK_6") (pintype "unspecified"))
      (node (ref "U25") (pin "V4") (pinfunction "IO,_RUP1_V4") (pintype "bidirectional"))
    )
    (net (code "230") (name "SPIFLASH_1_CS") (class "Default")
      (node (ref "U22") (pin "1") (pinfunction "CS#_1") (pintype "unspecified"))
      (node (ref "U25") (pin "V3") (pinfunction "IO,_RDN1_V3") (pintype "bidirectional"))
    )
    (net (code "231") (name "SPIFLASH_1_HOLD") (class "Default")
      (node (ref "U22") (pin "7") (pinfunction "HOLD#orRESET#(IO3)_7") (pintype "unspecified"))
      (node (ref "U25") (pin "V2") (pinfunction "IO,_DIFFIO_L38p,_(DQ3L)/(DQ3L)/(DQ1L)_V2") (pintype "bidirectional"))
    )
    (net (code "232") (name "SPIFLASH_1_MISO") (class "Default")
      (node (ref "U22") (pin "2") (pinfunction "DO(IO1)_2") (pintype "unspecified"))
      (node (ref "U25") (pin "V1") (pinfunction "IO,_DIFFIO_L38n,_(DQ3L)/(DQ3L)/(DQ1L)_V1") (pintype "bidirectional"))
    )
    (net (code "233") (name "SPIFLASH_1_MOSI") (class "Default")
      (node (ref "U22") (pin "5") (pinfunction "DI(IO0)_5") (pintype "unspecified"))
      (node (ref "U25") (pin "N6") (pinfunction "IO,_DIFFIO_L41p,_(DQ3L)/(DQ3L)/(DQ1L)_N6") (pintype "bidirectional"))
    )
    (net (code "234") (name "SPIFLASH_1_WP") (class "Default")
      (node (ref "U22") (pin "3") (pinfunction "WP#(IO2)_3") (pintype "unspecified"))
      (node (ref "U25") (pin "W1") (pinfunction "IO,_DIFFIO_L44n,_(DQ3L)/(DQ3L)/(DQ1L)_W1") (pintype "bidirectional"))
    )
    (net (code "235") (name "SPIFLASH_2_CLK") (class "Default")
      (node (ref "U24") (pin "6") (pinfunction "CLK_6") (pintype "unspecified"))
      (node (ref "U25") (pin "Y3") (pinfunction "IO,_DIFFIO_B4p,_(DQ3B)/(DQ3B)/(DQ5B)_Y3") (pintype "bidirectional"))
    )
    (net (code "236") (name "SPIFLASH_2_CS") (class "Default")
      (node (ref "U24") (pin "1") (pinfunction "CS#_1") (pintype "unspecified"))
      (node (ref "U25") (pin "Y2") (pinfunction "IO,_DIFFIO_L45p,_(DQ3L)/(DQ3L)/(DQ1L)_Y2") (pintype "bidirectional"))
    )
    (net (code "237") (name "SPIFLASH_2_HOLD") (class "Default")
      (node (ref "U24") (pin "7") (pinfunction "HOLD#orRESET#(IO3)_7") (pintype "unspecified"))
      (node (ref "U25") (pin "Y1") (pinfunction "IO,_DIFFIO_L45n,_(DQ3L)/(DQ3L)/(DQ1L)_Y1") (pintype "bidirectional"))
    )
    (net (code "238") (name "SPIFLASH_2_MISO") (class "Default")
      (node (ref "U24") (pin "2") (pinfunction "DO(IO1)_2") (pintype "unspecified"))
      (node (ref "U25") (pin "AA1") (pinfunction "IO,_DIFFIO_L50n,_(DQ3L)/(DQ3L)/(DQ1L)_AA1") (pintype "bidirectional"))
    )
    (net (code "239") (name "SPIFLASH_2_MOSI") (class "Default")
      (node (ref "U24") (pin "5") (pinfunction "DI(IO0)_5") (pintype "unspecified"))
      (node (ref "U25") (pin "AA3") (pinfunction "IO,_PLL1_CLKOUTp_AA3") (pintype "bidirectional"))
    )
    (net (code "240") (name "SPIFLASH_2_WP") (class "Default")
      (node (ref "U24") (pin "3") (pinfunction "WP#(IO2)_3") (pintype "unspecified"))
      (node (ref "U25") (pin "AB3") (pinfunction "IO,_PLL1_CLKOUTn_AB3") (pintype "bidirectional"))
    )
    (net (code "241") (name "SRAM_A0") (class "Default")
      (node (ref "U16") (pin "1") (pinfunction "A0_1") (pintype "input"))
      (node (ref "U25") (pin "E12") (pinfunction "IO,_DIFFIO_T28p,_(_)/(DQ5T)/(DQ5T)_E12") (pintype "bidirectional"))
    )
    (net (code "242") (name "SRAM_A1") (class "Default")
      (node (ref "U16") (pin "2") (pinfunction "A1_2") (pintype "input"))
      (node (ref "U25") (pin "E11") (pinfunction "IO,_DIFFIO_T27n,_(PADD13)_E11") (pintype "bidirectional"))
    )
    (net (code "243") (name "SRAM_A2") (class "Default")
      (node (ref "U16") (pin "3") (pinfunction "A2_3") (pintype "input"))
      (node (ref "U25") (pin "E10") (pinfunction "IO,_DIFFIO_T26p_E10") (pintype "bidirectional"))
    )
    (net (code "244") (name "SRAM_A3") (class "Default")
      (node (ref "U16") (pin "4") (pinfunction "A3_4") (pintype "input"))
      (node (ref "U25") (pin "D10") (pinfunction "IO,_DIFFIO_T26n,_(DQ5T)/(DQ3T)/(DQ5T)_D10") (pintype "bidirectional"))
    )
    (net (code "245") (name "SRAM_A4") (class "Default")
      (node (ref "U16") (pin "13") (pinfunction "A4_13") (pintype "input"))
      (node (ref "U25") (pin "B8") (pinfunction "IO,_DIFFIO_T20p,_(DATA3),_(DQ5T)/(DQ3T)/(DQ5T)_B8") (pintype "bidirectional"))
    )
    (net (code "246") (name "SRAM_A5") (class "Default")
      (node (ref "U16") (pin "14") (pinfunction "A5_14") (pintype "input"))
      (node (ref "U25") (pin "C7") (pinfunction "IO,_DIFFIO_T16p,_(DATA13),_(DM5T/BWS#5T)/(DM3T/BWS#3T)/(DM5T/BWS#5T)_C7") (pintype "bidirectional"))
    )
    (net (code "247") (name "SRAM_A6") (class "Default")
      (node (ref "U16") (pin "15") (pinfunction "A6_15") (pintype "input"))
      (node (ref "U25") (pin "A7") (pinfunction "IO,_DIFFIO_T19n,_(PADD18),_(DQ5T)/(DQ3T)/(DQ5T)_A7") (pintype "bidirectional"))
    )
    (net (code "248") (name "SRAM_A7") (class "Default")
      (node (ref "U16") (pin "16") (pinfunction "A7_16") (pintype "input"))
      (node (ref "U25") (pin "B7") (pinfunction "IO,_DIFFIO_T19p,_(DATA4),_(DQ5T)/(DQ3T)/(DQ5T)_B7") (pintype "bidirectional"))
    )
    (net (code "249") (name "SRAM_A8") (class "Default")
      (node (ref "U16") (pin "17") (pinfunction "A8_17") (pintype "input"))
      (node (ref "U25") (pin "A18") (pinfunction "IO,_DIFFIO_T45n,_(DQ2T)/(DQ5T)/(DQ5T)_A18") (pintype "bidirectional"))
    )
    (net (code "250") (name "SRAM_A9") (class "Default")
      (node (ref "U16") (pin "18") (pinfunction "A9_18") (pintype "input"))
      (node (ref "U25") (pin "C17") (pinfunction "IO,_DIFFIO_T46p,_(DQ2T)/(DQ5T)/(DQ5T)_C17") (pintype "bidirectional"))
    )
    (net (code "251") (name "SRAM_A10") (class "Default")
      (node (ref "U16") (pin "19") (pinfunction "A10_19") (pintype "input"))
      (node (ref "U25") (pin "B17") (pinfunction "IO,_DIFFIO_T41p,_(PADD2),_(_)/(DQ5T)/(DQ5T)_B17") (pintype "bidirectional"))
    )
    (net (code "252") (name "SRAM_A11") (class "Default")
      (node (ref "U16") (pin "20") (pinfunction "A11_20") (pintype "input"))
      (node (ref "U25") (pin "A17") (pinfunction "IO,_DIFFIO_T41n,_(PADD1),_(DQ2T)/(DQ5T)/(DQ5T)_A17") (pintype "bidirectional"))
    )
    (net (code "253") (name "SRAM_A12") (class "Default")
      (node (ref "U16") (pin "21") (pinfunction "A12_21") (pintype "input"))
      (node (ref "U25") (pin "B16") (pinfunction "IO,_DIFFIO_T40p,_(DQ4T)/(DQ5T)/(DQ5T)_B16") (pintype "bidirectional"))
    )
    (net (code "254") (name "SRAM_A13") (class "Default")
      (node (ref "U16") (pin "29") (pinfunction "A13_29") (pintype "input"))
      (node (ref "U25") (pin "D13") (pinfunction "IO,_DIFFIO_T35p,_(PADD8),_(DQ4T)/(DQ5T)/(DQ5T)_D13") (pintype "bidirectional"))
    )
    (net (code "255") (name "SRAM_A14") (class "Default")
      (node (ref "U16") (pin "30") (pinfunction "A14_30") (pintype "input"))
      (node (ref "U25") (pin "C13") (pinfunction "IO,_DIFFIO_T35n,_(PADD7)_C13") (pintype "bidirectional"))
    )
    (net (code "256") (name "SRAM_A15") (class "Default")
      (node (ref "U16") (pin "31") (pinfunction "A15_31") (pintype "input"))
      (node (ref "U25") (pin "B13") (pinfunction "IO,_DIFFIO_T29p,_(PADD12),_(DQS4T/CQ5T,DPCLK9)/(DQS4T/CQ5T,DPCLK9)/(DQS4T/CQ5T,DPCLK9)_B13") (pintype "bidirectional"))
    )
    (net (code "257") (name "SRAM_A16") (class "Default")
      (node (ref "U16") (pin "32") (pinfunction "A16_32") (pintype "input"))
      (node (ref "U25") (pin "A13") (pinfunction "IO,_DIFFIO_T29n,_(PADD11),_(DQ4T)/(DQ5T)/(DQ5T)_A13") (pintype "bidirectional"))
    )
    (net (code "258") (name "SRAM_CE") (class "Default")
      (node (ref "U16") (pin "5") (pinfunction "CE#_5") (pintype "input"))
      (node (ref "U25") (pin "A10") (pinfunction "IO,_DIFFIO_T25n,_(DQ5T)/(DQ3T)/(DQ5T)_A10") (pintype "bidirectional"))
    )
    (net (code "259") (name "SRAM_DQ0") (class "Default")
      (node (ref "U16") (pin "6") (pinfunction "I/O0_6") (pintype "input"))
      (node (ref "U25") (pin "B10") (pinfunction "IO,_DIFFIO_T25p,_(PADD15)_B10") (pintype "bidirectional"))
    )
    (net (code "260") (name "SRAM_DQ1") (class "Default")
      (node (ref "U16") (pin "7") (pinfunction "I/O1_7") (pintype "input"))
      (node (ref "U25") (pin "A9") (pinfunction "IO,_DIFFIO_T24n,_(PADD16),_(DQ5T)/(DQ3T)/(DQ5T)_A9") (pintype "bidirectional"))
    )
    (net (code "261") (name "SRAM_DQ2") (class "Default")
      (node (ref "U16") (pin "10") (pinfunction "I/O2_10") (pintype "input"))
      (node (ref "U25") (pin "B9") (pinfunction "IO,_DIFFIO_T24p,_(PADD17),_(DQS5T/CQ5T#,DPCLK10)/(DQS5T/CQ5T#,DPCLK10)/(DQS5T/CQ5T#,DPCLK10)_B9") (pintype "bidirectional"))
    )
    (net (code "262") (name "SRAM_DQ3") (class "Default")
      (node (ref "U16") (pin "11") (pinfunction "I/O3_11") (pintype "input"))
      (node (ref "U25") (pin "C8") (pinfunction "IO,_DIFFIO_T16n,_(DATA14),_(DQS3T/CQ3T#,DPCLK11)/(DQS3T/CQ3T#,DPCLK11)/(DQS3T/CQ3T#,DPCLK11)_C8") (pintype "bidirectional"))
    )
    (net (code "263") (name "SRAM_DQ4") (class "Default")
      (node (ref "U16") (pin "22") (pinfunction "I/O4_22") (pintype "input"))
      (node (ref "U25") (pin "A16") (pinfunction "IO,_DIFFIO_T40n,_(DM2T)/(DM5T/BWS#5T)/(DM5T/BWS#5T)_A16") (pintype "bidirectional"))
    )
    (net (code "264") (name "SRAM_DQ5") (class "Default")
      (node (ref "U16") (pin "23") (pinfunction "I/O5_23") (pintype "input"))
      (node (ref "U25") (pin "B15") (pinfunction "IO,_DIFFIO_T36p,_(PADD6),_(DQ4T)/(DQ5T)/(DQ5T)_B15") (pintype "bidirectional"))
    )
    (net (code "265") (name "SRAM_DQ6") (class "Default")
      (node (ref "U16") (pin "26") (pinfunction "I/O6_26") (pintype "input"))
      (node (ref "U25") (pin "A15") (pinfunction "IO,_DIFFIO_T36n,_(PADD5),_(DQ4T)/(DQ5T)/(DQ5T)_A15") (pintype "bidirectional"))
    )
    (net (code "266") (name "SRAM_DQ7") (class "Default")
      (node (ref "U16") (pin "27") (pinfunction "I/O7_27") (pintype "input"))
      (node (ref "U25") (pin "B14") (pinfunction "IO,_DIFFIO_T31p,_(PADD10),_(DQ4T)/(DQ5T)/(DQ5T)_B14") (pintype "bidirectional"))
    )
    (net (code "267") (name "SRAM_OE") (class "Default")
      (node (ref "U16") (pin "28") (pinfunction "OE#_28") (pintype "input"))
      (node (ref "U25") (pin "A14") (pinfunction "IO,_DIFFIO_T31n,_(PADD9),_(DQ4T)/(DQ5T)/(DQ5T)_A14") (pintype "bidirectional"))
    )
    (net (code "268") (name "SRAM_WE") (class "Default")
      (node (ref "U16") (pin "12") (pinfunction "WE#_12") (pintype "input"))
      (node (ref "U25") (pin "A8") (pinfunction "IO,_DIFFIO_T20n,_(DATA2),_(DQ5T)/(DQ3T)/(DQ5T)_A8") (pintype "bidirectional"))
    )
    (net (code "269") (name "UART_DTR") (class "Default")
      (node (ref "U23") (pin "13") (pinfunction "DTR#_13") (pintype "unspecified"))
      (node (ref "U25") (pin "B6") (pinfunction "IO,_DIFFIO_T18p,_(DATA15),_(DQ5T)/(DQ3T)/(DQ5T)_B6") (pintype "bidirectional"))
    )
    (net (code "270") (name "UART_RTS") (class "Default")
      (node (ref "U23") (pin "14") (pinfunction "RTS#_14") (pintype "unspecified"))
      (node (ref "U25") (pin "A6") (pinfunction "IO,_DIFFIO_T18n,_(PADD19),_(DQ5T)/(DQ3T)/(DQ5T)_A6") (pintype "bidirectional"))
    )
    (net (code "271") (name "UART_RX") (class "Default")
      (node (ref "LED13") (pin "2") (pinfunction "A_2") (pintype "unspecified"))
      (node (ref "R102") (pin "2") (pinfunction "2_2") (pintype "unspecified"))
      (node (ref "U23") (pin "3") (pinfunction "RXD_3") (pintype "unspecified"))
      (node (ref "U25") (pin "C6") (pinfunction "IO,_DIFFIO_T7n,_(DATA7),_(DQ3T)/(DQ3T)/(DQ5T)_C6") (pintype "bidirectional"))
    )
    (net (code "272") (name "UART_TX") (class "Default")
      (node (ref "LED12") (pin "2") (pinfunction "A_2") (pintype "unspecified"))
      (node (ref "U23") (pin "2") (pinfunction "TXD_2") (pintype "unspecified"))
      (node (ref "U25") (pin "A5") (pinfunction "IO,_DIFFIO_T11p,_(DATA5),_(DQ3T)/(DQ3T)/(DQ5T)_A5") (pintype "bidirectional"))
    )
    (net (code "273") (name "VUSB") (class "Default")
      (node (ref "U11") (pin "3") (pinfunction "3_3") (pintype "unspecified"))
      (node (ref "U9") (pin "3") (pinfunction "3_3") (pintype "unspecified"))
      (node (ref "USB2") (pin "11") (pinfunction "VBUS_11") (pintype "unspecified"))
      (node (ref "USB2") (pin "2") (pinfunction "VBUS_2") (pintype "unspecified"))
    )
    (net (code "274") (name "unconnected-(CARD1-PadCD)") (class "Default")
      (node (ref "CARD1") (pin "CD") (pinfunction "CD_CD") (pintype "unspecified"))
    )
    (net (code "275") (name "unconnected-(HDMI1-CEC-Pad13)") (class "Default")
      (node (ref "HDMI1") (pin "13") (pinfunction "CEC_13") (pintype "unspecified+no_connect"))
    )
    (net (code "276") (name "unconnected-(HDMI1-HotPlugDetect-Pad19)") (class "Default")
      (node (ref "HDMI1") (pin "19") (pinfunction "HotPlugDetect_19") (pintype "unspecified+no_connect"))
    )
    (net (code "277") (name "unconnected-(HDMI1-Reserved(N.C.)-Pad14)") (class "Default")
      (node (ref "HDMI1") (pin "14") (pinfunction "Reserved(N.C.)_14") (pintype "unspecified+no_connect"))
    )
    (net (code "278") (name "unconnected-(HDMI1-SCL-Pad15)") (class "Default")
      (node (ref "HDMI1") (pin "15") (pinfunction "SCL_15") (pintype "unspecified+no_connect"))
    )
    (net (code "279") (name "unconnected-(HDMI1-SDA-Pad16)") (class "Default")
      (node (ref "HDMI1") (pin "16") (pinfunction "SDA_16") (pintype "unspecified+no_connect"))
    )
    (net (code "280") (name "unconnected-(J1-NC-Pad7)") (class "Default")
      (node (ref "J1") (pin "7") (pinfunction "NC_7") (pintype "unspecified+no_connect"))
    )
    (net (code "281") (name "unconnected-(J1-Pad5)") (class "Default")
      (node (ref "J1") (pin "5") (pinfunction "5_5") (pintype "unspecified+no_connect"))
    )
    (net (code "282") (name "unconnected-(P1-Pad6)") (class "Default")
      (node (ref "P1") (pin "6") (pinfunction "6_6") (pintype "input+no_connect"))
    )
    (net (code "283") (name "unconnected-(P1-Pad7)") (class "Default")
      (node (ref "P1") (pin "7") (pinfunction "7_7") (pintype "input+no_connect"))
    )
    (net (code "284") (name "unconnected-(P1-Pad8)") (class "Default")
      (node (ref "P1") (pin "8") (pinfunction "8_8") (pintype "input+no_connect"))
    )
    (net (code "285") (name "unconnected-(U9-Pad1)") (class "Default")
      (node (ref "U9") (pin "1") (pinfunction "1_1") (pintype "unspecified+no_connect"))
    )
    (net (code "286") (name "unconnected-(U10-Pad1)") (class "Default")
      (node (ref "U10") (pin "1") (pinfunction "1_1") (pintype "unspecified+no_connect"))
    )
    (net (code "287") (name "unconnected-(U14-NC-Pad40)") (class "Default")
      (node (ref "U14") (pin "40") (pinfunction "NC_40") (pintype "unspecified+no_connect"))
    )
    (net (code "288") (name "unconnected-(U15-NC-Pad40)") (class "Default")
      (node (ref "U15") (pin "40") (pinfunction "NC_40") (pintype "unspecified+no_connect"))
    )
    (net (code "289") (name "unconnected-(U18-RXD-Pad5)") (class "Default")
      (node (ref "U18") (pin "5") (pinfunction "RXD_5") (pintype "unspecified+no_connect"))
    )
    (net (code "290") (name "unconnected-(U18-SD_CK-Pad19)") (class "Default")
      (node (ref "U18") (pin "19") (pinfunction "SD_CK_19") (pintype "unspecified+no_connect"))
    )
    (net (code "291") (name "unconnected-(U18-SD_CS-Pad17)") (class "Default")
      (node (ref "U18") (pin "17") (pinfunction "SD_CS_17") (pintype "unspecified+no_connect"))
    )
    (net (code "292") (name "unconnected-(U18-SD_DI-Pad6)") (class "Default")
      (node (ref "U18") (pin "6") (pinfunction "SD_DI_6") (pintype "unspecified+no_connect"))
    )
    (net (code "293") (name "unconnected-(U18-SD_DO-Pad18)") (class "Default")
      (node (ref "U18") (pin "18") (pinfunction "SD_DO_18") (pintype "unspecified+no_connect"))
    )
    (net (code "294") (name "unconnected-(U18-TXD-Pad4)") (class "Default")
      (node (ref "U18") (pin "4") (pinfunction "TXD_4") (pintype "unspecified+no_connect"))
    )
    (net (code "295") (name "unconnected-(U19-RXD-Pad5)") (class "Default")
      (node (ref "U19") (pin "5") (pinfunction "RXD_5") (pintype "unspecified+no_connect"))
    )
    (net (code "296") (name "unconnected-(U19-SD_CK-Pad19)") (class "Default")
      (node (ref "U19") (pin "19") (pinfunction "SD_CK_19") (pintype "unspecified+no_connect"))
    )
    (net (code "297") (name "unconnected-(U19-SD_CS-Pad17)") (class "Default")
      (node (ref "U19") (pin "17") (pinfunction "SD_CS_17") (pintype "unspecified+no_connect"))
    )
    (net (code "298") (name "unconnected-(U19-SD_DI-Pad6)") (class "Default")
      (node (ref "U19") (pin "6") (pinfunction "SD_DI_6") (pintype "unspecified+no_connect"))
    )
    (net (code "299") (name "unconnected-(U19-SD_DO-Pad18)") (class "Default")
      (node (ref "U19") (pin "18") (pinfunction "SD_DO_18") (pintype "unspecified+no_connect"))
    )
    (net (code "300") (name "unconnected-(U19-TXD-Pad4)") (class "Default")
      (node (ref "U19") (pin "4") (pinfunction "TXD_4") (pintype "unspecified+no_connect"))
    )
    (net (code "301") (name "unconnected-(U23-CTS#-Pad9)") (class "Default")
      (node (ref "U23") (pin "9") (pinfunction "CTS#_9") (pintype "unspecified+no_connect"))
    )
    (net (code "302") (name "unconnected-(U23-DCD#-Pad12)") (class "Default")
      (node (ref "U23") (pin "12") (pinfunction "DCD#_12") (pintype "unspecified+no_connect"))
    )
    (net (code "303") (name "unconnected-(U23-DSR#-Pad10)") (class "Default")
      (node (ref "U23") (pin "10") (pinfunction "DSR#_10") (pintype "unspecified+no_connect"))
    )
    (net (code "304") (name "unconnected-(U23-NC.-Pad7)") (class "Default")
      (node (ref "U23") (pin "7") (pinfunction "NC._7") (pintype "unspecified+no_connect"))
    )
    (net (code "305") (name "unconnected-(U23-OUT#-Pad8)") (class "Default")
      (node (ref "U23") (pin "8") (pinfunction "OUT#_8") (pintype "unspecified+no_connect"))
    )
    (net (code "306") (name "unconnected-(U23-R232-Pad15)") (class "Default")
      (node (ref "U23") (pin "15") (pinfunction "R232_15") (pintype "unspecified+no_connect"))
    )
    (net (code "307") (name "unconnected-(U23-RI#-Pad11)") (class "Default")
      (node (ref "U23") (pin "11") (pinfunction "RI#_11") (pintype "unspecified+no_connect"))
    )
    (net (code "308") (name "unconnected-(U25A-IO,_DIFFIO_L8p,_(DQ2L){slash}(DQ1L){slash}(DQ1L)-PadD2)") (class "Default")
      (node (ref "U25") (pin "D2") (pinfunction "IO,_DIFFIO_L8p,_(DQ2L)/(DQ1L)/(DQ1L)_D2") (pintype "bidirectional"))
    )
    (net (code "309") (name "unconnected-(U25A-IO,_DIFFIO_L9n,_(DQ2L){slash}(DQ1L){slash}(DQ1L)-PadJ6)") (class "Default")
      (node (ref "U25") (pin "J6") (pinfunction "IO,_DIFFIO_L9n,_(DQ2L)/(DQ1L)/(DQ1L)_J6") (pintype "bidirectional"))
    )
    (net (code "310") (name "unconnected-(U25A-IO,_DIFFIO_L9p,_(DQ2L){slash}(DQ1L){slash}(DQ1L)-PadH6)") (class "Default")
      (node (ref "U25") (pin "H6") (pinfunction "IO,_DIFFIO_L9p,_(DQ2L)/(DQ1L)/(DQ1L)_H6") (pintype "bidirectional"))
    )
    (net (code "311") (name "unconnected-(U25A-IO,_DIFFIO_L10n,_(_){slash}(DQ1L){slash}(DQ1L)-PadE1)") (class "Default")
      (node (ref "U25") (pin "E1") (pinfunction "IO,_DIFFIO_L10n,_(_)/(DQ1L)/(DQ1L)_E1") (pintype "bidirectional"))
    )
    (net (code "312") (name "unconnected-(U25A-IO,_DIFFIO_L14n-PadJ8)") (class "Default")
      (node (ref "U25") (pin "J8") (pinfunction "IO,_DIFFIO_L14n_J8") (pintype "bidirectional"))
    )
    (net (code "313") (name "unconnected-(U25A-IO,_DIFFIO_L14p-PadH8)") (class "Default")
      (node (ref "U25") (pin "H8") (pinfunction "IO,_DIFFIO_L14p_H8") (pintype "bidirectional"))
    )
    (net (code "314") (name "unconnected-(U25A-IO,_DIFFIO_L18n-PadJ5)") (class "Default")
      (node (ref "U25") (pin "J5") (pinfunction "IO,_DIFFIO_L18n_J5") (pintype "bidirectional"))
    )
    (net (code "315") (name "unconnected-(U25A-IO,_DIFFIO_L20n-PadK8)") (class "Default")
      (node (ref "U25") (pin "K8") (pinfunction "IO,_DIFFIO_L20n_K8") (pintype "bidirectional"))
    )
    (net (code "316") (name "unconnected-(U25A-IO,_DIFFIO_L20p-PadL8)") (class "Default")
      (node (ref "U25") (pin "L8") (pinfunction "IO,_DIFFIO_L20p_L8") (pintype "bidirectional"))
    )
    (net (code "317") (name "unconnected-(U25A-IO,_DIFFIO_L21n-PadK7)") (class "Default")
      (node (ref "U25") (pin "K7") (pinfunction "IO,_DIFFIO_L21n_K7") (pintype "bidirectional"))
    )
    (net (code "318") (name "unconnected-(U25A-IO,_DIFFIO_L21p-PadJ7)") (class "Default")
      (node (ref "U25") (pin "J7") (pinfunction "IO,_DIFFIO_L21p_J7") (pintype "bidirectional"))
    )
    (net (code "319") (name "unconnected-(U25A-IO,_VREFB1N0-PadG5)") (class "Default")
      (node (ref "U25") (pin "G5") (pinfunction "IO,_VREFB1N0_G5") (pintype "bidirectional"))
    )
    (net (code "320") (name "unconnected-(U25A-IO,_VREFB1N1-PadH7)") (class "Default")
      (node (ref "U25") (pin "H7") (pinfunction "IO,_VREFB1N1_H7") (pintype "bidirectional"))
    )
    (net (code "321") (name "unconnected-(U25A-IO,_VREFB1N2-PadH5)") (class "Default")
      (node (ref "U25") (pin "H5") (pinfunction "IO,_VREFB1N2_H5") (pintype "bidirectional"))
    )
    (net (code "322") (name "unconnected-(U25A-IO,_VREFB1N3-PadJ3)") (class "Default")
      (node (ref "U25") (pin "J3") (pinfunction "IO,_VREFB1N3_J3") (pintype "bidirectional"))
    )
    (net (code "323") (name "unconnected-(U25B-IO,_DIFFIO_L26n,_(DQ0L){slash}(DQ1L){slash}(DQ1L)-PadM6)") (class "Default")
      (node (ref "U25") (pin "M6") (pinfunction "IO,_DIFFIO_L26n,_(DQ0L)/(DQ1L)/(DQ1L)_M6") (pintype "bidirectional"))
    )
    (net (code "324") (name "unconnected-(U25B-IO,_DIFFIO_L26p,_(DQ0L){slash}(DQ1L){slash}(DQ1L)-PadL6)") (class "Default")
      (node (ref "U25") (pin "L6") (pinfunction "IO,_DIFFIO_L26p,_(DQ0L)/(DQ1L)/(DQ1L)_L6") (pintype "bidirectional"))
    )
    (net (code "325") (name "unconnected-(U25B-IO,_DIFFIO_L30n-PadL7)") (class "Default")
      (node (ref "U25") (pin "L7") (pinfunction "IO,_DIFFIO_L30n_L7") (pintype "bidirectional"))
    )
    (net (code "326") (name "unconnected-(U25B-IO,_DIFFIO_L41n-PadM7)") (class "Default")
      (node (ref "U25") (pin "M7") (pinfunction "IO,_DIFFIO_L41n_M7") (pintype "bidirectional"))
    )
    (net (code "327") (name "unconnected-(U25B-IO,_DIFFIO_L42n-PadN8)") (class "Default")
      (node (ref "U25") (pin "N8") (pinfunction "IO,_DIFFIO_L42n_N8") (pintype "bidirectional"))
    )
    (net (code "328") (name "unconnected-(U25B-IO,_DIFFIO_L42p-PadM8)") (class "Default")
      (node (ref "U25") (pin "M8") (pinfunction "IO,_DIFFIO_L42p_M8") (pintype "bidirectional"))
    )
    (net (code "329") (name "unconnected-(U25B-IO,_DIFFIO_L49n-PadP7)") (class "Default")
      (node (ref "U25") (pin "P7") (pinfunction "IO,_DIFFIO_L49n_P7") (pintype "bidirectional"))
    )
    (net (code "330") (name "unconnected-(U25B-IO,_DIFFIO_L49p-PadN7)") (class "Default")
      (node (ref "U25") (pin "N7") (pinfunction "IO,_DIFFIO_L49p_N7") (pintype "bidirectional"))
    )
    (net (code "331") (name "unconnected-(U25B-IO,_DIFFIO_L53n-PadT7)") (class "Default")
      (node (ref "U25") (pin "T7") (pinfunction "IO,_DIFFIO_L53n_T7") (pintype "bidirectional"))
    )
    (net (code "332") (name "unconnected-(U25B-IO,_DIFFIO_L53p-PadR7)") (class "Default")
      (node (ref "U25") (pin "R7") (pinfunction "IO,_DIFFIO_L53p_R7") (pintype "bidirectional"))
    )
    (net (code "333") (name "unconnected-(U25B-IO,_VREFB2N0-PadM5)") (class "Default")
      (node (ref "U25") (pin "M5") (pinfunction "IO,_VREFB2N0_M5") (pintype "bidirectional"))
    )
    (net (code "334") (name "unconnected-(U25B-IO,_VREFB2N1-PadP5)") (class "Default")
      (node (ref "U25") (pin "P5") (pinfunction "IO,_VREFB2N1_P5") (pintype "bidirectional"))
    )
    (net (code "335") (name "unconnected-(U25B-IO,_VREFB2N2-PadT3)") (class "Default")
      (node (ref "U25") (pin "T3") (pinfunction "IO,_VREFB2N2_T3") (pintype "bidirectional"))
    )
    (net (code "336") (name "unconnected-(U25B-IO,_VREFB2N3-PadR5)") (class "Default")
      (node (ref "U25") (pin "R5") (pinfunction "IO,_VREFB2N3_R5") (pintype "bidirectional"))
    )
    (net (code "337") (name "unconnected-(U25B-IO-PadR6)") (class "Default")
      (node (ref "U25") (pin "R6") (pinfunction "IO_R6") (pintype "bidirectional"))
    )
    (net (code "338") (name "unconnected-(U25C-IO,_(DQ3B){slash}(DQ3B){slash}(DQ5B)-PadW8)") (class "Default")
      (node (ref "U25") (pin "W8") (pinfunction "IO,_(DQ3B)/(DQ3B)/(DQ5B)_W8") (pintype "bidirectional"))
    )
    (net (code "339") (name "unconnected-(U25C-IO,_(DQ5B){slash}(DQ3B){slash}(DQ5B)-PadY8)") (class "Default")
      (node (ref "U25") (pin "Y8") (pinfunction "IO,_(DQ5B)/(DQ3B)/(DQ5B)_Y8") (pintype "bidirectional"))
    )
    (net (code "340") (name "unconnected-(U25C-IO,_DIFFIO_B1n,_(DM3B{slash}BWS#3B){slash}(DM3B{slash}BWS#3B){slash}(DM5B{slash}BWS#5B)-PadV5)") (class "Default")
      (node (ref "U25") (pin "V5") (pinfunction "IO,_DIFFIO_B1n,_(DM3B/BWS#3B)/(DM3B/BWS#3B)/(DM5B/BWS#5B)_V5") (pintype "bidirectional"))
    )
    (net (code "341") (name "unconnected-(U25C-IO,_DIFFIO_B1p-PadV6)") (class "Default")
      (node (ref "U25") (pin "V6") (pinfunction "IO,_DIFFIO_B1p_V6") (pintype "bidirectional"))
    )
    (net (code "342") (name "unconnected-(U25C-IO,_DIFFIO_B3n-PadU8)") (class "Default")
      (node (ref "U25") (pin "U8") (pinfunction "IO,_DIFFIO_B3n_U8") (pintype "bidirectional"))
    )
    (net (code "343") (name "unconnected-(U25C-IO,_DIFFIO_B3p-PadU7)") (class "Default")
      (node (ref "U25") (pin "U7") (pinfunction "IO,_DIFFIO_B3p_U7") (pintype "bidirectional"))
    )
    (net (code "344") (name "unconnected-(U25C-IO,_DIFFIO_B7n-PadV7)") (class "Default")
      (node (ref "U25") (pin "V7") (pinfunction "IO,_DIFFIO_B7n_V7") (pintype "bidirectional"))
    )
    (net (code "345") (name "unconnected-(U25C-IO,_DIFFIO_B11n-PadT9)") (class "Default")
      (node (ref "U25") (pin "T9") (pinfunction "IO,_DIFFIO_B11n_T9") (pintype "bidirectional"))
    )
    (net (code "346") (name "unconnected-(U25C-IO,_DIFFIO_B11p-PadT8)") (class "Default")
      (node (ref "U25") (pin "T8") (pinfunction "IO,_DIFFIO_B11p_T8") (pintype "bidirectional"))
    )
    (net (code "347") (name "unconnected-(U25C-IO,_DIFFIO_B13n,_(DQ3B){slash}(DQ3B){slash}(DQ5B)-PadV8)") (class "Default")
      (node (ref "U25") (pin "V8") (pinfunction "IO,_DIFFIO_B13n,_(DQ3B)/(DQ3B)/(DQ5B)_V8") (pintype "bidirectional"))
    )
    (net (code "348") (name "unconnected-(U25C-IO,_DIFFIO_B13p,_(DQ3B){slash}(DQ3B){slash}(DQ5B)-PadU9)") (class "Default")
      (node (ref "U25") (pin "U9") (pinfunction "IO,_DIFFIO_B13p,_(DQ3B)/(DQ3B)/(DQ5B)_U9") (pintype "bidirectional"))
    )
    (net (code "349") (name "unconnected-(U25C-IO,_DIFFIO_B14n,_(DQ5B){slash}(DQ3B){slash}(DQ5B)-PadAB7)") (class "Default")
      (node (ref "U25") (pin "AB7") (pinfunction "IO,_DIFFIO_B14n,_(DQ5B)/(DQ3B)/(DQ5B)_AB7") (pintype "bidirectional"))
    )
    (net (code "350") (name "unconnected-(U25C-IO,_DIFFIO_B15n-PadT11)") (class "Default")
      (node (ref "U25") (pin "T11") (pinfunction "IO,_DIFFIO_B15n_T11") (pintype "bidirectional"))
    )
    (net (code "351") (name "unconnected-(U25C-IO,_DIFFIO_B15p-PadT10)") (class "Default")
      (node (ref "U25") (pin "T10") (pinfunction "IO,_DIFFIO_B15p_T10") (pintype "bidirectional"))
    )
    (net (code "352") (name "unconnected-(U25C-IO,_DIFFIO_B16p,_(DQS3B{slash}CQ3B#,DPCLK2){slash}(DQS3B{slash}CQ3B#,DPCLK2){slash}(DQS3B{slash}CQ3B#,DPCLK2)-PadV10)") (class "Default")
      (node (ref "U25") (pin "V10") (pinfunction "IO,_DIFFIO_B16p,_(DQS3B/CQ3B#,DPCLK2)/(DQS3B/CQ3B#,DPCLK2)/(DQS3B/CQ3B#,DPCLK2)_V10") (pintype "bidirectional"))
    )
    (net (code "353") (name "unconnected-(U25C-IO,_DIFFIO_B17n,_(DQ5B){slash}(DQ3B){slash}(DQ5B)-PadU10)") (class "Default")
      (node (ref "U25") (pin "U10") (pinfunction "IO,_DIFFIO_B17n,_(DQ5B)/(DQ3B)/(DQ5B)_U10") (pintype "bidirectional"))
    )
    (net (code "354") (name "unconnected-(U25C-IO,_DIFFIO_B18n,_(DQ5B){slash}(DQ3B){slash}(DQ5B)-PadAB8)") (class "Default")
      (node (ref "U25") (pin "AB8") (pinfunction "IO,_DIFFIO_B18n,_(DQ5B)/(DQ3B)/(DQ5B)_AB8") (pintype "bidirectional"))
    )
    (net (code "355") (name "unconnected-(U25C-IO,_DIFFIO_B18p,_(DQ5B){slash}(DQ3B){slash}(DQ5B)-PadAA8)") (class "Default")
      (node (ref "U25") (pin "AA8") (pinfunction "IO,_DIFFIO_B18p,_(DQ5B)/(DQ3B)/(DQ5B)_AA8") (pintype "bidirectional"))
    )
    (net (code "356") (name "unconnected-(U25C-IO,_DIFFIO_B21n,_(DQS5B{slash}CQ5B#,DPCLK3){slash}(DQS5B{slash}CQ5B#,DPCLK3){slash}(DQS5B{slash}CQ5B#,DPCLK3)-PadAB9)") (class "Default")
      (node (ref "U25") (pin "AB9") (pinfunction "IO,_DIFFIO_B21n,_(DQS5B/CQ5B#,DPCLK3)/(DQS5B/CQ5B#,DPCLK3)/(DQS5B/CQ5B#,DPCLK3)_AB9") (pintype "bidirectional"))
    )
    (net (code "357") (name "unconnected-(U25C-IO,_DIFFIO_B21p,_(DQ5B){slash}(DQ3B){slash}(DQ5B)-PadAA9)") (class "Default")
      (node (ref "U25") (pin "AA9") (pinfunction "IO,_DIFFIO_B21p,_(DQ5B)/(DQ3B)/(DQ5B)_AA9") (pintype "bidirectional"))
    )
    (net (code "358") (name "unconnected-(U25C-IO,_DIFFIO_B25n,_(DQ5B){slash}(DQ3B){slash}(DQ5B)-PadV11)") (class "Default")
      (node (ref "U25") (pin "V11") (pinfunction "IO,_DIFFIO_B25n,_(DQ5B)/(DQ3B)/(DQ5B)_V11") (pintype "bidirectional"))
    )
    (net (code "359") (name "unconnected-(U25C-IO,_DIFFIO_B26n,_(DQ5B){slash}(DQ3B){slash}(DQ5B)-PadY10)") (class "Default")
      (node (ref "U25") (pin "Y10") (pinfunction "IO,_DIFFIO_B26n,_(DQ5B)/(DQ3B)/(DQ5B)_Y10") (pintype "bidirectional"))
    )
    (net (code "360") (name "unconnected-(U25C-IO,_DIFFIO_B26p,_(DQ5B){slash}(DQ3B){slash}(DQ5B)-PadW10)") (class "Default")
      (node (ref "U25") (pin "W10") (pinfunction "IO,_DIFFIO_B26p,_(DQ5B)/(DQ3B)/(DQ5B)_W10") (pintype "bidirectional"))
    )
    (net (code "361") (name "unconnected-(U25C-IO,_DIFFIO_B27n,_(_){slash}(DQ5B){slash}(DQ5B)-PadAB10)") (class "Default")
      (node (ref "U25") (pin "AB10") (pinfunction "IO,_DIFFIO_B27n,_(_)/(DQ5B)/(DQ5B)_AB10") (pintype "bidirectional"))
    )
    (net (code "362") (name "unconnected-(U25C-IO,_DIFFIO_B27p,_(DM4B){slash}(DM5B{slash}BWS#5B){slash}(DM5B{slash}BWS#5B)-PadAA10)") (class "Default")
      (node (ref "U25") (pin "AA10") (pinfunction "IO,_DIFFIO_B27p,_(DM4B)/(DM5B/BWS#5B)/(DM5B/BWS#5B)_AA10") (pintype "bidirectional"))
    )
    (net (code "363") (name "unconnected-(U25C-IO,_VREFB3N0-PadU11)") (class "Default")
      (node (ref "U25") (pin "U11") (pinfunction "IO,_VREFB3N0_U11") (pintype "bidirectional"))
    )
    (net (code "364") (name "unconnected-(U25C-IO,_VREFB3N1-PadV9)") (class "Default")
      (node (ref "U25") (pin "V9") (pinfunction "IO,_VREFB3N1_V9") (pintype "bidirectional"))
    )
    (net (code "365") (name "unconnected-(U25C-IO,_VREFB3N2-PadAB4)") (class "Default")
      (node (ref "U25") (pin "AB4") (pinfunction "IO,_VREFB3N2_AB4") (pintype "bidirectional"))
    )
    (net (code "366") (name "unconnected-(U25C-IO,_VREFB3N3-PadY4)") (class "Default")
      (node (ref "U25") (pin "Y4") (pinfunction "IO,_VREFB3N3_Y4") (pintype "bidirectional"))
    )
    (net (code "367") (name "unconnected-(U25D-IO,_(DQ2B){slash}(DQ5B){slash}(DQ5B)-PadAB18)") (class "Default")
      (node (ref "U25") (pin "AB18") (pinfunction "IO,_(DQ2B)/(DQ5B)/(DQ5B)_AB18") (pintype "bidirectional"))
    )
    (net (code "368") (name "unconnected-(U25D-IO,_(DQS2B{slash}CQ3B,DPCLK5){slash}(DQS2B{slash}CQ3B,DPCLK5){slash}(DQS2B{slash}CQ3B,DPCLK5)-PadV13)") (class "Default")
      (node (ref "U25") (pin "V13") (pinfunction "IO,_(DQS2B/CQ3B,DPCLK5)/(DQS2B/CQ3B,DPCLK5)/(DQS2B/CQ3B,DPCLK5)_V13") (pintype "bidirectional"))
    )
    (net (code "369") (name "unconnected-(U25D-IO,_DIFFIO_B28n,_(DQ4B){slash}(DQ5B){slash}(DQ5B)-PadAB13)") (class "Default")
      (node (ref "U25") (pin "AB13") (pinfunction "IO,_DIFFIO_B28n,_(DQ4B)/(DQ5B)/(DQ5B)_AB13") (pintype "bidirectional"))
    )
    (net (code "370") (name "unconnected-(U25D-IO,_DIFFIO_B28p,_(DQ4B){slash}(DQ5B){slash}(DQ5B)-PadAA13)") (class "Default")
      (node (ref "U25") (pin "AA13") (pinfunction "IO,_DIFFIO_B28p,_(DQ4B)/(DQ5B)/(DQ5B)_AA13") (pintype "bidirectional"))
    )
    (net (code "371") (name "unconnected-(U25D-IO,_DIFFIO_B29n,_(DQ4B){slash}(DQ5B){slash}(DQ5B)-PadAB14)") (class "Default")
      (node (ref "U25") (pin "AB14") (pinfunction "IO,_DIFFIO_B29n,_(DQ4B)/(DQ5B)/(DQ5B)_AB14") (pintype "bidirectional"))
    )
    (net (code "372") (name "unconnected-(U25D-IO,_DIFFIO_B29p,_(DQ4B){slash}(DQ5B){slash}(DQ5B)-PadAA14)") (class "Default")
      (node (ref "U25") (pin "AA14") (pinfunction "IO,_DIFFIO_B29p,_(DQ4B)/(DQ5B)/(DQ5B)_AA14") (pintype "bidirectional"))
    )
    (net (code "373") (name "unconnected-(U25D-IO,_DIFFIO_B32n,_(DQS4B{slash}CQ5B,DPCLK4){slash}(DQS4B{slash}CQ5B,DPCLK4){slash}(DQS4B{slash}CQ5B,DPCLK4)-PadY13)") (class "Default")
      (node (ref "U25") (pin "Y13") (pinfunction "IO,_DIFFIO_B32n,_(DQS4B/CQ5B,DPCLK4)/(DQS4B/CQ5B,DPCLK4)/(DQS4B/CQ5B,DPCLK4)_Y13") (pintype "bidirectional"))
    )
    (net (code "374") (name "unconnected-(U25D-IO,_DIFFIO_B32p,_(DQ4B){slash}(DQ5B){slash}(DQ5B)-PadW13)") (class "Default")
      (node (ref "U25") (pin "W13") (pinfunction "IO,_DIFFIO_B32p,_(DQ4B)/(DQ5B)/(DQ5B)_W13") (pintype "bidirectional"))
    )
    (net (code "375") (name "unconnected-(U25D-IO,_DIFFIO_B33n,_(DQ4B){slash}(DQ5B){slash}(DQ5B)-PadAB15)") (class "Default")
      (node (ref "U25") (pin "AB15") (pinfunction "IO,_DIFFIO_B33n,_(DQ4B)/(DQ5B)/(DQ5B)_AB15") (pintype "bidirectional"))
    )
    (net (code "376") (name "unconnected-(U25D-IO,_DIFFIO_B33p,_(DQ4B){slash}(DQ5B){slash}(DQ5B)-PadAA15)") (class "Default")
      (node (ref "U25") (pin "AA15") (pinfunction "IO,_DIFFIO_B33p,_(DQ4B)/(DQ5B)/(DQ5B)_AA15") (pintype "bidirectional"))
    )
    (net (code "377") (name "unconnected-(U25D-IO,_DIFFIO_B34p,_(DQ4B){slash}(DQ5B){slash}(DQ5B)-PadU12)") (class "Default")
      (node (ref "U25") (pin "U12") (pinfunction "IO,_DIFFIO_B34p,_(DQ4B)/(DQ5B)/(DQ5B)_U12") (pintype "bidirectional"))
    )
    (net (code "378") (name "unconnected-(U25D-IO,_DIFFIO_B35n,_(DQ2B){slash}(DQ5B){slash}(DQ5B)-PadAB16)") (class "Default")
      (node (ref "U25") (pin "AB16") (pinfunction "IO,_DIFFIO_B35n,_(DQ2B)/(DQ5B)/(DQ5B)_AB16") (pintype "bidirectional"))
    )
    (net (code "379") (name "unconnected-(U25D-IO,_DIFFIO_B35p,_(DM2B){slash}(DM5B{slash}BWS#5B){slash}(DM5B{slash}BWS#5B)-PadAA16)") (class "Default")
      (node (ref "U25") (pin "AA16") (pinfunction "IO,_DIFFIO_B35p,_(DM2B)/(DM5B/BWS#5B)/(DM5B/BWS#5B)_AA16") (pintype "bidirectional"))
    )
    (net (code "380") (name "unconnected-(U25D-IO,_DIFFIO_B36n-PadT13)") (class "Default")
      (node (ref "U25") (pin "T13") (pinfunction "IO,_DIFFIO_B36n_T13") (pintype "bidirectional"))
    )
    (net (code "381") (name "unconnected-(U25D-IO,_DIFFIO_B36p-PadT12)") (class "Default")
      (node (ref "U25") (pin "T12") (pinfunction "IO,_DIFFIO_B36p_T12") (pintype "bidirectional"))
    )
    (net (code "382") (name "unconnected-(U25D-IO,_DIFFIO_B38n-PadU13)") (class "Default")
      (node (ref "U25") (pin "U13") (pinfunction "IO,_DIFFIO_B38n_U13") (pintype "bidirectional"))
    )
    (net (code "383") (name "unconnected-(U25D-IO,_DIFFIO_B39n-PadU14)") (class "Default")
      (node (ref "U25") (pin "U14") (pinfunction "IO,_DIFFIO_B39n_U14") (pintype "bidirectional"))
    )
    (net (code "384") (name "unconnected-(U25D-IO,_DIFFIO_B39p,_(DQ2B){slash}(DQ5B){slash}(DQ5B)-PadV14)") (class "Default")
      (node (ref "U25") (pin "V14") (pinfunction "IO,_DIFFIO_B39p,_(DQ2B)/(DQ5B)/(DQ5B)_V14") (pintype "bidirectional"))
    )
    (net (code "385") (name "unconnected-(U25D-IO,_DIFFIO_B40n,_(DQ2B){slash}(DQ5B){slash}(DQ5B)-PadV15)") (class "Default")
      (node (ref "U25") (pin "V15") (pinfunction "IO,_DIFFIO_B40n,_(DQ2B)/(DQ5B)/(DQ5B)_V15") (pintype "bidirectional"))
    )
    (net (code "386") (name "unconnected-(U25D-IO,_DIFFIO_B40p-PadU15)") (class "Default")
      (node (ref "U25") (pin "U15") (pinfunction "IO,_DIFFIO_B40p_U15") (pintype "bidirectional"))
    )
    (net (code "387") (name "unconnected-(U25D-IO,_DIFFIO_B41n,_(DQ2B){slash}(DQ5B){slash}(DQ5B)-PadW15)") (class "Default")
      (node (ref "U25") (pin "W15") (pinfunction "IO,_DIFFIO_B41n,_(DQ2B)/(DQ5B)/(DQ5B)_W15") (pintype "bidirectional"))
    )
    (net (code "388") (name "unconnected-(U25D-IO,_DIFFIO_B42n,_(DQ2B){slash}(DQ5B){slash}(DQ5B)-PadT15)") (class "Default")
      (node (ref "U25") (pin "T15") (pinfunction "IO,_DIFFIO_B42n,_(DQ2B)/(DQ5B)/(DQ5B)_T15") (pintype "bidirectional"))
    )
    (net (code "389") (name "unconnected-(U25D-IO,_DIFFIO_B42p-PadT14)") (class "Default")
      (node (ref "U25") (pin "T14") (pinfunction "IO,_DIFFIO_B42p_T14") (pintype "bidirectional"))
    )
    (net (code "390") (name "unconnected-(U25D-IO,_DIFFIO_B43n-PadAB17)") (class "Default")
      (node (ref "U25") (pin "AB17") (pinfunction "IO,_DIFFIO_B43n_AB17") (pintype "bidirectional"))
    )
    (net (code "391") (name "unconnected-(U25D-IO,_DIFFIO_B43p-PadAA17)") (class "Default")
      (node (ref "U25") (pin "AA17") (pinfunction "IO,_DIFFIO_B43p_AA17") (pintype "bidirectional"))
    )
    (net (code "392") (name "unconnected-(U25D-IO,_DIFFIO_B48n,_(DQS0B{slash}CQ1B,CDPCLK3){slash}(DQS0B{slash}CQ1B,CDPCLK3){slash}(DQS0B{slash}CQ1B,CDPCLK3)-PadY17)") (class "Default")
      (node (ref "U25") (pin "Y17") (pinfunction "IO,_DIFFIO_B48n,_(DQS0B/CQ1B,CDPCLK3)/(DQS0B/CQ1B,CDPCLK3)/(DQS0B/CQ1B,CDPCLK3)_Y17") (pintype "bidirectional"))
    )
    (net (code "393") (name "unconnected-(U25D-IO,_DIFFIO_B48p,_(DQ2B){slash}(DQ5B){slash}(DQ5B)-PadW17)") (class "Default")
      (node (ref "U25") (pin "W17") (pinfunction "IO,_DIFFIO_B48p,_(DQ2B)/(DQ5B)/(DQ5B)_W17") (pintype "bidirectional"))
    )
    (net (code "394") (name "unconnected-(U25D-IO,_DIFFIO_B49n,_(DQ2B){slash}(DQ5B){slash}(DQ5B)-PadAB20)") (class "Default")
      (node (ref "U25") (pin "AB20") (pinfunction "IO,_DIFFIO_B49n,_(DQ2B)/(DQ5B)/(DQ5B)_AB20") (pintype "bidirectional"))
    )
    (net (code "395") (name "unconnected-(U25D-IO,_DIFFIO_B50n-PadU17)") (class "Default")
      (node (ref "U25") (pin "U17") (pinfunction "IO,_DIFFIO_B50n_U17") (pintype "bidirectional"))
    )
    (net (code "396") (name "unconnected-(U25D-IO,_DIFFIO_B50p-PadU16)") (class "Default")
      (node (ref "U25") (pin "U16") (pinfunction "IO,_DIFFIO_B50p_U16") (pintype "bidirectional"))
    )
    (net (code "397") (name "unconnected-(U25D-IO,_DIFFIO_B52n-PadR15)") (class "Default")
      (node (ref "U25") (pin "R15") (pinfunction "IO,_DIFFIO_B52n_R15") (pintype "bidirectional"))
    )
    (net (code "398") (name "unconnected-(U25D-IO,_DIFFIO_B52p-PadR14)") (class "Default")
      (node (ref "U25") (pin "R14") (pinfunction "IO,_DIFFIO_B52p_R14") (pintype "bidirectional"))
    )
    (net (code "399") (name "unconnected-(U25D-IO,_PLL4_CLKOUTn-PadR16)") (class "Default")
      (node (ref "U25") (pin "R16") (pinfunction "IO,_PLL4_CLKOUTn_R16") (pintype "bidirectional"))
    )
    (net (code "400") (name "unconnected-(U25D-IO,_PLL4_CLKOUTp-PadT16)") (class "Default")
      (node (ref "U25") (pin "T16") (pinfunction "IO,_PLL4_CLKOUTp_T16") (pintype "bidirectional"))
    )
    (net (code "401") (name "unconnected-(U25D-IO,_RDN2-PadAB19)") (class "Default")
      (node (ref "U25") (pin "AB19") (pinfunction "IO,_RDN2_AB19") (pintype "bidirectional"))
    )
    (net (code "402") (name "unconnected-(U25D-IO,_RUP2-PadAA19)") (class "Default")
      (node (ref "U25") (pin "AA19") (pinfunction "IO,_RUP2_AA19") (pintype "bidirectional"))
    )
    (net (code "403") (name "unconnected-(U25D-IO,_VREFB4N0-PadV16)") (class "Default")
      (node (ref "U25") (pin "V16") (pinfunction "IO,_VREFB4N0_V16") (pintype "bidirectional"))
    )
    (net (code "404") (name "unconnected-(U25D-IO,_VREFB4N1-PadAA18)") (class "Default")
      (node (ref "U25") (pin "AA18") (pinfunction "IO,_VREFB4N1_AA18") (pintype "bidirectional"))
    )
    (net (code "405") (name "unconnected-(U25D-IO,_VREFB4N2-PadW14)") (class "Default")
      (node (ref "U25") (pin "W14") (pinfunction "IO,_VREFB4N2_W14") (pintype "bidirectional"))
    )
    (net (code "406") (name "unconnected-(U25D-IO,_VREFB4N3-PadV12)") (class "Default")
      (node (ref "U25") (pin "V12") (pinfunction "IO,_VREFB4N3_V12") (pintype "bidirectional"))
    )
    (net (code "407") (name "unconnected-(U25E-IO,_DIFFIO_R33n-PadN17)") (class "Default")
      (node (ref "U25") (pin "N17") (pinfunction "IO,_DIFFIO_R33n_N17") (pintype "bidirectional"))
    )
    (net (code "408") (name "unconnected-(U25E-IO,_DIFFIO_R33p,_(DQS1R{slash}CQ1R#,DPCLK6){slash}(DQS1R{slash}CQ1R#,DPCLK6){slash}(DQS1R{slash}CQ1R#,DPCLK6)-PadN18)") (class "Default")
      (node (ref "U25") (pin "N18") (pinfunction "IO,_DIFFIO_R33p,_(DQS1R/CQ1R#,DPCLK6)/(DQS1R/CQ1R#,DPCLK6)/(DQS1R/CQ1R#,DPCLK6)_N18") (pintype "bidirectional"))
    )
    (net (code "409") (name "unconnected-(U25E-IO,_DIFFIO_R40p-PadN16)") (class "Default")
      (node (ref "U25") (pin "N16") (pinfunction "IO,_DIFFIO_R40p_N16") (pintype "bidirectional"))
    )
    (net (code "410") (name "unconnected-(U25E-IO,_DIFFIO_R42n-PadR18)") (class "Default")
      (node (ref "U25") (pin "R18") (pinfunction "IO,_DIFFIO_R42n_R18") (pintype "bidirectional"))
    )
    (net (code "411") (name "unconnected-(U25E-IO,_DIFFIO_R46n-PadP15)") (class "Default")
      (node (ref "U25") (pin "P15") (pinfunction "IO,_DIFFIO_R46n_P15") (pintype "bidirectional"))
    )
    (net (code "412") (name "unconnected-(U25E-IO,_DIFFIO_R46p-PadP16)") (class "Default")
      (node (ref "U25") (pin "P16") (pinfunction "IO,_DIFFIO_R46p_P16") (pintype "bidirectional"))
    )
    (net (code "413") (name "unconnected-(U25E-IO,_RDN3-PadT18)") (class "Default")
      (node (ref "U25") (pin "T18") (pinfunction "IO,_RDN3_T18") (pintype "bidirectional"))
    )
    (net (code "414") (name "unconnected-(U25E-IO,_RUP3-PadT17)") (class "Default")
      (node (ref "U25") (pin "T17") (pinfunction "IO,_RUP3_T17") (pintype "bidirectional"))
    )
    (net (code "415") (name "unconnected-(U25E-IO,_VREFB5N0-PadM16)") (class "Default")
      (node (ref "U25") (pin "M16") (pinfunction "IO,_VREFB5N0_M16") (pintype "bidirectional"))
    )
    (net (code "416") (name "unconnected-(U25E-IO,_VREFB5N1-PadP20)") (class "Default")
      (node (ref "U25") (pin "P20") (pinfunction "IO,_VREFB5N1_P20") (pintype "bidirectional"))
    )
    (net (code "417") (name "unconnected-(U25E-IO,_VREFB5N2-PadR17)") (class "Default")
      (node (ref "U25") (pin "R17") (pinfunction "IO,_VREFB5N2_R17") (pintype "bidirectional"))
    )
    (net (code "418") (name "unconnected-(U25E-IO,_VREFB5N3-PadW19)") (class "Default")
      (node (ref "U25") (pin "W19") (pinfunction "IO,_VREFB5N3_W19") (pintype "bidirectional"))
    )
    (net (code "419") (name "unconnected-(U25E-IO-PadP17)") (class "Default")
      (node (ref "U25") (pin "P17") (pinfunction "IO_P17") (pintype "bidirectional"))
    )
    (net (code "420") (name "unconnected-(U25F-IO,_DIFFIO_R2n,_(DQ2R){slash}(DQ1R){slash}(DQ1R)-PadF17)") (class "Default")
      (node (ref "U25") (pin "F17") (pinfunction "IO,_DIFFIO_R2n,_(DQ2R)/(DQ1R)/(DQ1R)_F17") (pintype "bidirectional"))
    )
    (net (code "421") (name "unconnected-(U25F-IO,_DIFFIO_R2p-PadG17)") (class "Default")
      (node (ref "U25") (pin "G17") (pinfunction "IO,_DIFFIO_R2p_G17") (pintype "bidirectional"))
    )
    (net (code "422") (name "unconnected-(U25F-IO,_DIFFIO_R7n,_(PADD23),_(DQ2R){slash}(DQ1R){slash}(DQ1R)-PadG18)") (class "Default")
      (node (ref "U25") (pin "G18") (pinfunction "IO,_DIFFIO_R7n,_(PADD23),_(DQ2R)/(DQ1R)/(DQ1R)_G18") (pintype "bidirectional"))
    )
    (net (code "423") (name "unconnected-(U25F-IO,_DIFFIO_R7p-PadH17)") (class "Default")
      (node (ref "U25") (pin "H17") (pinfunction "IO,_DIFFIO_R7p_H17") (pintype "bidirectional"))
    )
    (net (code "424") (name "unconnected-(U25F-IO,_DIFFIO_R10n-PadJ17)") (class "Default")
      (node (ref "U25") (pin "J17") (pinfunction "IO,_DIFFIO_R10n_J17") (pintype "bidirectional"))
    )
    (net (code "425") (name "unconnected-(U25F-IO,_DIFFIO_R10p-PadH16)") (class "Default")
      (node (ref "U25") (pin "H16") (pinfunction "IO,_DIFFIO_R10p_H16") (pintype "bidirectional"))
    )
    (net (code "426") (name "unconnected-(U25F-IO,_DIFFIO_R20n-PadK17)") (class "Default")
      (node (ref "U25") (pin "K17") (pinfunction "IO,_DIFFIO_R20n_K17") (pintype "bidirectional"))
    )
    (net (code "427") (name "unconnected-(U25F-IO,_DIFFIO_R24n,_(nCEO)-PadK22)") (class "Default")
      (node (ref "U25") (pin "K22") (pinfunction "IO,_DIFFIO_R24n,_(nCEO)_K22") (pintype "bidirectional"))
    )
    (net (code "428") (name "unconnected-(U25F-IO,_VREFB6N0-PadD20)") (class "Default")
      (node (ref "U25") (pin "D20") (pinfunction "IO,_VREFB6N0_D20") (pintype "bidirectional"))
    )
    (net (code "429") (name "unconnected-(U25F-IO,_VREFB6N1-PadH18)") (class "Default")
      (node (ref "U25") (pin "H18") (pinfunction "IO,_VREFB6N1_H18") (pintype "bidirectional"))
    )
    (net (code "430") (name "unconnected-(U25F-IO,_VREFB6N2-PadJ18)") (class "Default")
      (node (ref "U25") (pin "J18") (pinfunction "IO,_VREFB6N2_J18") (pintype "bidirectional"))
    )
    (net (code "431") (name "unconnected-(U25F-IO,_VREFB6N3-PadK19)") (class "Default")
      (node (ref "U25") (pin "K19") (pinfunction "IO,_VREFB6N3_K19") (pintype "bidirectional"))
    )
    (net (code "432") (name "unconnected-(U25G-IO,_DIFFIO_T27p,_(PADD14),_(DM4T){slash}(DM5T{slash}BWS#5T){slash}(DM5T{slash}BWS#5T)-PadF11)") (class "Default")
      (node (ref "U25") (pin "F11") (pinfunction "IO,_DIFFIO_T27p,_(PADD14),_(DM4T)/(DM5T/BWS#5T)/(DM5T/BWS#5T)_F11") (pintype "bidirectional"))
    )
    (net (code "433") (name "unconnected-(U25G-IO,_DIFFIO_T37p,_(PADD4),_(DQS2T{slash}CQ3T,DPCLK8){slash}(DQS2T{slash}CQ3T,DPCLK8){slash}(DQS2T{slash}CQ3T,DPCLK8)-PadF13)") (class "Default")
      (node (ref "U25") (pin "F13") (pinfunction "IO,_DIFFIO_T37p,_(PADD4),_(DQS2T/CQ3T,DPCLK8)/(DQS2T/CQ3T,DPCLK8)/(DQS2T/CQ3T,DPCLK8)_F13") (pintype "bidirectional+no_connect"))
    )
    (net (code "434") (name "unconnected-(U25G-IO,_DIFFIO_T38n,_(PADD3),_(DQ4T){slash}(DQ5T){slash}(DQ5T)-PadE14)") (class "Default")
      (node (ref "U25") (pin "E14") (pinfunction "IO,_DIFFIO_T38n,_(PADD3),_(DQ4T)/(DQ5T)/(DQ5T)_E14") (pintype "bidirectional"))
    )
    (net (code "435") (name "unconnected-(U25G-IO,_DIFFIO_T42n-PadG13)") (class "Default")
      (node (ref "U25") (pin "G13") (pinfunction "IO,_DIFFIO_T42n_G13") (pintype "bidirectional"))
    )
    (net (code "436") (name "unconnected-(U25G-IO,_DIFFIO_T44n,_(DQ2T){slash}(DQ5T){slash}(DQ5T)-PadE15)") (class "Default")
      (node (ref "U25") (pin "E15") (pinfunction "IO,_DIFFIO_T44n,_(DQ2T)/(DQ5T)/(DQ5T)_E15") (pintype "bidirectional"))
    )
    (net (code "437") (name "unconnected-(U25G-IO,_DIFFIO_T44p-PadG14)") (class "Default")
      (node (ref "U25") (pin "G14") (pinfunction "IO,_DIFFIO_T44p_G14") (pintype "bidirectional"))
    )
    (net (code "438") (name "unconnected-(U25G-IO,_DIFFIO_T48n-PadH15)") (class "Default")
      (node (ref "U25") (pin "H15") (pinfunction "IO,_DIFFIO_T48n_H15") (pintype "bidirectional"))
    )
    (net (code "439") (name "unconnected-(U25G-IO,_DIFFIO_T48p-PadH14)") (class "Default")
      (node (ref "U25") (pin "H14") (pinfunction "IO,_DIFFIO_T48p_H14") (pintype "bidirectional"))
    )
    (net (code "440") (name "unconnected-(U25G-IO,_DIFFIO_T49n-PadG15)") (class "Default")
      (node (ref "U25") (pin "G15") (pinfunction "IO,_DIFFIO_T49n_G15") (pintype "bidirectional"))
    )
    (net (code "441") (name "unconnected-(U25G-IO,_DIFFIO_T49p,_(DQS0T{slash}CQ1T,CDPCLK6){slash}(DQS0T{slash}CQ1T,CDPCLK6){slash}(DQS0T{slash}CQ1T,CDPCLK6)-PadF14)") (class "Default")
      (node (ref "U25") (pin "F14") (pinfunction "IO,_DIFFIO_T49p,_(DQS0T/CQ1T,CDPCLK6)/(DQS0T/CQ1T,CDPCLK6)/(DQS0T/CQ1T,CDPCLK6)_F14") (pintype "bidirectional"))
    )
    (net (code "442") (name "unconnected-(U25G-IO,_DIFFIO_T50n,_(DQ2T){slash}(DQ5T){slash}(DQ5T)-PadF15)") (class "Default")
      (node (ref "U25") (pin "F15") (pinfunction "IO,_DIFFIO_T50n,_(DQ2T)/(DQ5T)/(DQ5T)_F15") (pintype "bidirectional"))
    )
    (net (code "443") (name "unconnected-(U25G-IO,_DIFFIO_T50p-PadG16)") (class "Default")
      (node (ref "U25") (pin "G16") (pinfunction "IO,_DIFFIO_T50p_G16") (pintype "bidirectional"))
    )
    (net (code "444") (name "unconnected-(U25G-IO,_DIFFIO_T51n-PadF16)") (class "Default")
      (node (ref "U25") (pin "F16") (pinfunction "IO,_DIFFIO_T51n_F16") (pintype "bidirectional"))
    )
    (net (code "445") (name "unconnected-(U25G-IO,_DIFFIO_T51p,_(DQ2T){slash}(DQ5T){slash}(DQ5T)-PadE16)") (class "Default")
      (node (ref "U25") (pin "E16") (pinfunction "IO,_DIFFIO_T51p,_(DQ2T)/(DQ5T)/(DQ5T)_E16") (pintype "bidirectional"))
    )
    (net (code "446") (name "unconnected-(U25G-IO,_VREFB7N0-PadD17)") (class "Default")
      (node (ref "U25") (pin "D17") (pinfunction "IO,_VREFB7N0_D17") (pintype "bidirectional"))
    )
    (net (code "447") (name "unconnected-(U25G-IO,_VREFB7N1-PadD15)") (class "Default")
      (node (ref "U25") (pin "D15") (pinfunction "IO,_VREFB7N1_D15") (pintype "bidirectional"))
    )
    (net (code "448") (name "unconnected-(U25G-IO,_VREFB7N2-PadC15)") (class "Default")
      (node (ref "U25") (pin "C15") (pinfunction "IO,_VREFB7N2_C15") (pintype "bidirectional"))
    )
    (net (code "449") (name "unconnected-(U25G-IO,_VREFB7N3-PadE13)") (class "Default")
      (node (ref "U25") (pin "E13") (pinfunction "IO,_VREFB7N3_E13") (pintype "bidirectional"))
    )
    (net (code "450") (name "unconnected-(U25H-IO,_DIFFIO_T1n,_(DM3T{slash}BWS#3T){slash}(DM3T{slash}BWS#3T){slash}(DM5T{slash}BWS#5T)-PadF7)") (class "Default")
      (node (ref "U25") (pin "F7") (pinfunction "IO,_DIFFIO_T1n,_(DM3T/BWS#3T)/(DM3T/BWS#3T)/(DM5T/BWS#5T)_F7") (pintype "bidirectional"))
    )
    (net (code "451") (name "unconnected-(U25H-IO,_DIFFIO_T1p-PadG7)") (class "Default")
      (node (ref "U25") (pin "G7") (pinfunction "IO,_DIFFIO_T1p_G7") (pintype "bidirectional"))
    )
    (net (code "452") (name "unconnected-(U25H-IO,_DIFFIO_T4n,_(DATA10),_(DQ3T){slash}(DQ3T){slash}(DQ5T)-PadA3)") (class "Default")
      (node (ref "U25") (pin "A3") (pinfunction "IO,_DIFFIO_T4n,_(DATA10),_(DQ3T)/(DQ3T)/(DQ5T)_A3") (pintype "bidirectional"))
    )
    (net (code "453") (name "unconnected-(U25H-IO,_DIFFIO_T5n,_(DATA9),_(DQ3T){slash}(DQ3T){slash}(DQ5T)-PadF8)") (class "Default")
      (node (ref "U25") (pin "F8") (pinfunction "IO,_DIFFIO_T5n,_(DATA9),_(DQ3T)/(DQ3T)/(DQ5T)_F8") (pintype "bidirectional"))
    )
    (net (code "454") (name "unconnected-(U25H-IO,_DIFFIO_T5p-PadG8)") (class "Default")
      (node (ref "U25") (pin "G8") (pinfunction "IO,_DIFFIO_T5p_G8") (pintype "bidirectional"))
    )
    (net (code "455") (name "unconnected-(U25H-IO,_DIFFIO_T7p-PadD7)") (class "Default")
      (node (ref "U25") (pin "D7") (pinfunction "IO,_DIFFIO_T7p_D7") (pintype "bidirectional"))
    )
    (net (code "456") (name "unconnected-(U25H-IO,_DIFFIO_T8n-PadG10)") (class "Default")
      (node (ref "U25") (pin "G10") (pinfunction "IO,_DIFFIO_T8n_G10") (pintype "bidirectional"))
    )
    (net (code "457") (name "unconnected-(U25H-IO,_DIFFIO_T8p,_(DATA6),_(DQ3T){slash}(DQ3T){slash}(DQ5T)-PadF10)") (class "Default")
      (node (ref "U25") (pin "F10") (pinfunction "IO,_DIFFIO_T8p,_(DATA6),_(DQ3T)/(DQ3T)/(DQ5T)_F10") (pintype "bidirectional"))
    )
    (net (code "458") (name "unconnected-(U25H-IO,_DIFFIO_T14n-PadH11)") (class "Default")
      (node (ref "U25") (pin "H11") (pinfunction "IO,_DIFFIO_T14n_H11") (pintype "bidirectional"))
    )
    (net (code "459") (name "unconnected-(U25H-IO,_DIFFIO_T14p-PadH10)") (class "Default")
      (node (ref "U25") (pin "H10") (pinfunction "IO,_DIFFIO_T14p_H10") (pintype "bidirectional"))
    )
    (net (code "460") (name "unconnected-(U25H-IO,_DIFFIO_T22n-PadG11)") (class "Default")
      (node (ref "U25") (pin "G11") (pinfunction "IO,_DIFFIO_T22n_G11") (pintype "bidirectional"))
    )
    (net (code "461") (name "unconnected-(U25H-IO,_PLL3_CLKOUTn-PadE6)") (class "Default")
      (node (ref "U25") (pin "E6") (pinfunction "IO,_PLL3_CLKOUTn_E6") (pintype "bidirectional"))
    )
    (net (code "462") (name "unconnected-(U25H-IO,_PLL3_CLKOUTp-PadE5)") (class "Default")
      (node (ref "U25") (pin "E5") (pinfunction "IO,_PLL3_CLKOUTp_E5") (pintype "bidirectional"))
    )
    (net (code "463") (name "unconnected-(U25H-IO,_VREFB8N0-PadC10)") (class "Default")
      (node (ref "U25") (pin "C10") (pinfunction "IO,_VREFB8N0_C10") (pintype "bidirectional"))
    )
    (net (code "464") (name "unconnected-(U25H-IO,_VREFB8N1-PadE9)") (class "Default")
      (node (ref "U25") (pin "E9") (pinfunction "IO,_VREFB8N1_E9") (pintype "bidirectional"))
    )
    (net (code "465") (name "unconnected-(U25H-IO,_VREFB8N2-PadB5)") (class "Default")
      (node (ref "U25") (pin "B5") (pinfunction "IO,_VREFB8N2_B5") (pintype "bidirectional"))
    )
    (net (code "466") (name "unconnected-(U25H-IO,_VREFB8N3-PadD6)") (class "Default")
      (node (ref "U25") (pin "D6") (pinfunction "IO,_VREFB8N3_D6") (pintype "bidirectional"))
    )
    (net (code "467") (name "unconnected-(U25H-IO-PadE7)") (class "Default")
      (node (ref "U25") (pin "E7") (pinfunction "IO_E7") (pintype "bidirectional"))
    )
    (net (code "468") (name "unconnected-(U25H-IO-PadF9)") (class "Default")
      (node (ref "U25") (pin "F9") (pinfunction "IO_F9") (pintype "bidirectional"))
    )
    (net (code "469") (name "unconnected-(U25H-IO-PadG9)") (class "Default")
      (node (ref "U25") (pin "G9") (pinfunction "IO_G9") (pintype "bidirectional"))
    )
    (net (code "470") (name "unconnected-(U25I-CLK1,_DIFFCLK_0n-PadG1)") (class "Default")
      (node (ref "U25") (pin "G1") (pinfunction "CLK1,_DIFFCLK_0n_G1") (pintype "input"))
    )
    (net (code "471") (name "unconnected-(U25I-CLK3,_DIFFCLK_1n-PadT1)") (class "Default")
      (node (ref "U25") (pin "T1") (pinfunction "CLK3,_DIFFCLK_1n_T1") (pintype "input"))
    )
    (net (code "472") (name "unconnected-(U25I-CLK4,_DIFFCLK_2p-PadG21)") (class "Default")
      (node (ref "U25") (pin "G21") (pinfunction "CLK4,_DIFFCLK_2p_G21") (pintype "input"))
    )
    (net (code "473") (name "unconnected-(U25I-CLK5,_DIFFCLK_2n-PadG22)") (class "Default")
      (node (ref "U25") (pin "G22") (pinfunction "CLK5,_DIFFCLK_2n_G22") (pintype "input"))
    )
    (net (code "474") (name "unconnected-(U25I-CLK6,_DIFFCLK_3p-PadT21)") (class "Default")
      (node (ref "U25") (pin "T21") (pinfunction "CLK6,_DIFFCLK_3p_T21") (pintype "input"))
    )
    (net (code "475") (name "unconnected-(U25I-CLK7,_DIFFCLK_3n-PadT22)") (class "Default")
      (node (ref "U25") (pin "T22") (pinfunction "CLK7,_DIFFCLK_3n_T22") (pintype "input"))
    )
    (net (code "476") (name "unconnected-(U25I-CLK8,_DIFFCLK_5n-PadA12)") (class "Default")
      (node (ref "U25") (pin "A12") (pinfunction "CLK8,_DIFFCLK_5n_A12") (pintype "input"))
    )
    (net (code "477") (name "unconnected-(U25I-CLK9,_DIFFCLK_5p-PadB12)") (class "Default")
      (node (ref "U25") (pin "B12") (pinfunction "CLK9,_DIFFCLK_5p_B12") (pintype "input"))
    )
    (net (code "478") (name "unconnected-(U25I-CLK10,_DIFFCLK_4n-PadA11)") (class "Default")
      (node (ref "U25") (pin "A11") (pinfunction "CLK10,_DIFFCLK_4n_A11") (pintype "input"))
    )
    (net (code "479") (name "unconnected-(U25I-CLK11,_DIFFCLK_4p-PadB11)") (class "Default")
      (node (ref "U25") (pin "B11") (pinfunction "CLK11,_DIFFCLK_4p_B11") (pintype "input"))
    )
    (net (code "480") (name "unconnected-(U25I-CLK12,_DIFFCLK_7n-PadAB12)") (class "Default")
      (node (ref "U25") (pin "AB12") (pinfunction "CLK12,_DIFFCLK_7n_AB12") (pintype "input"))
    )
    (net (code "481") (name "unconnected-(U25I-CLK13,_DIFFCLK_7p-PadAA12)") (class "Default")
      (node (ref "U25") (pin "AA12") (pinfunction "CLK13,_DIFFCLK_7p_AA12") (pintype "input"))
    )
    (net (code "482") (name "unconnected-(U25I-CLK14,_DIFFCLK_6n-PadAB11)") (class "Default")
      (node (ref "U25") (pin "AB11") (pinfunction "CLK14,_DIFFCLK_6n_AB11") (pintype "input"))
    )
    (net (code "483") (name "unconnected-(U25I-CLK15,_DIFFCLK_6p-PadAA11)") (class "Default")
      (node (ref "U25") (pin "AA11") (pinfunction "CLK15,_DIFFCLK_6p_AA11") (pintype "input"))
    )
    (net (code "484") (name "unconnected-(U26-CLKOUT-Pad3)") (class "Default")
      (node (ref "U26") (pin "3") (pinfunction "CLKOUT_3") (pintype "unspecified+no_connect"))
    )
    (net (code "485") (name "unconnected-(U26-NC-Pad5)") (class "Default")
      (node (ref "U26") (pin "5") (pinfunction "NC_5") (pintype "unspecified+no_connect"))
    )
    (net (code "486") (name "unconnected-(USB2-SBU1-Pad9)") (class "Default")
      (node (ref "USB2") (pin "9") (pinfunction "SBU1_9") (pintype "unspecified+no_connect"))
    )
    (net (code "487") (name "unconnected-(USB2-SBU2-Pad3)") (class "Default")
      (node (ref "USB2") (pin "3") (pinfunction "SBU2_3") (pintype "unspecified+no_connect"))
    )
  )
)
